# oresat-backplane.net
KiCad netlist of a schematic drawn in EAGLE
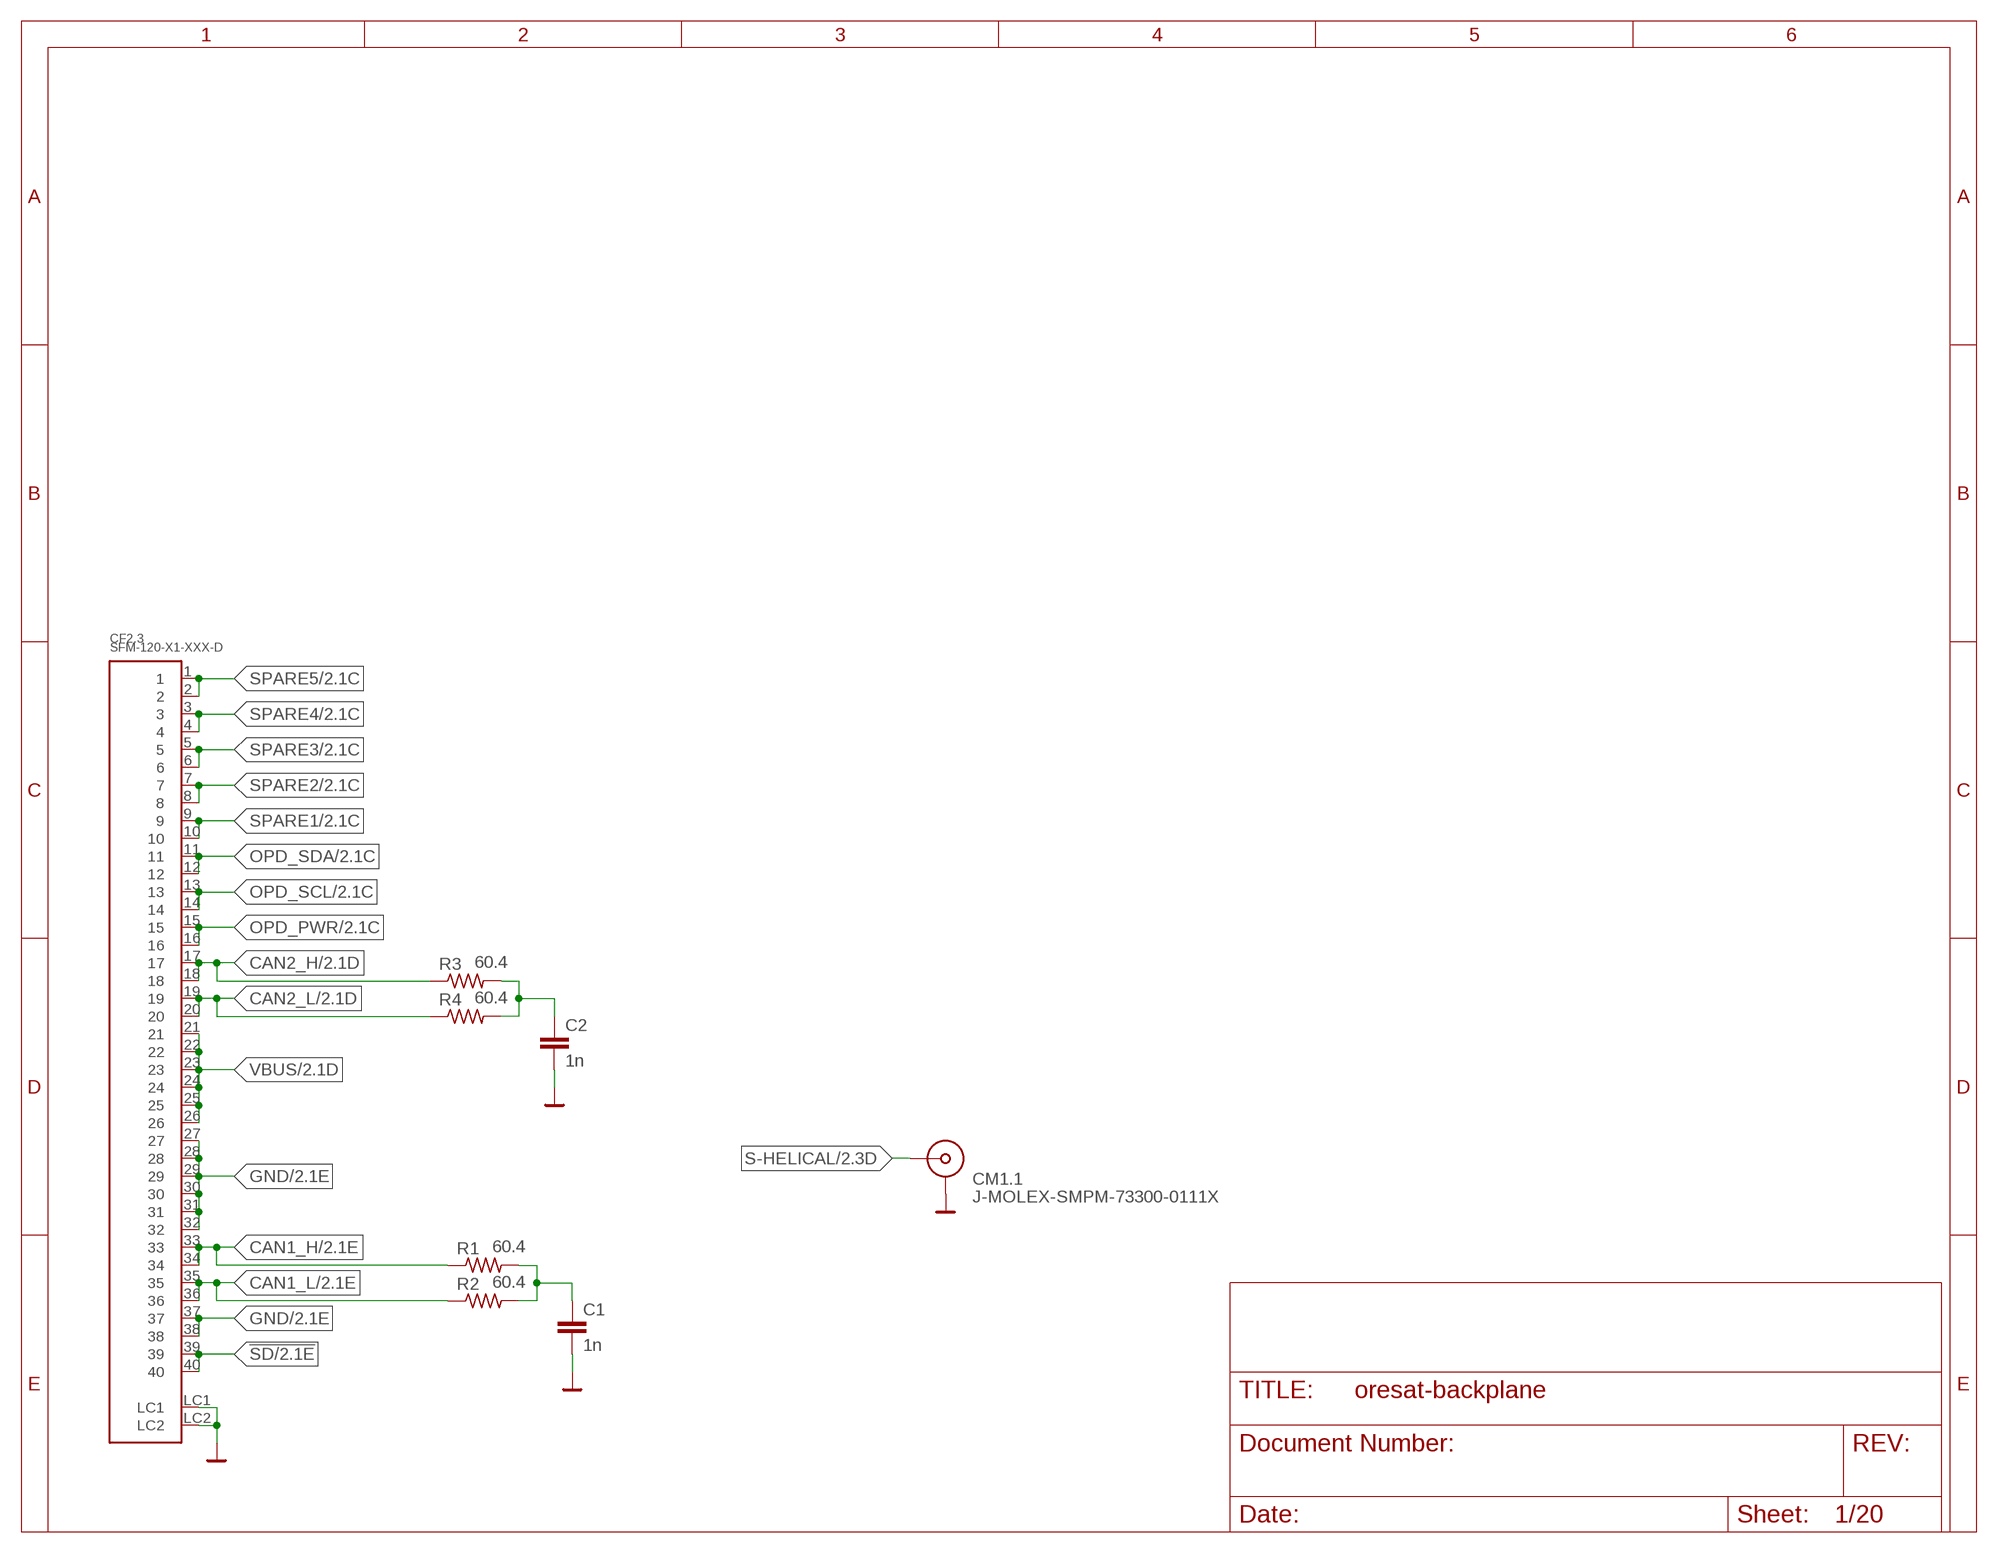
[diagram p0: schematic, sheet 1]
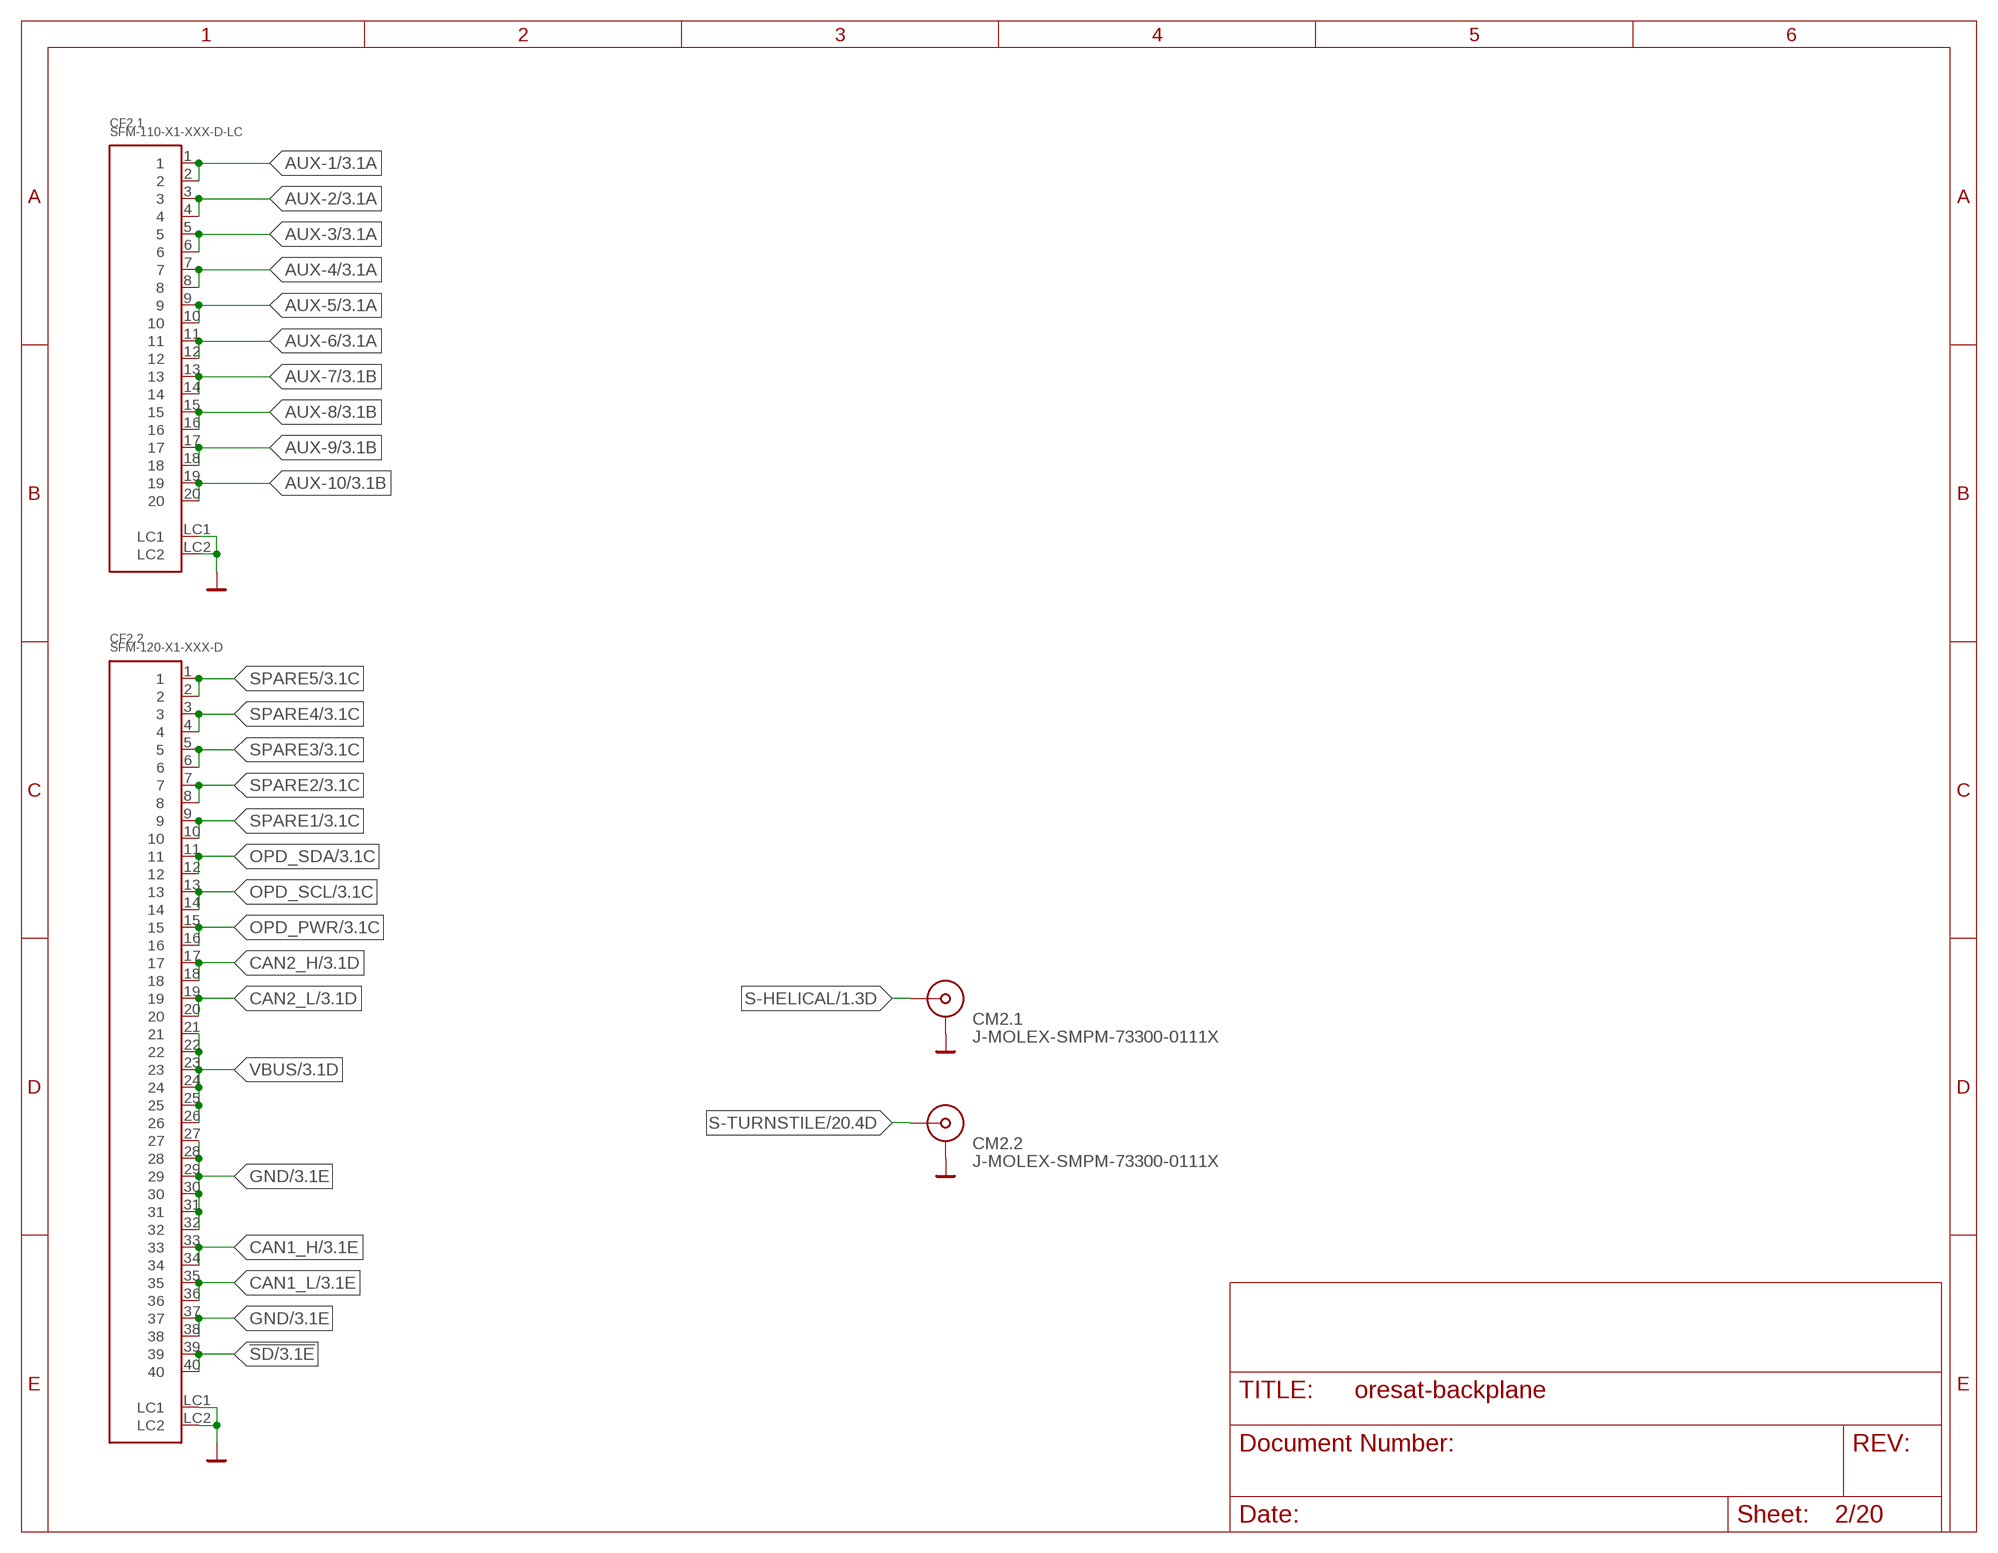
[diagram p1: schematic, sheet 2]
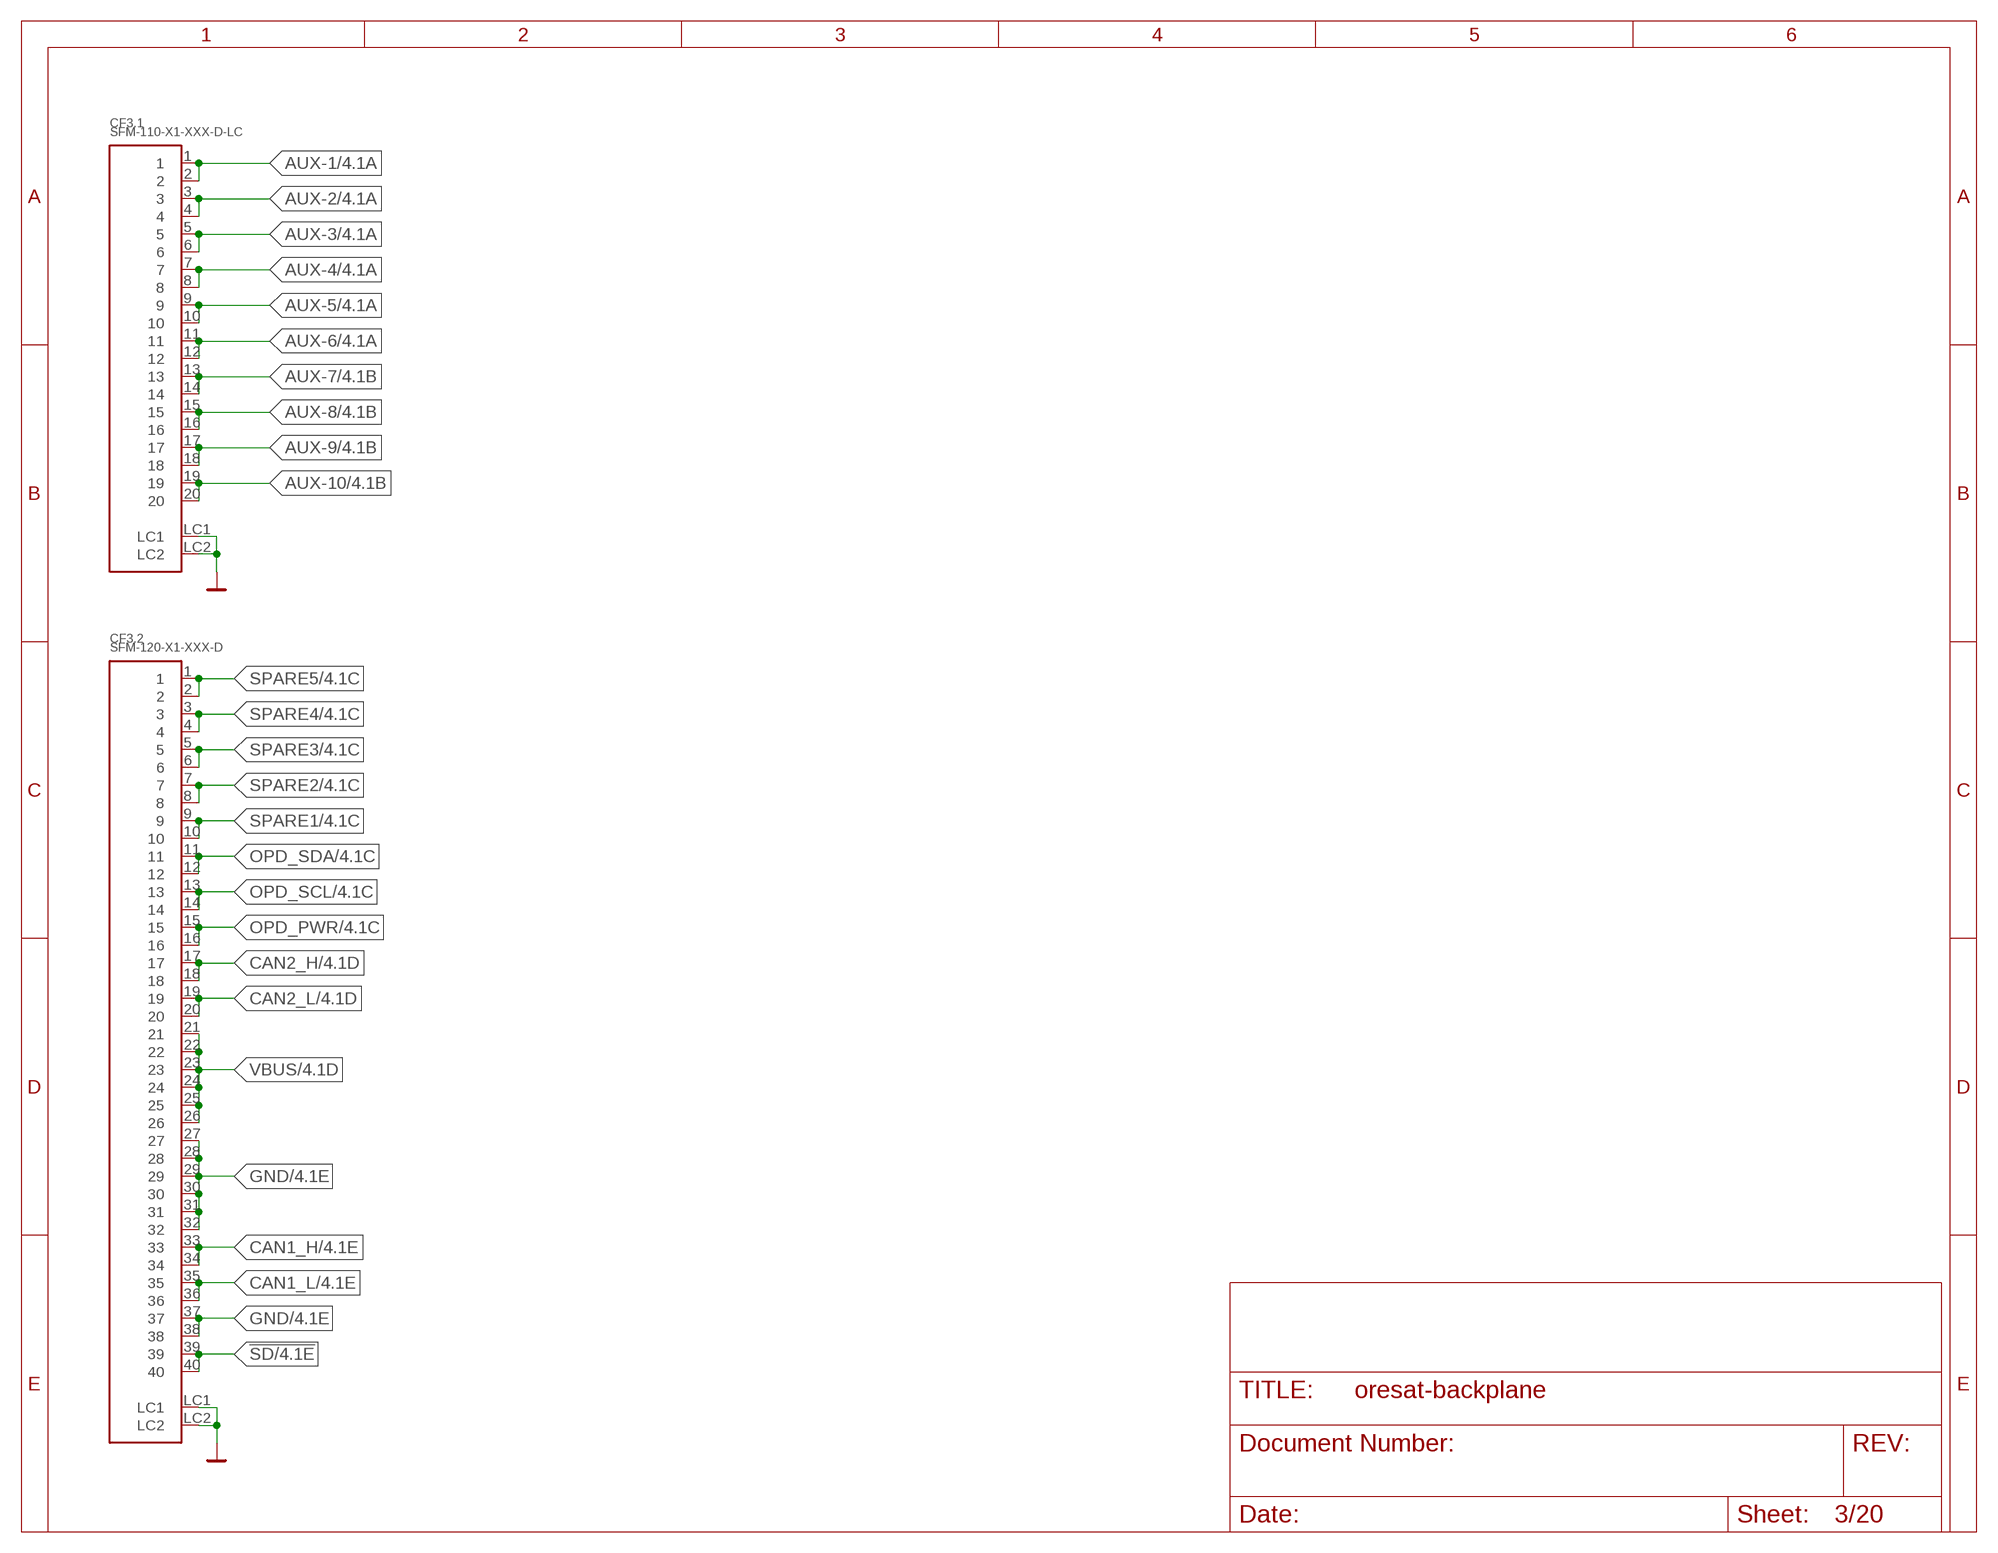
[diagram p2: schematic, sheet 3]
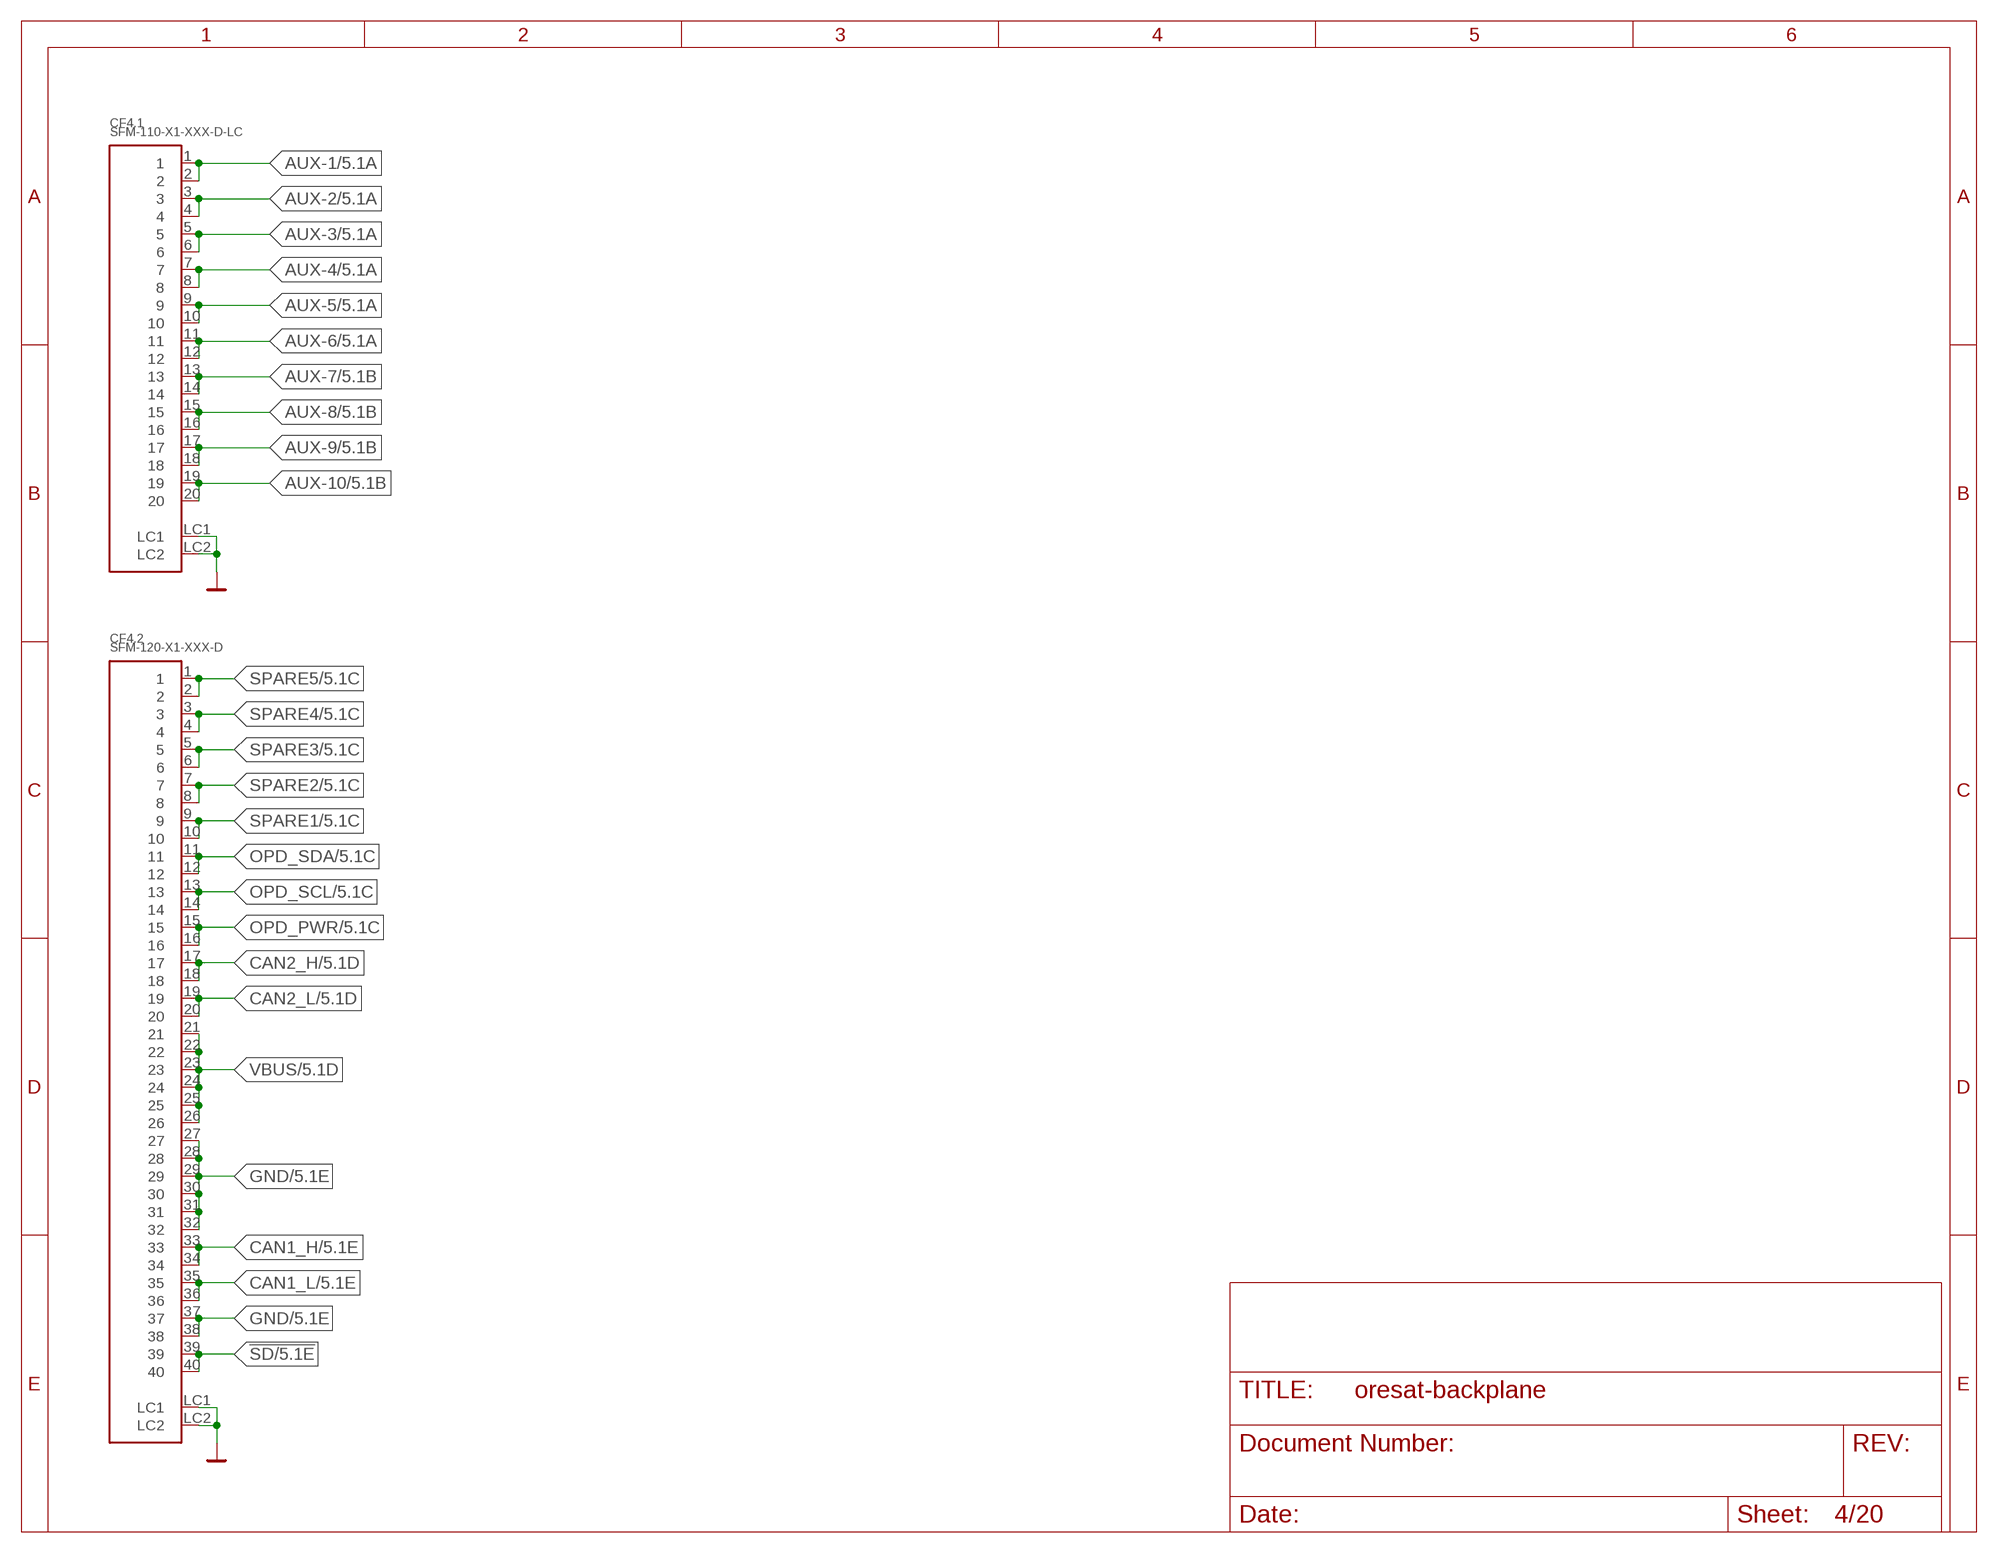
[diagram p3: schematic, sheet 4]
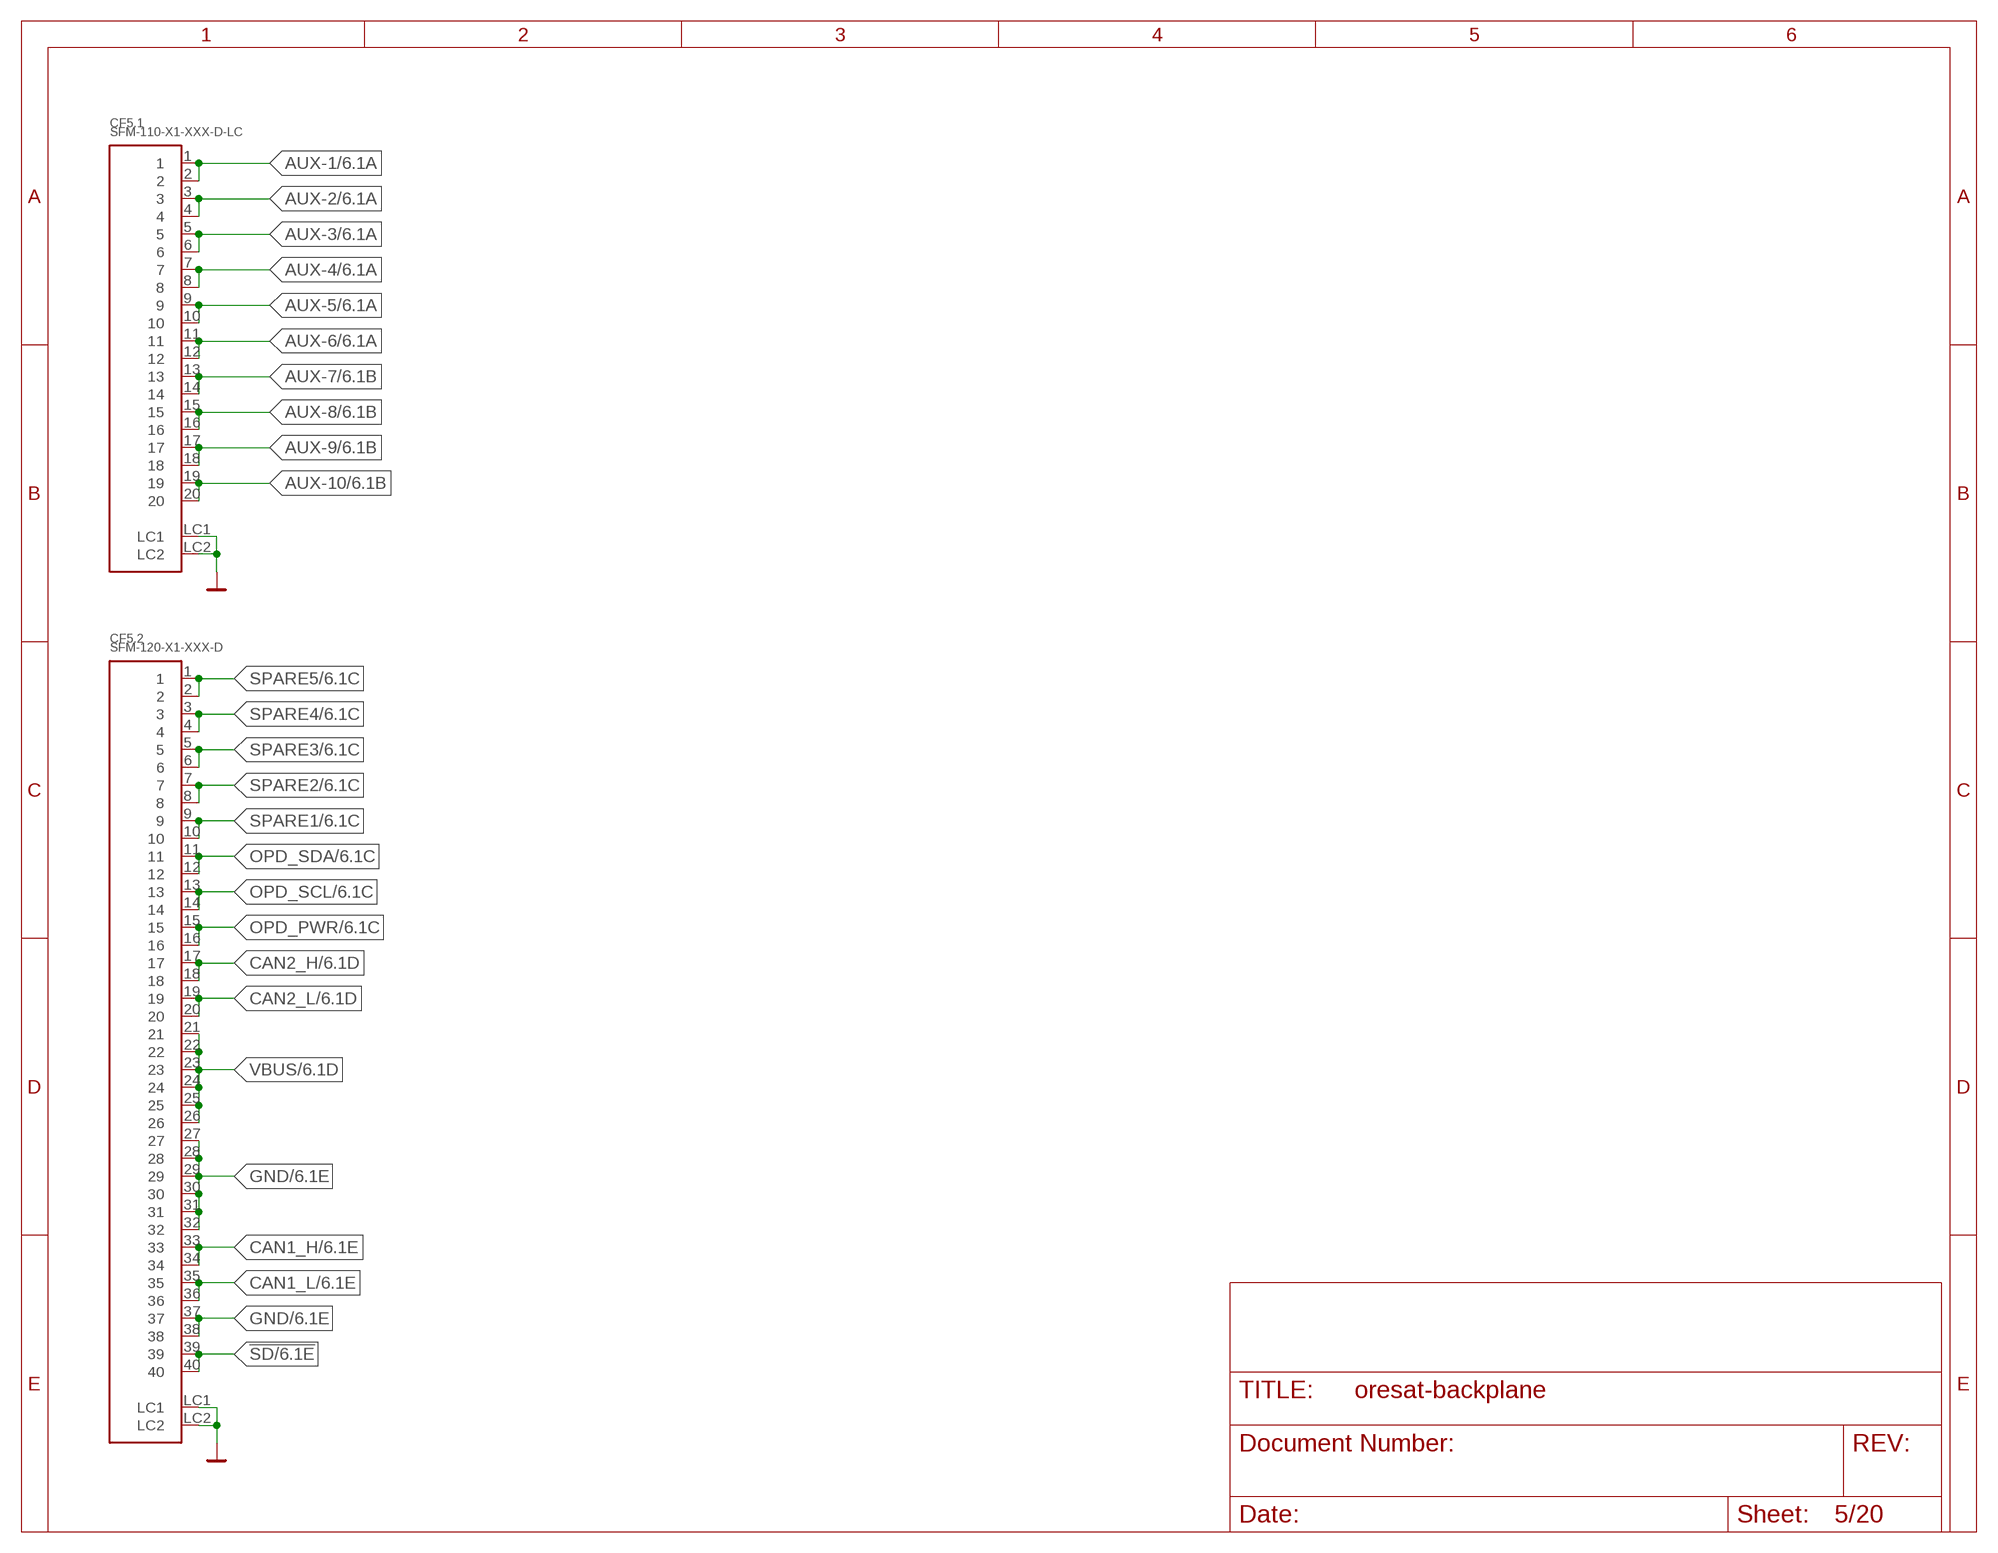
[diagram p4: schematic, sheet 5]
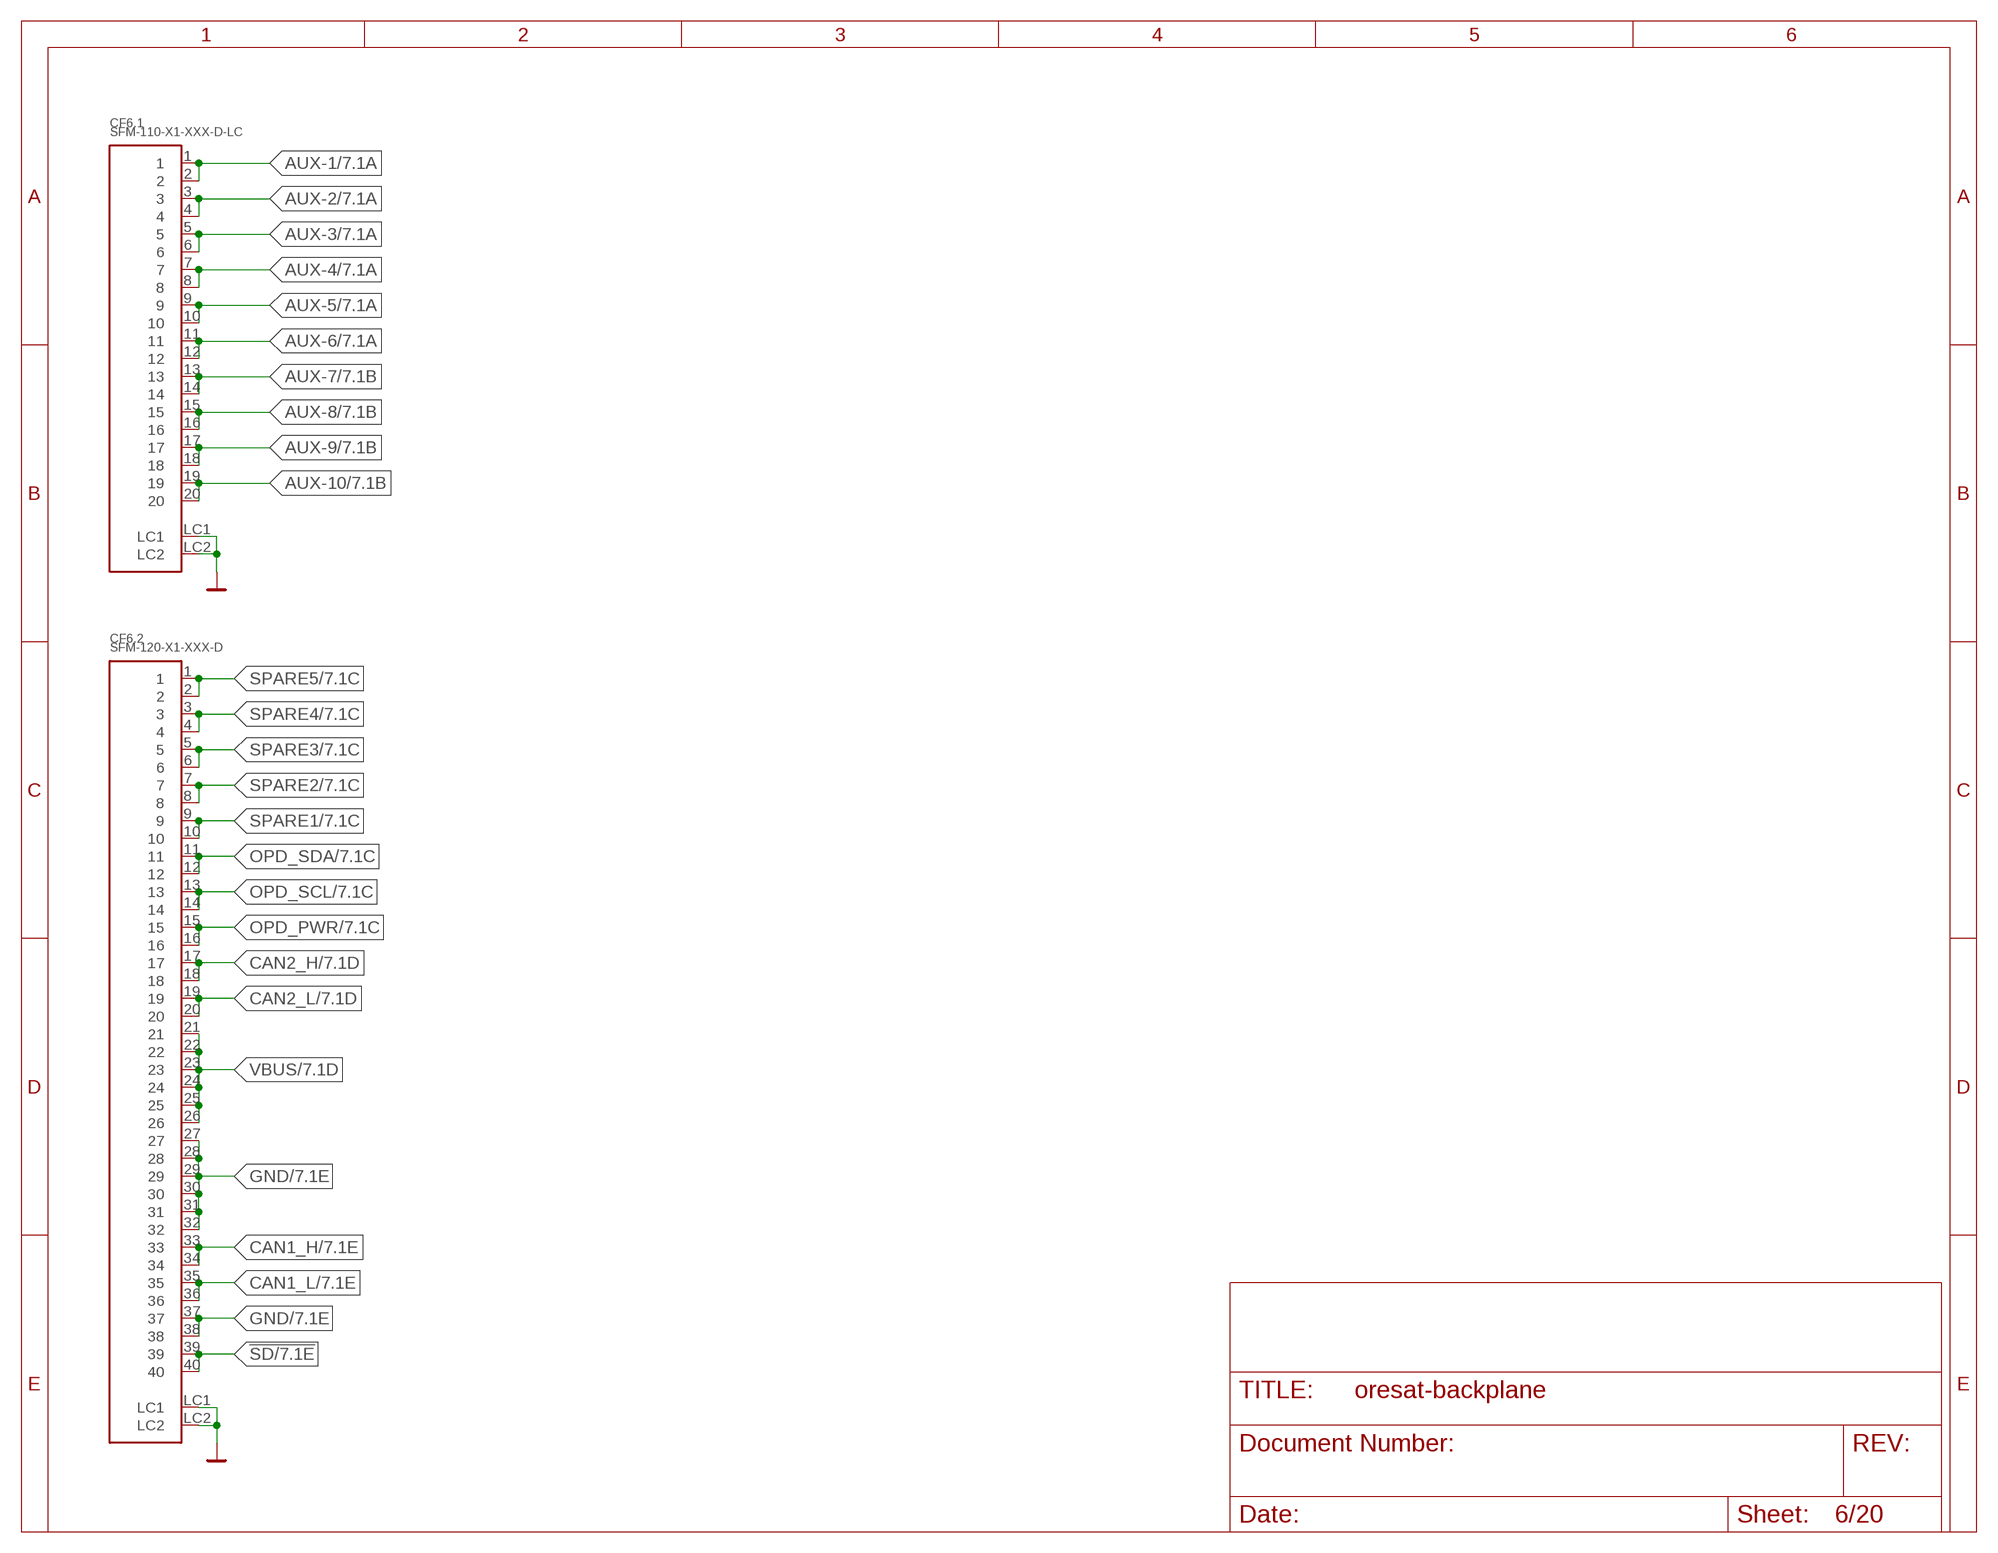
[diagram p5: schematic, sheet 6]
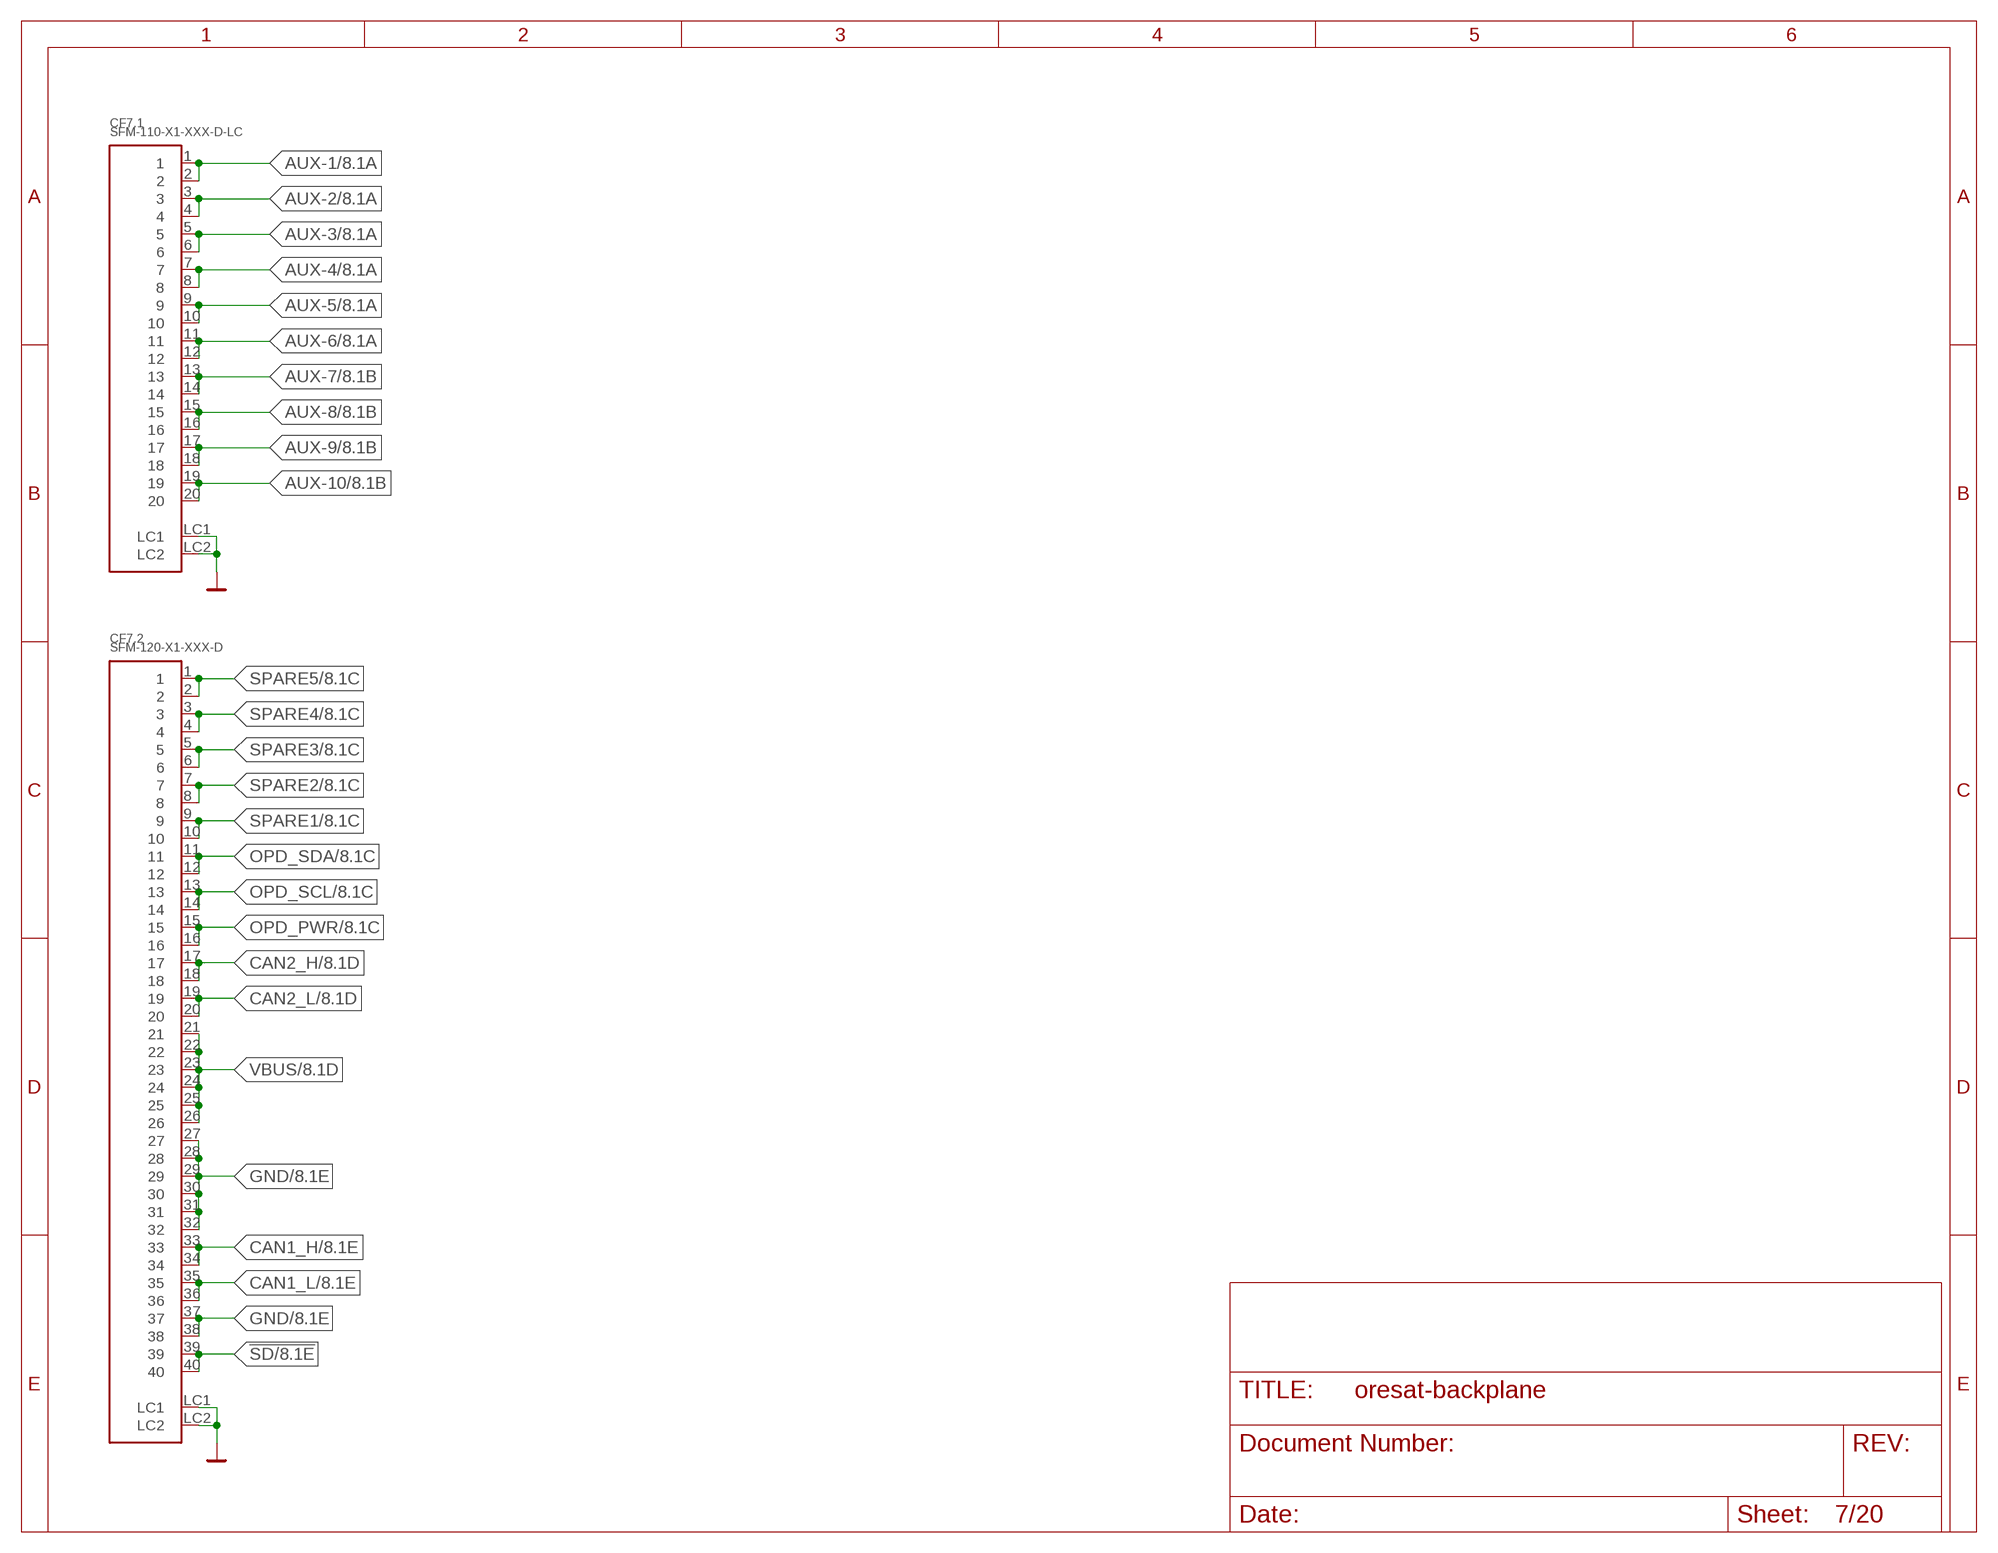
[diagram p6: schematic, sheet 7]
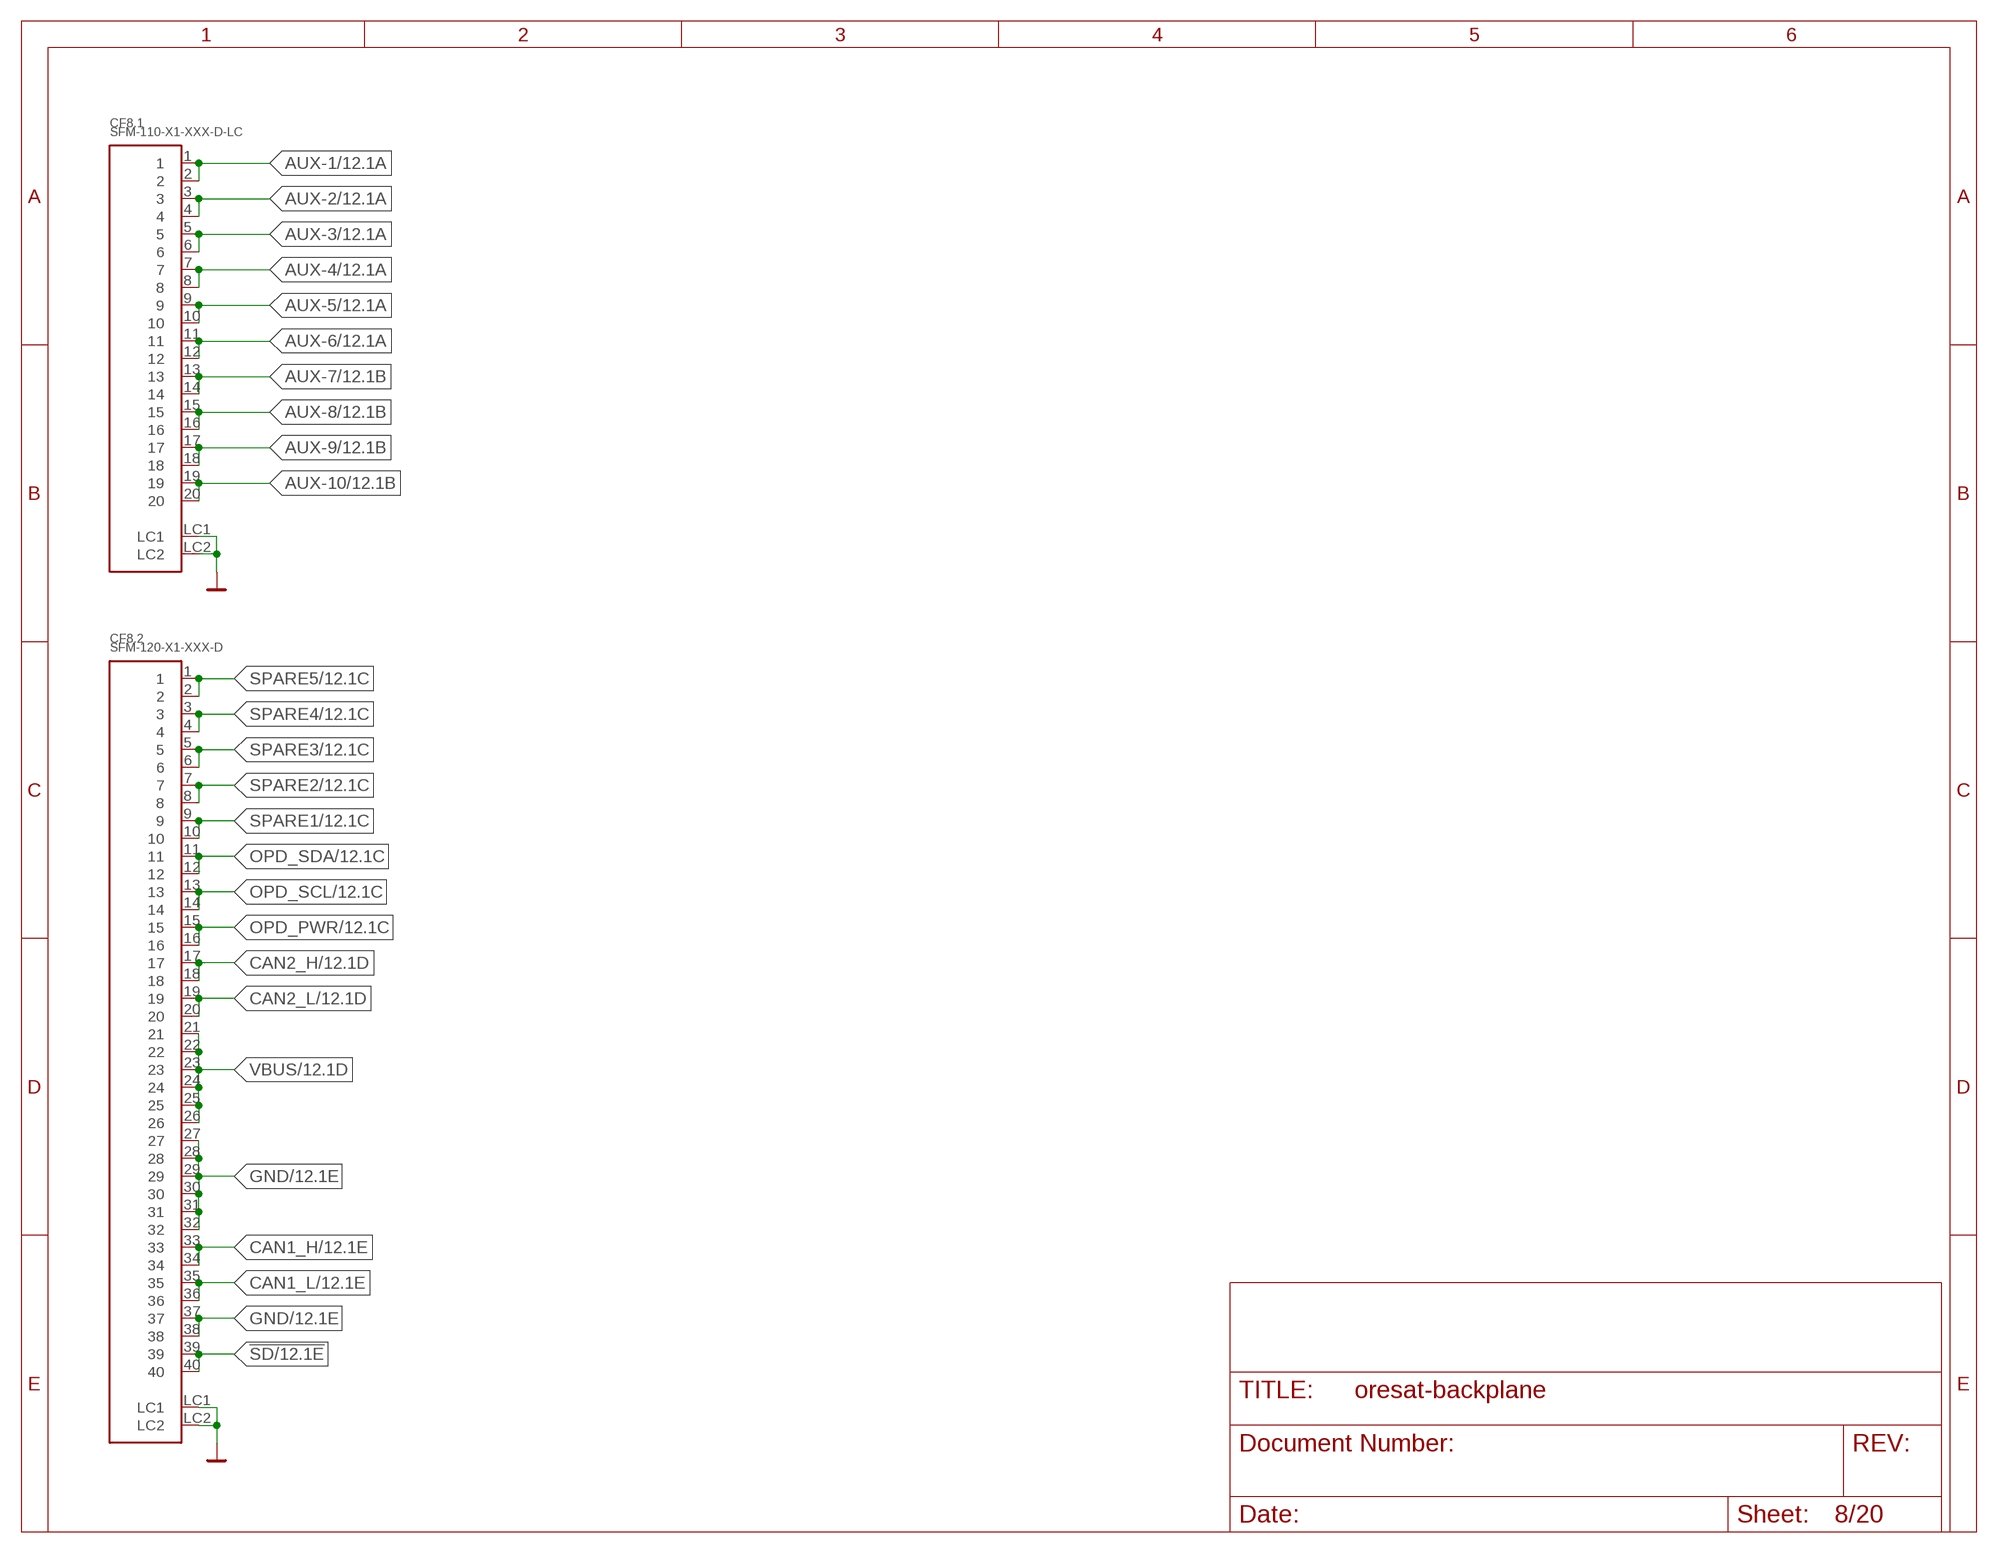
[diagram p7: schematic, sheet 8]
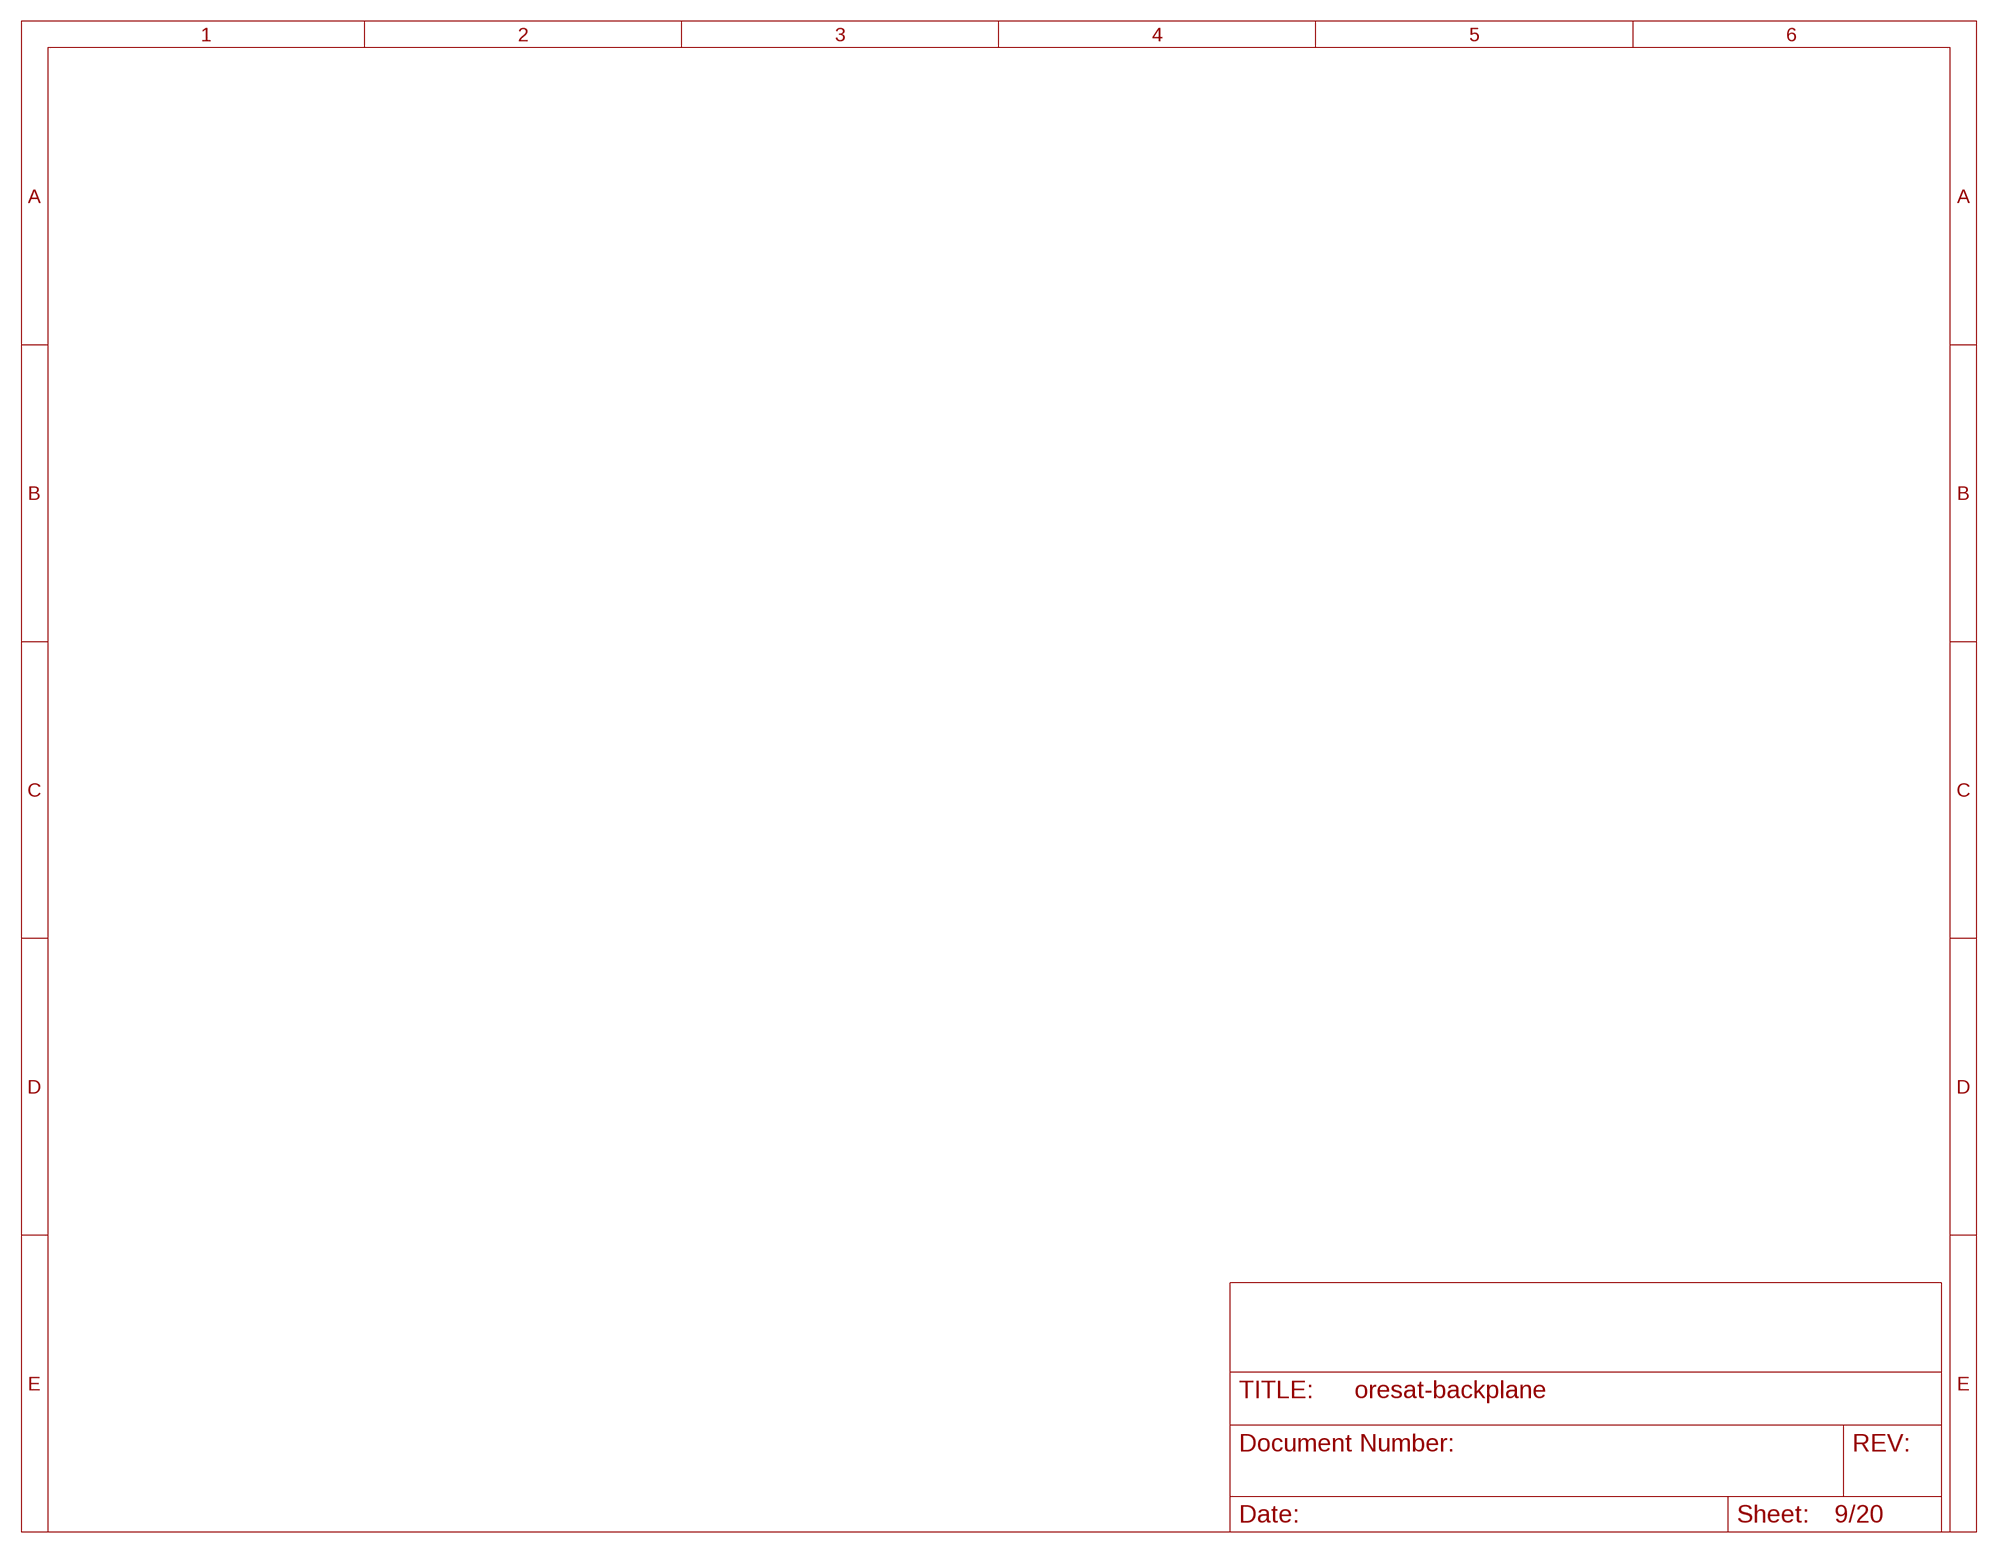
[diagram p8: schematic, sheet 9]
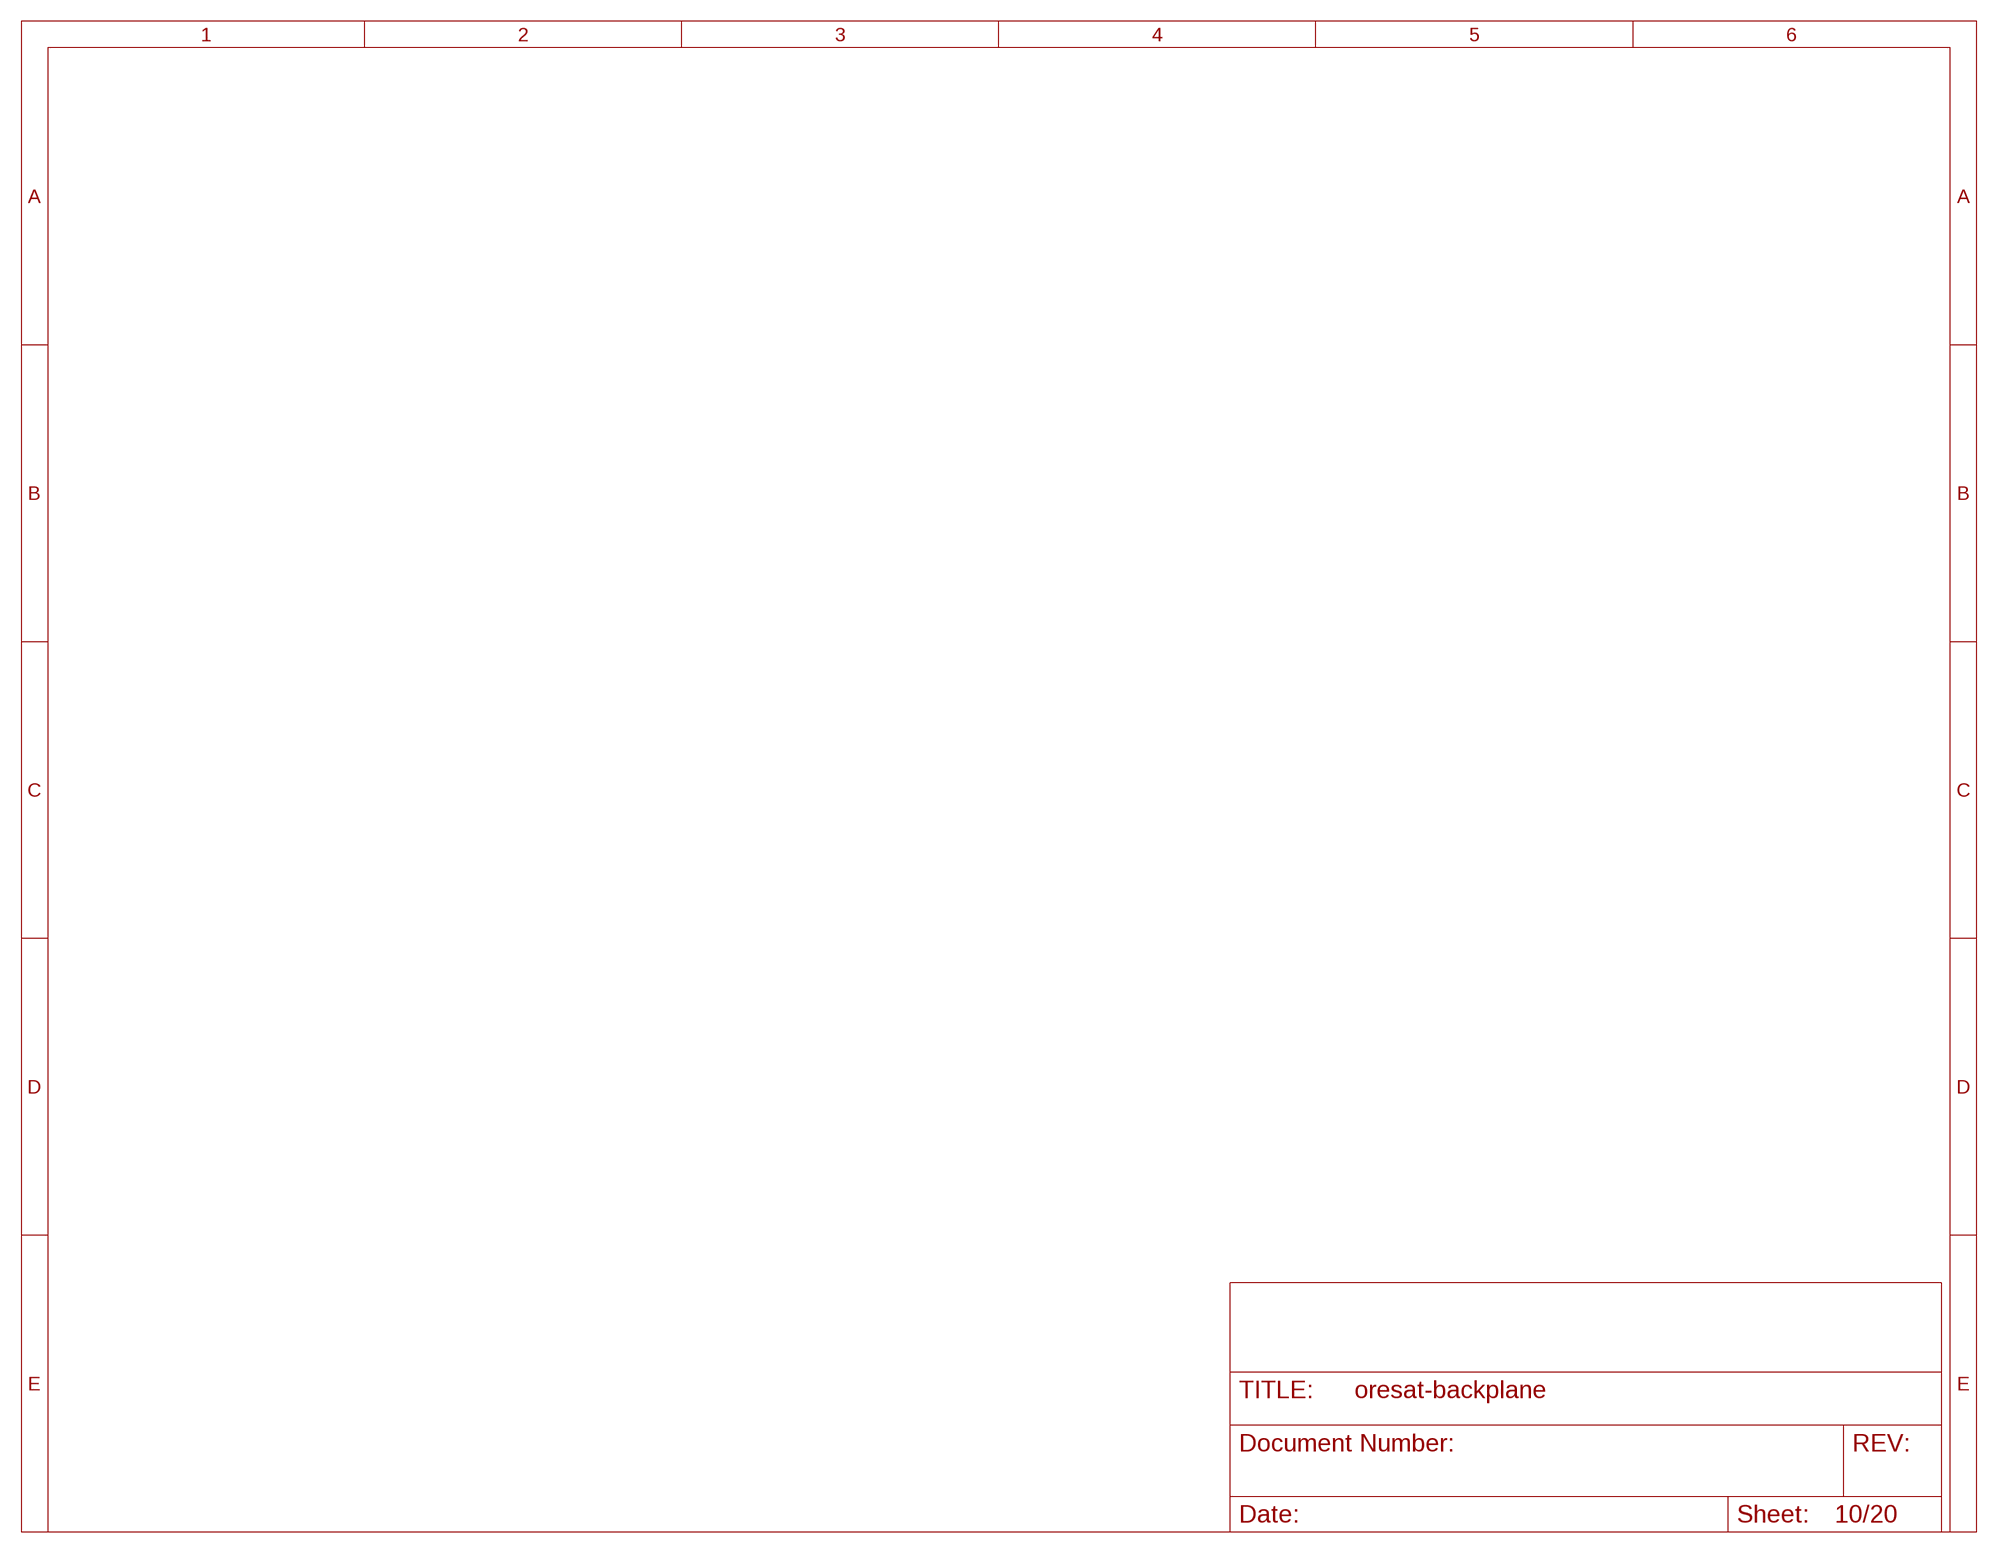
[diagram p9: schematic, sheet 10]
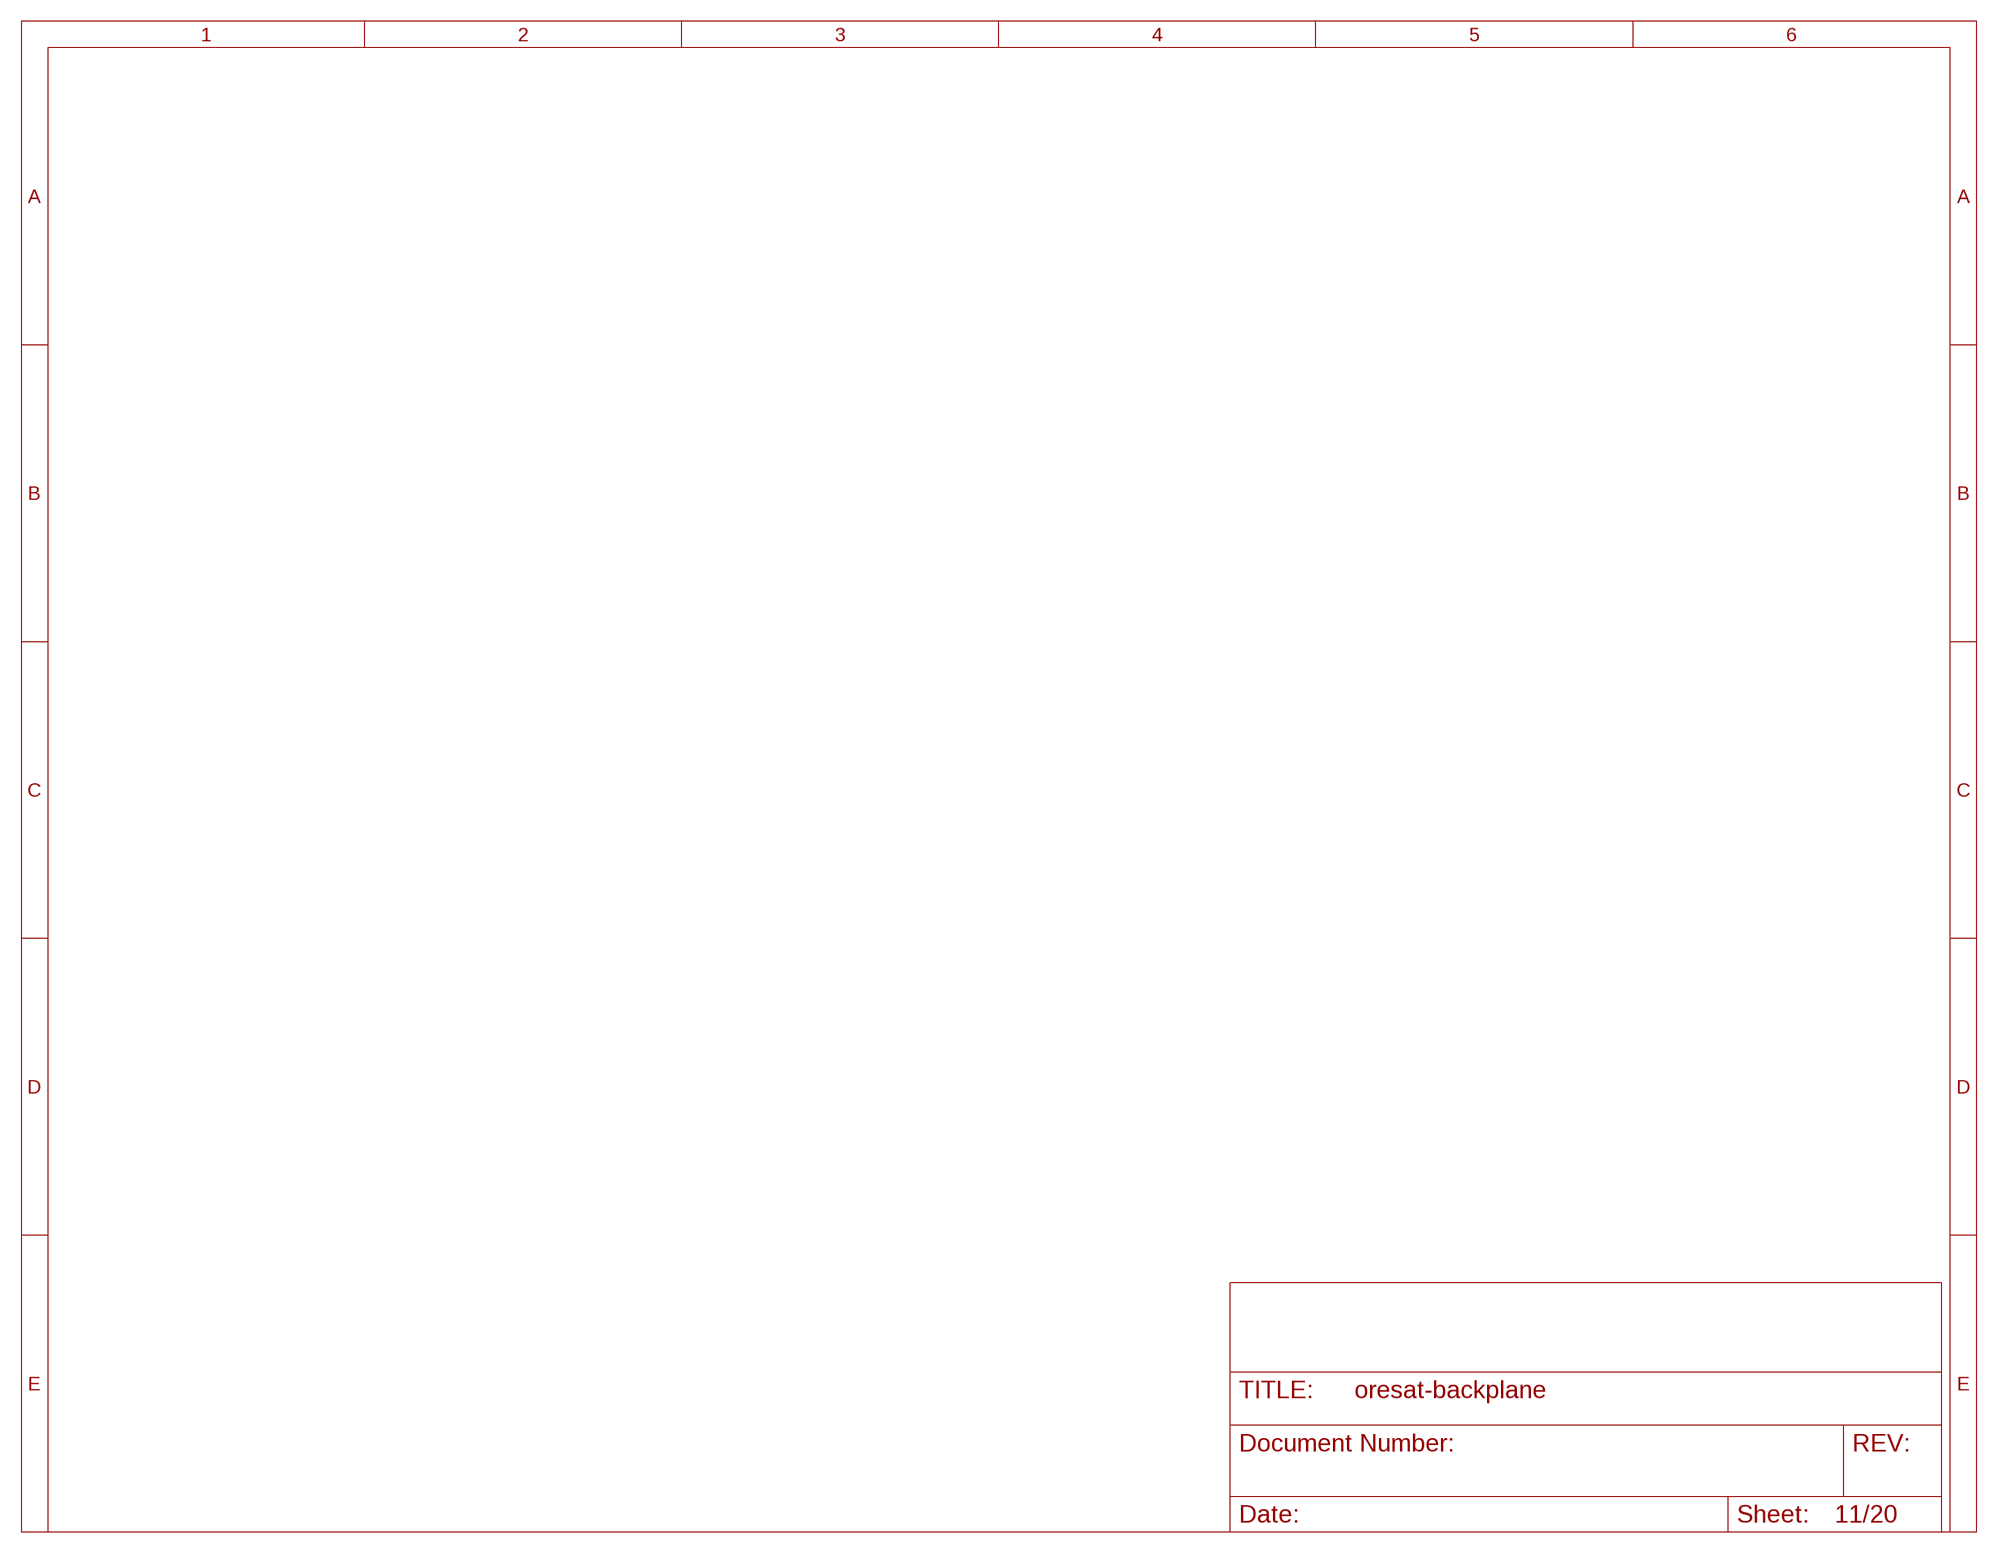
[diagram p10: schematic, sheet 11]
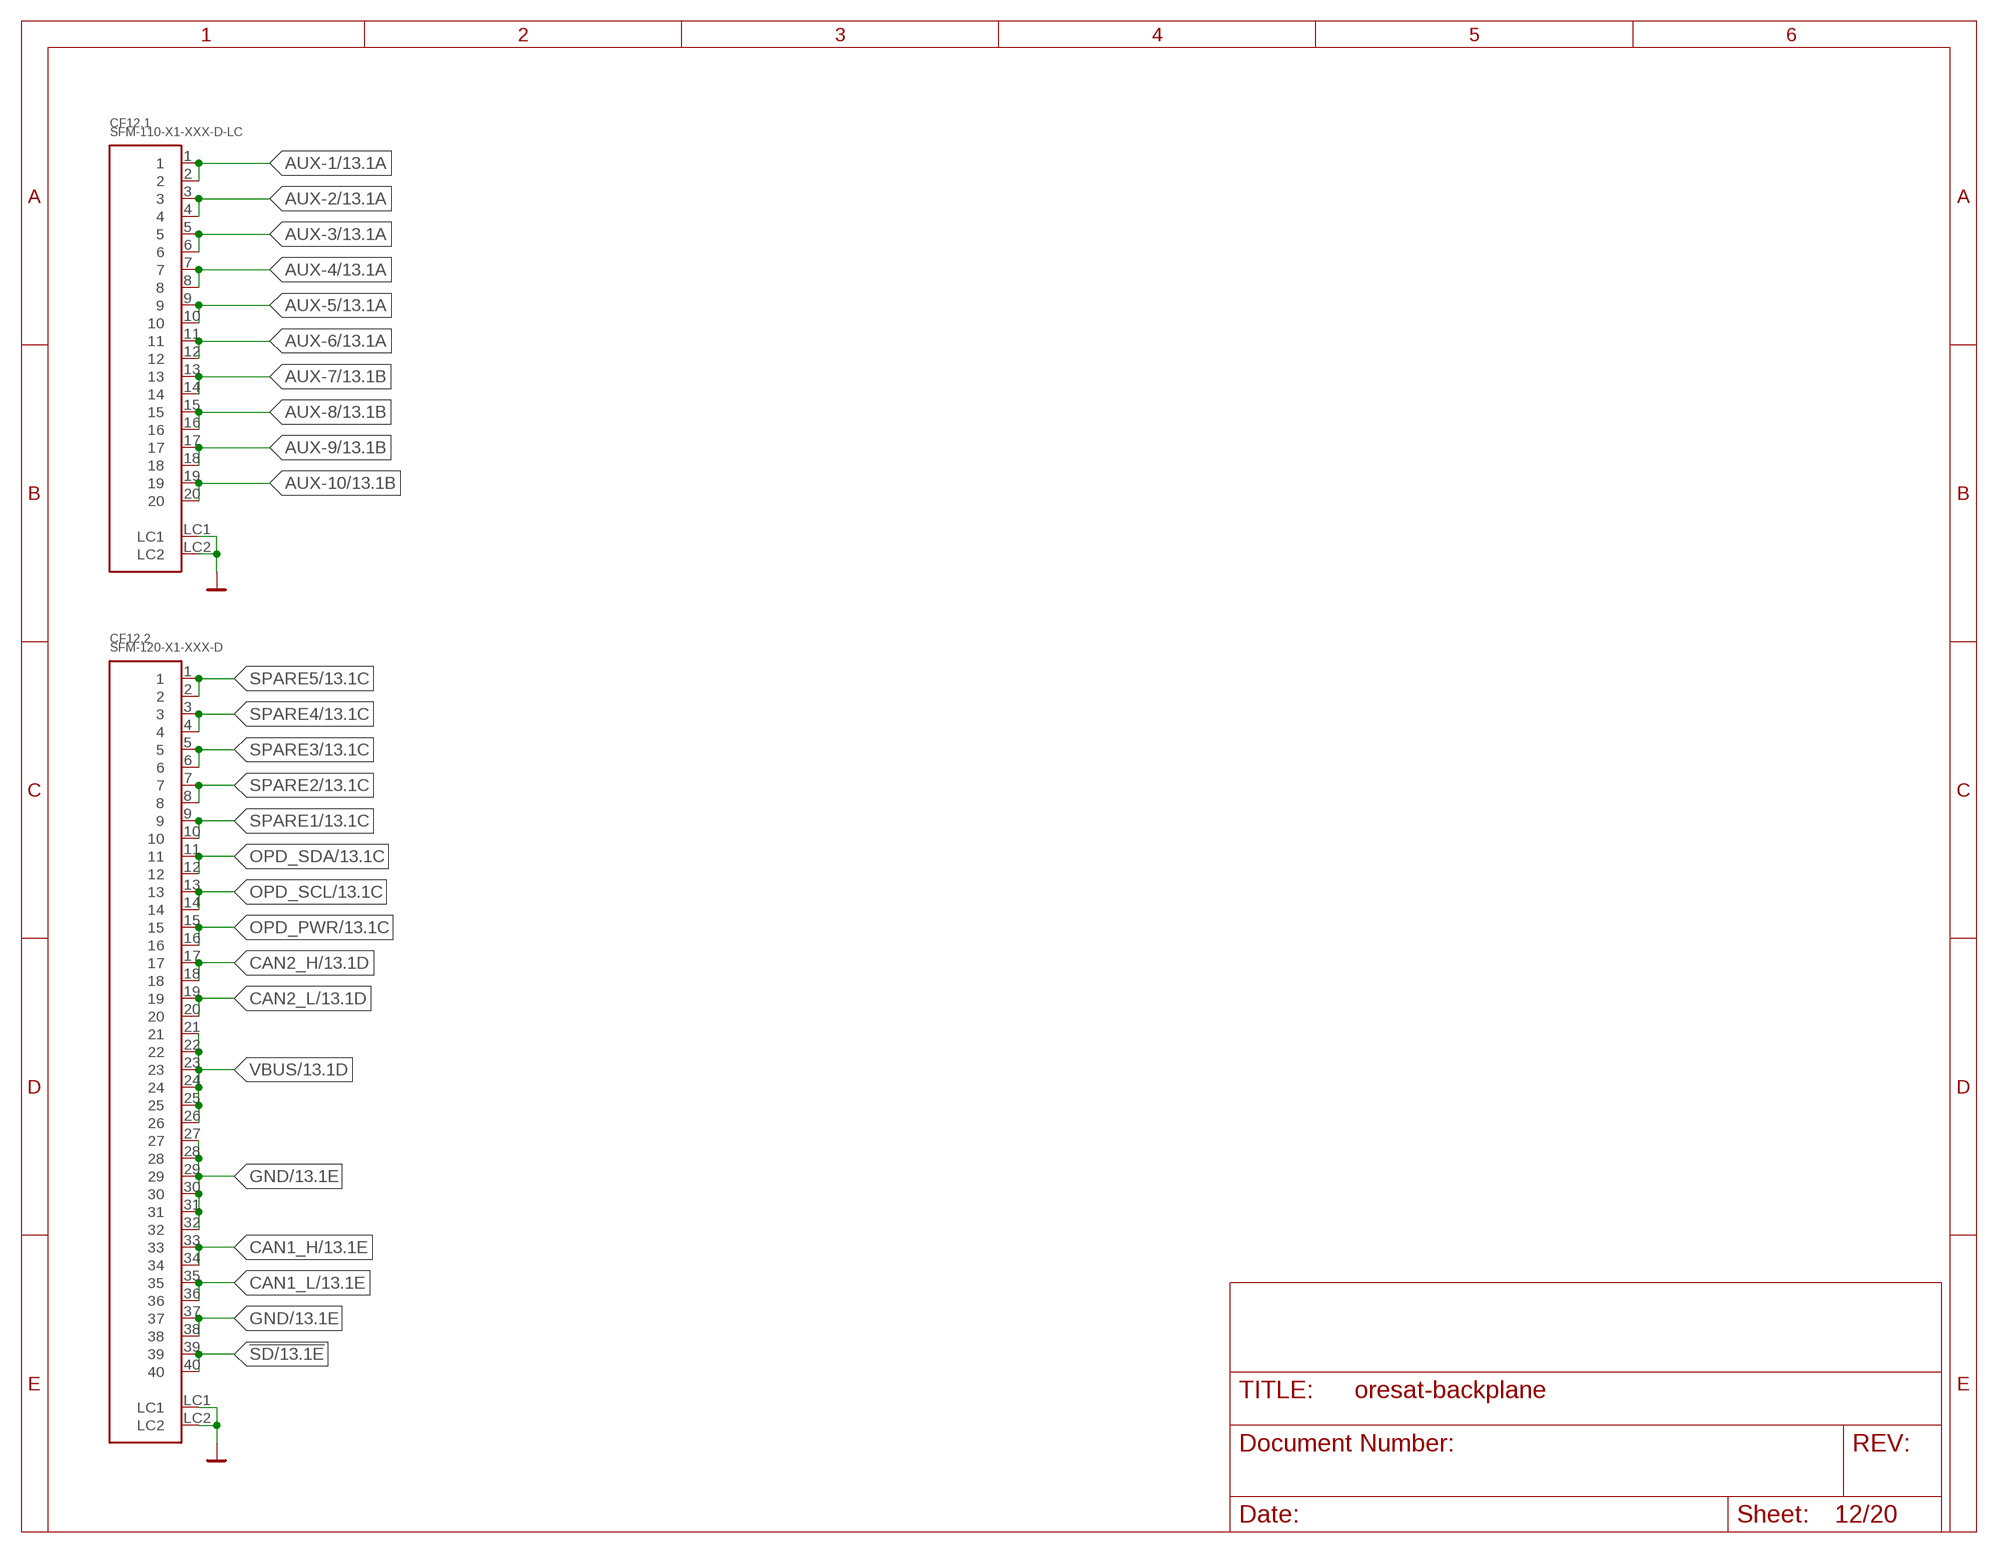
[diagram p11: schematic, sheet 12]
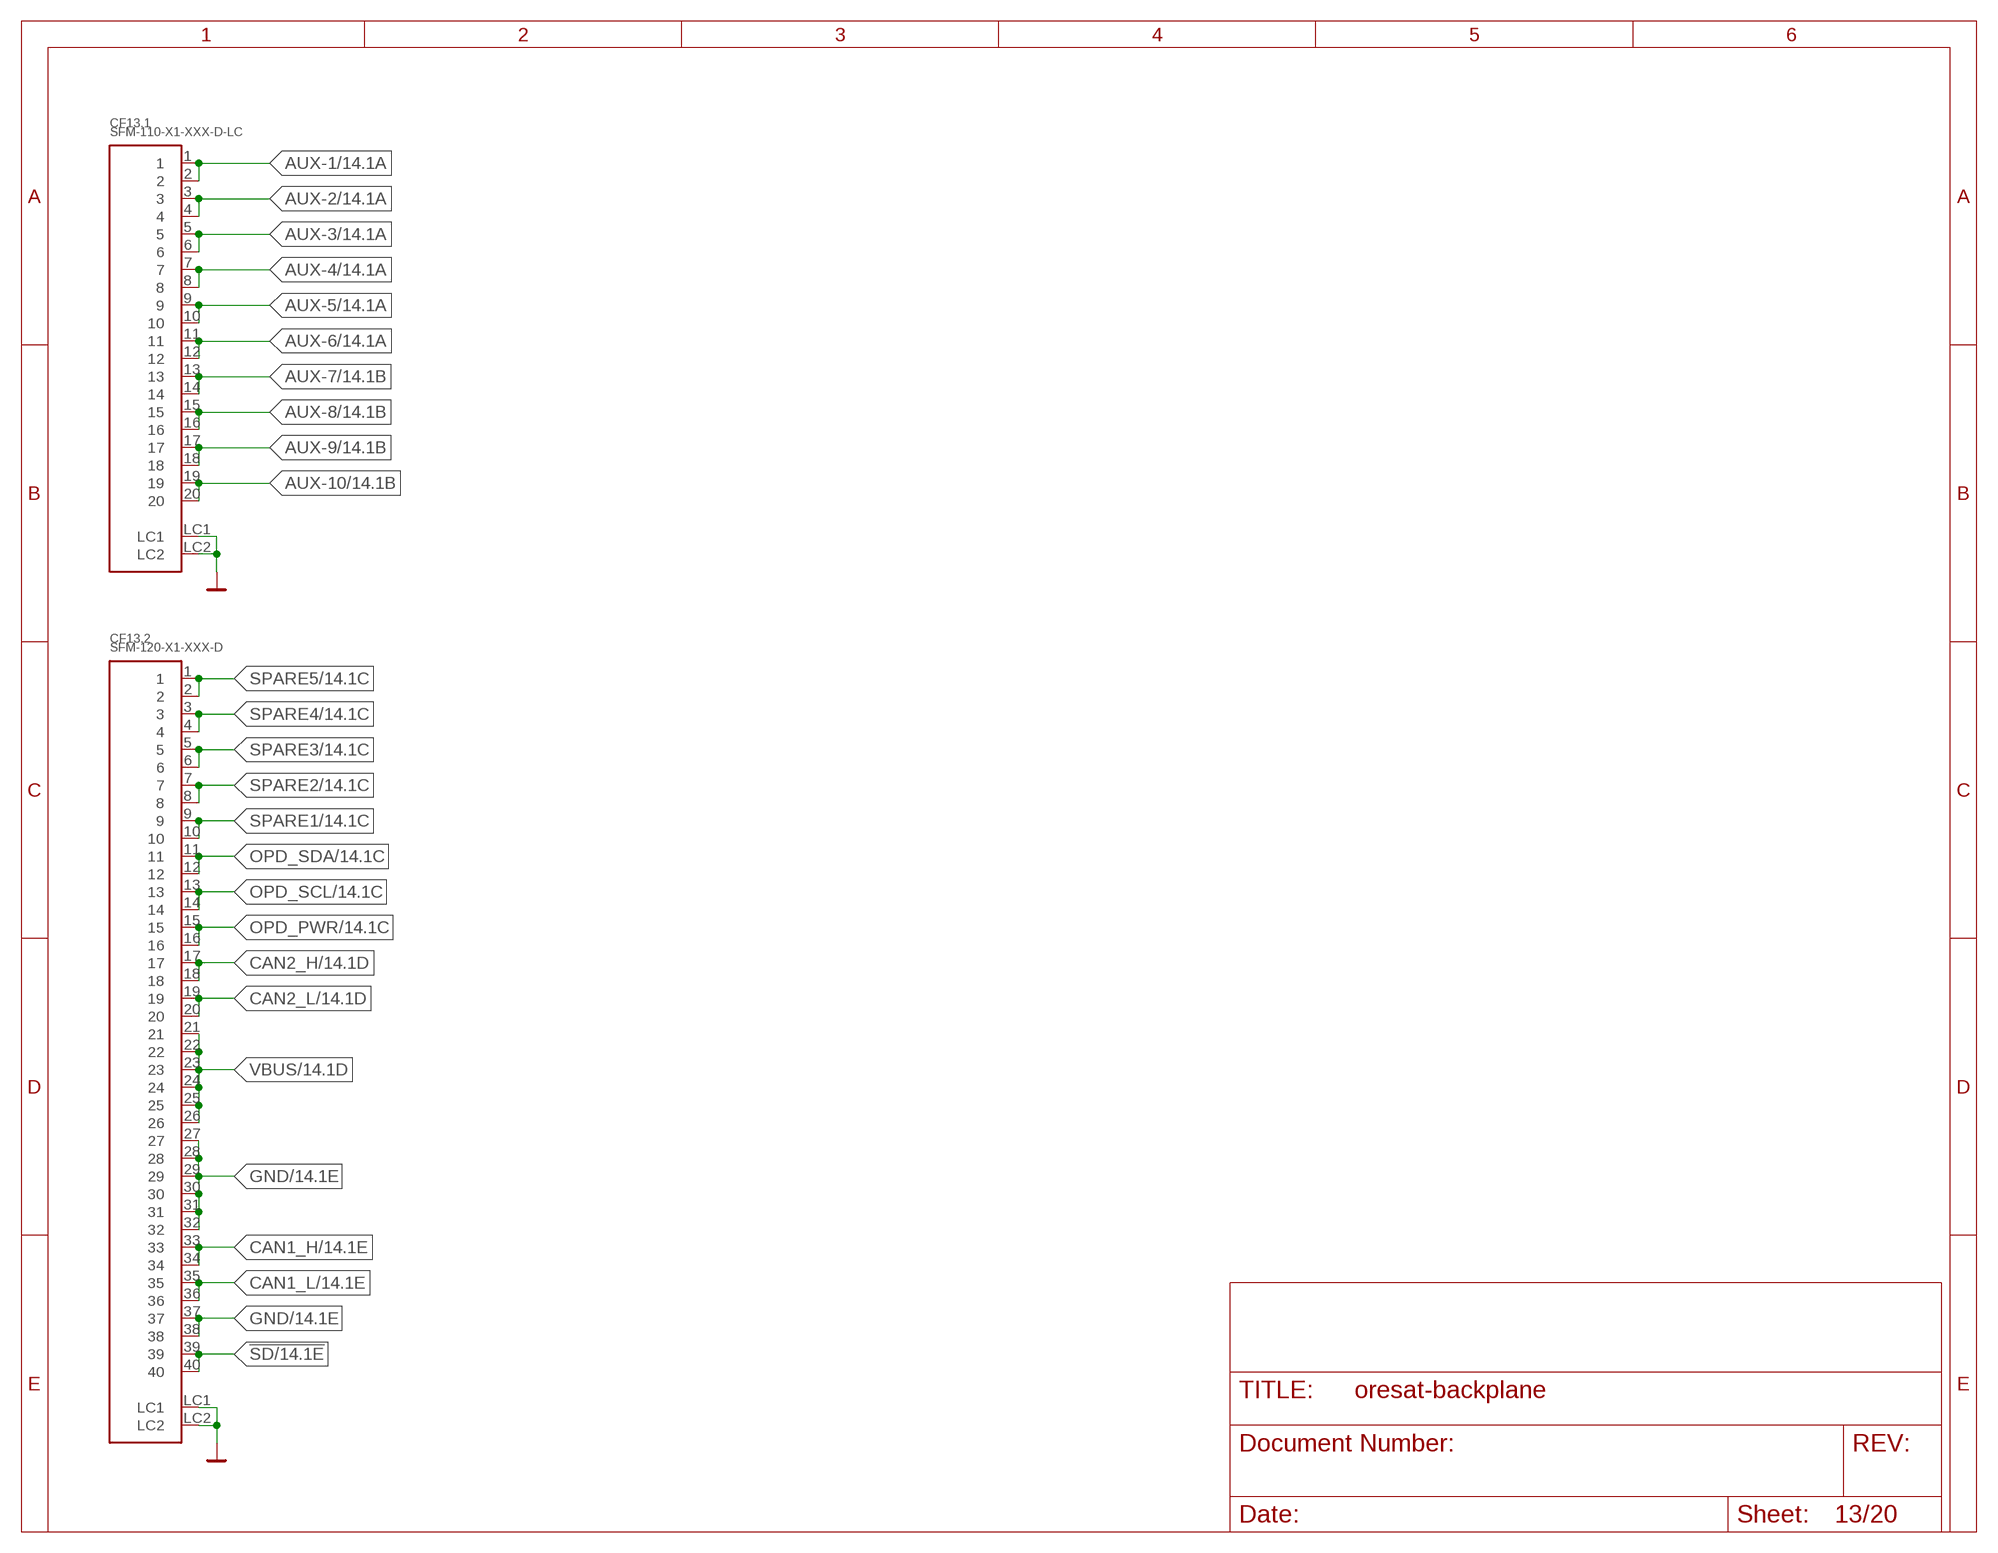
[diagram p12: schematic, sheet 13]
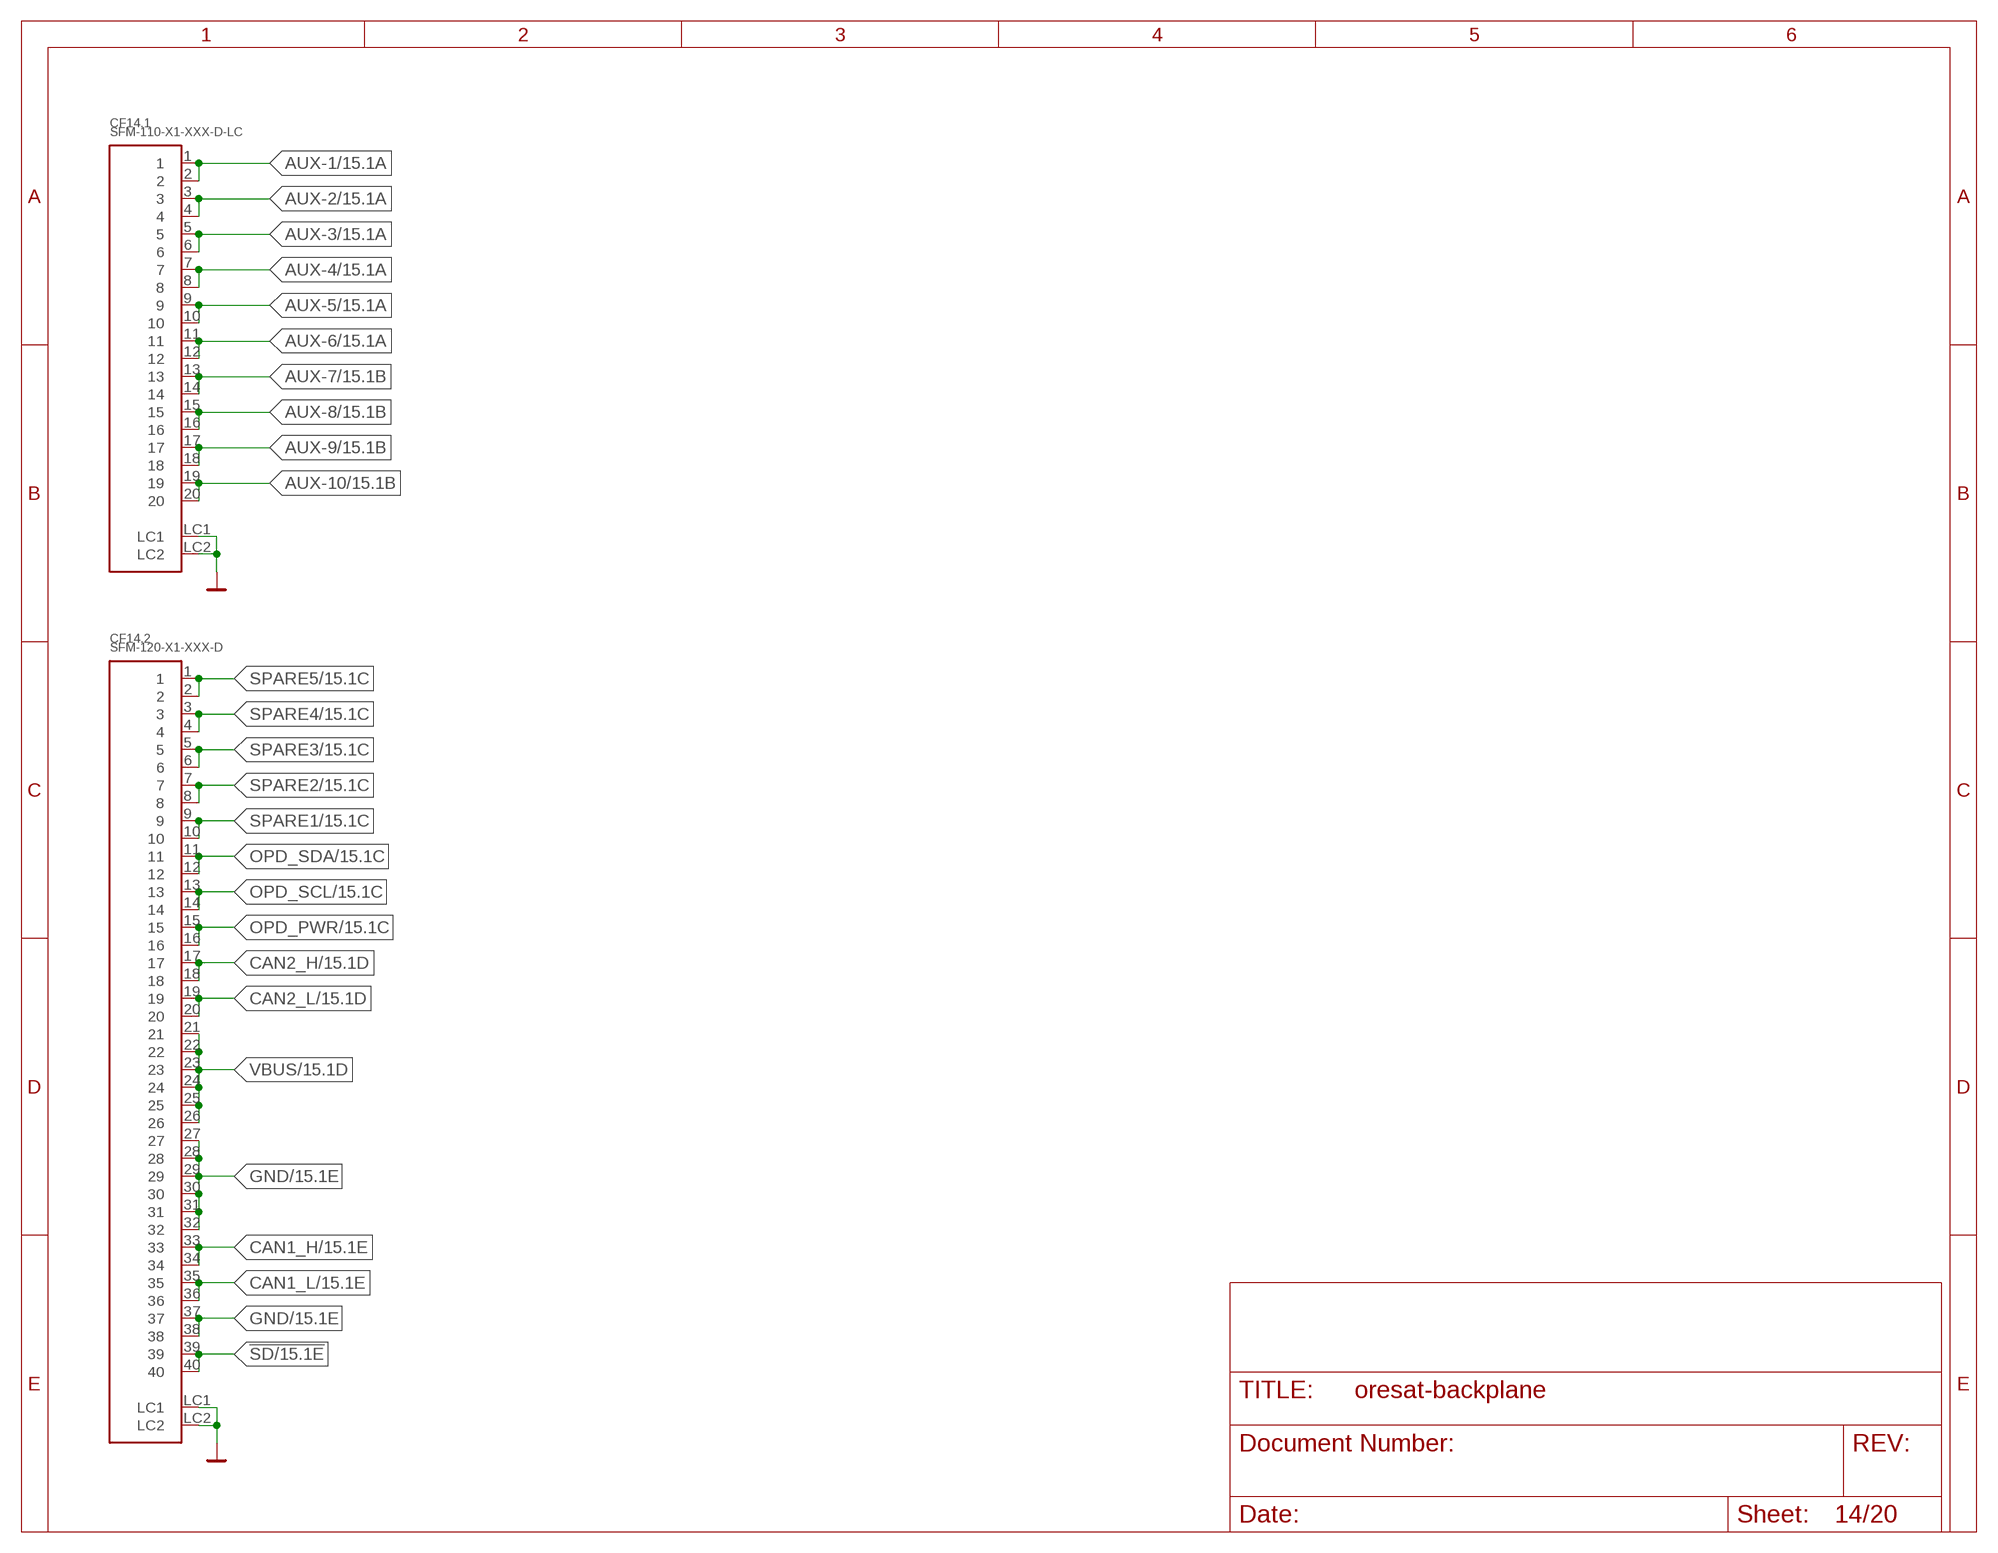
[diagram p13: schematic, sheet 14]
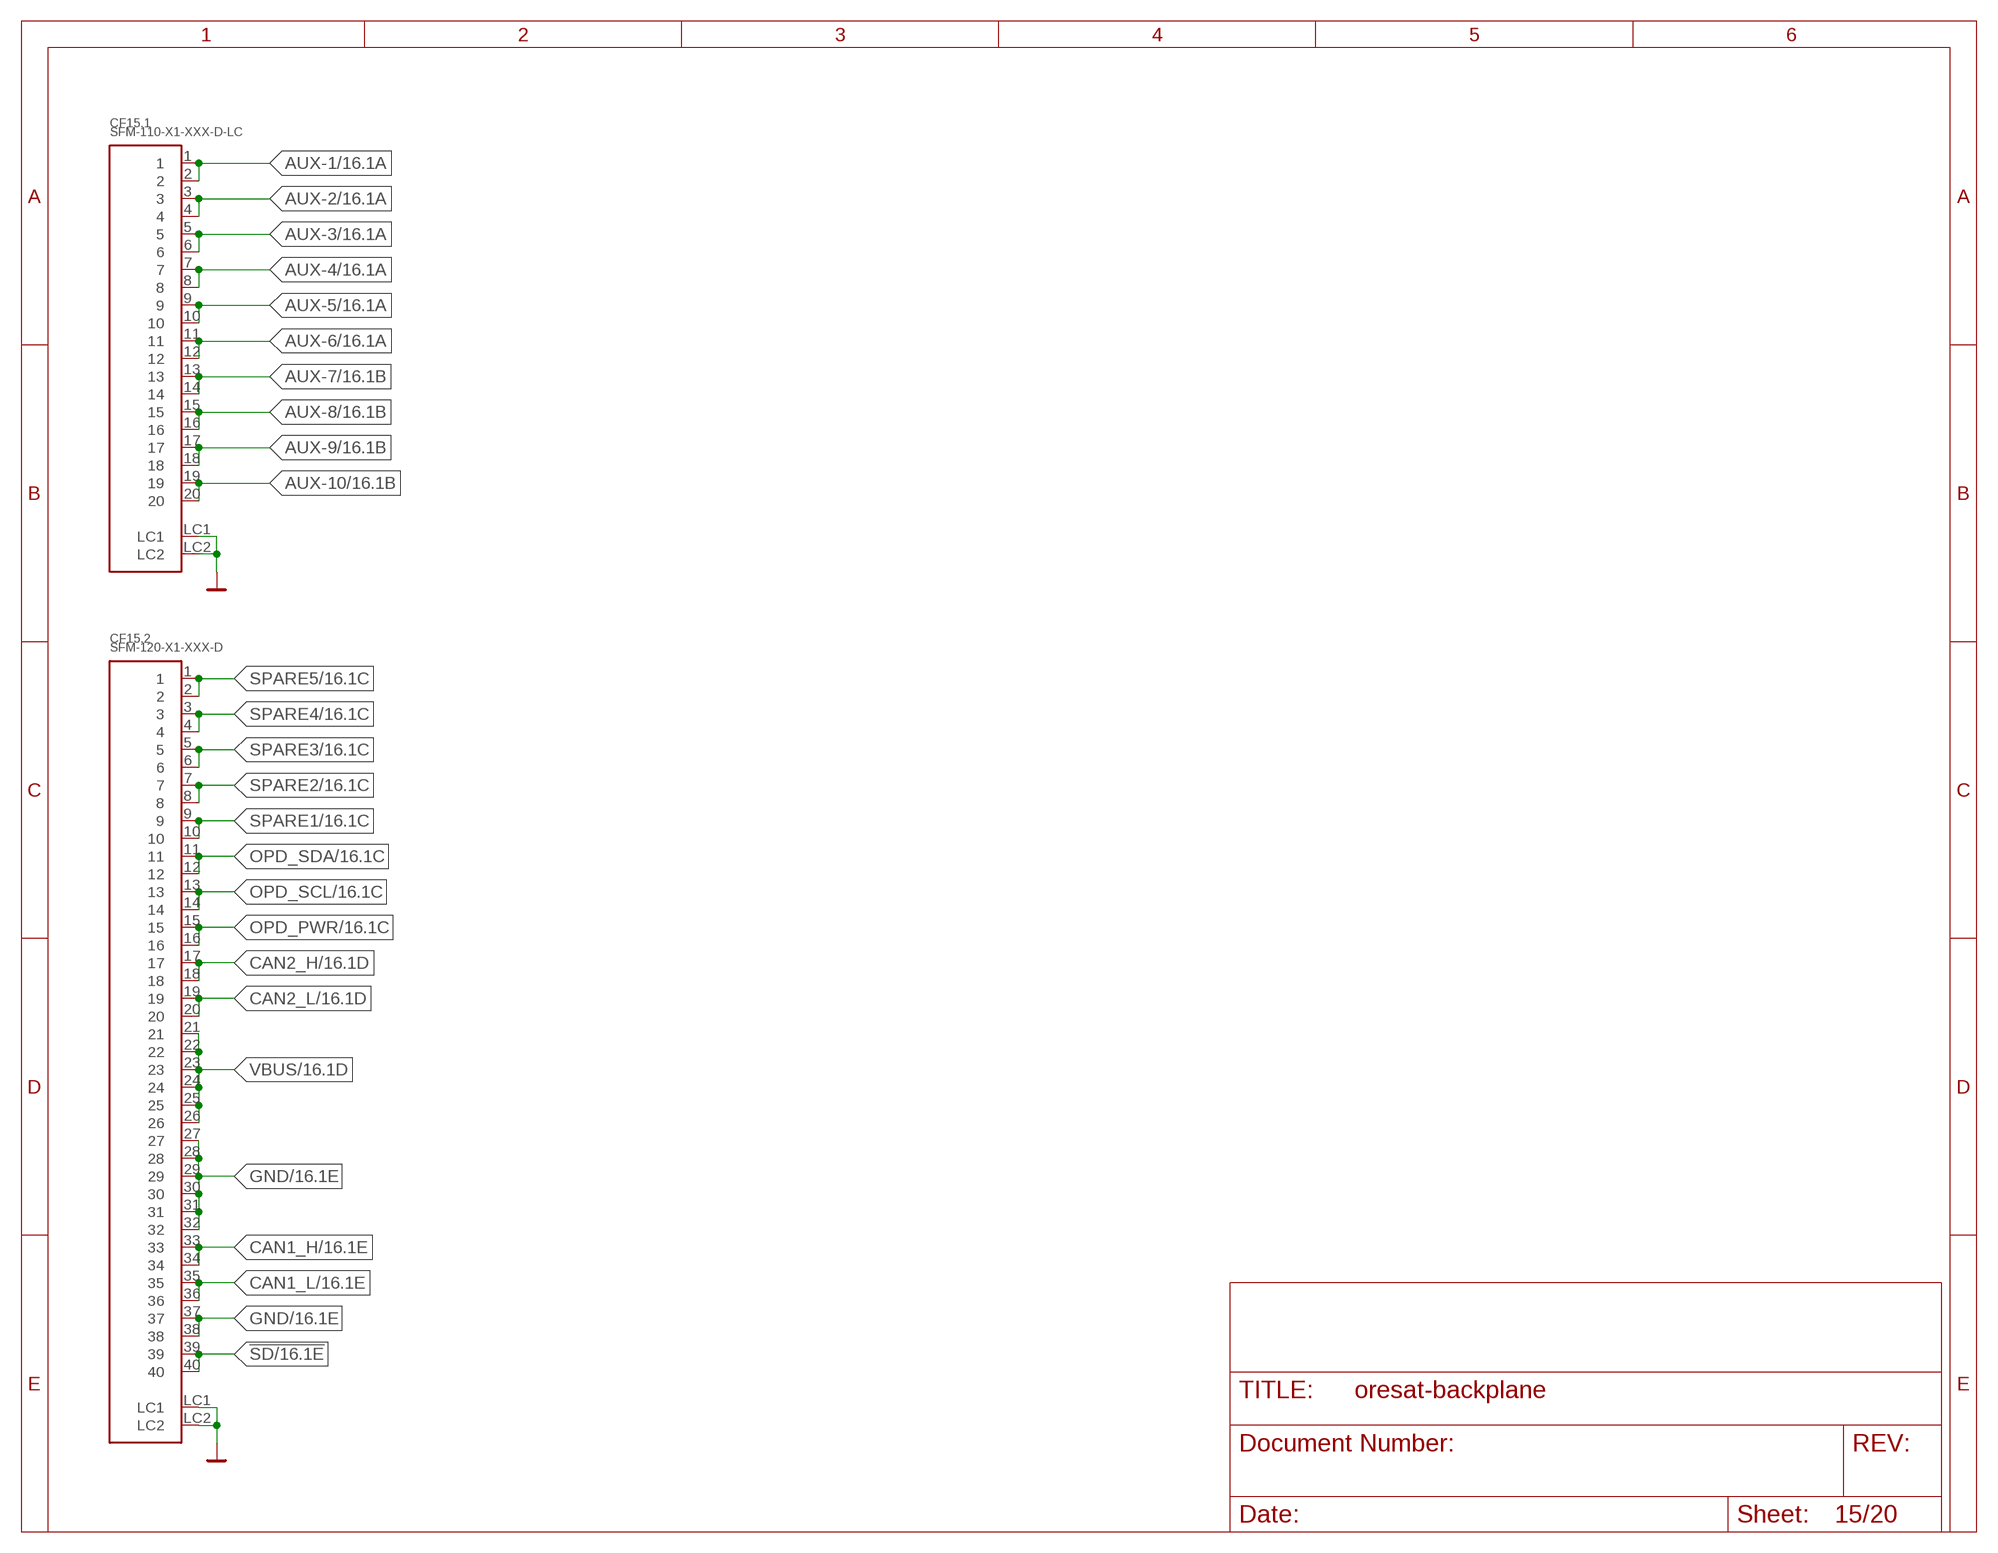
[diagram p14: schematic, sheet 15]
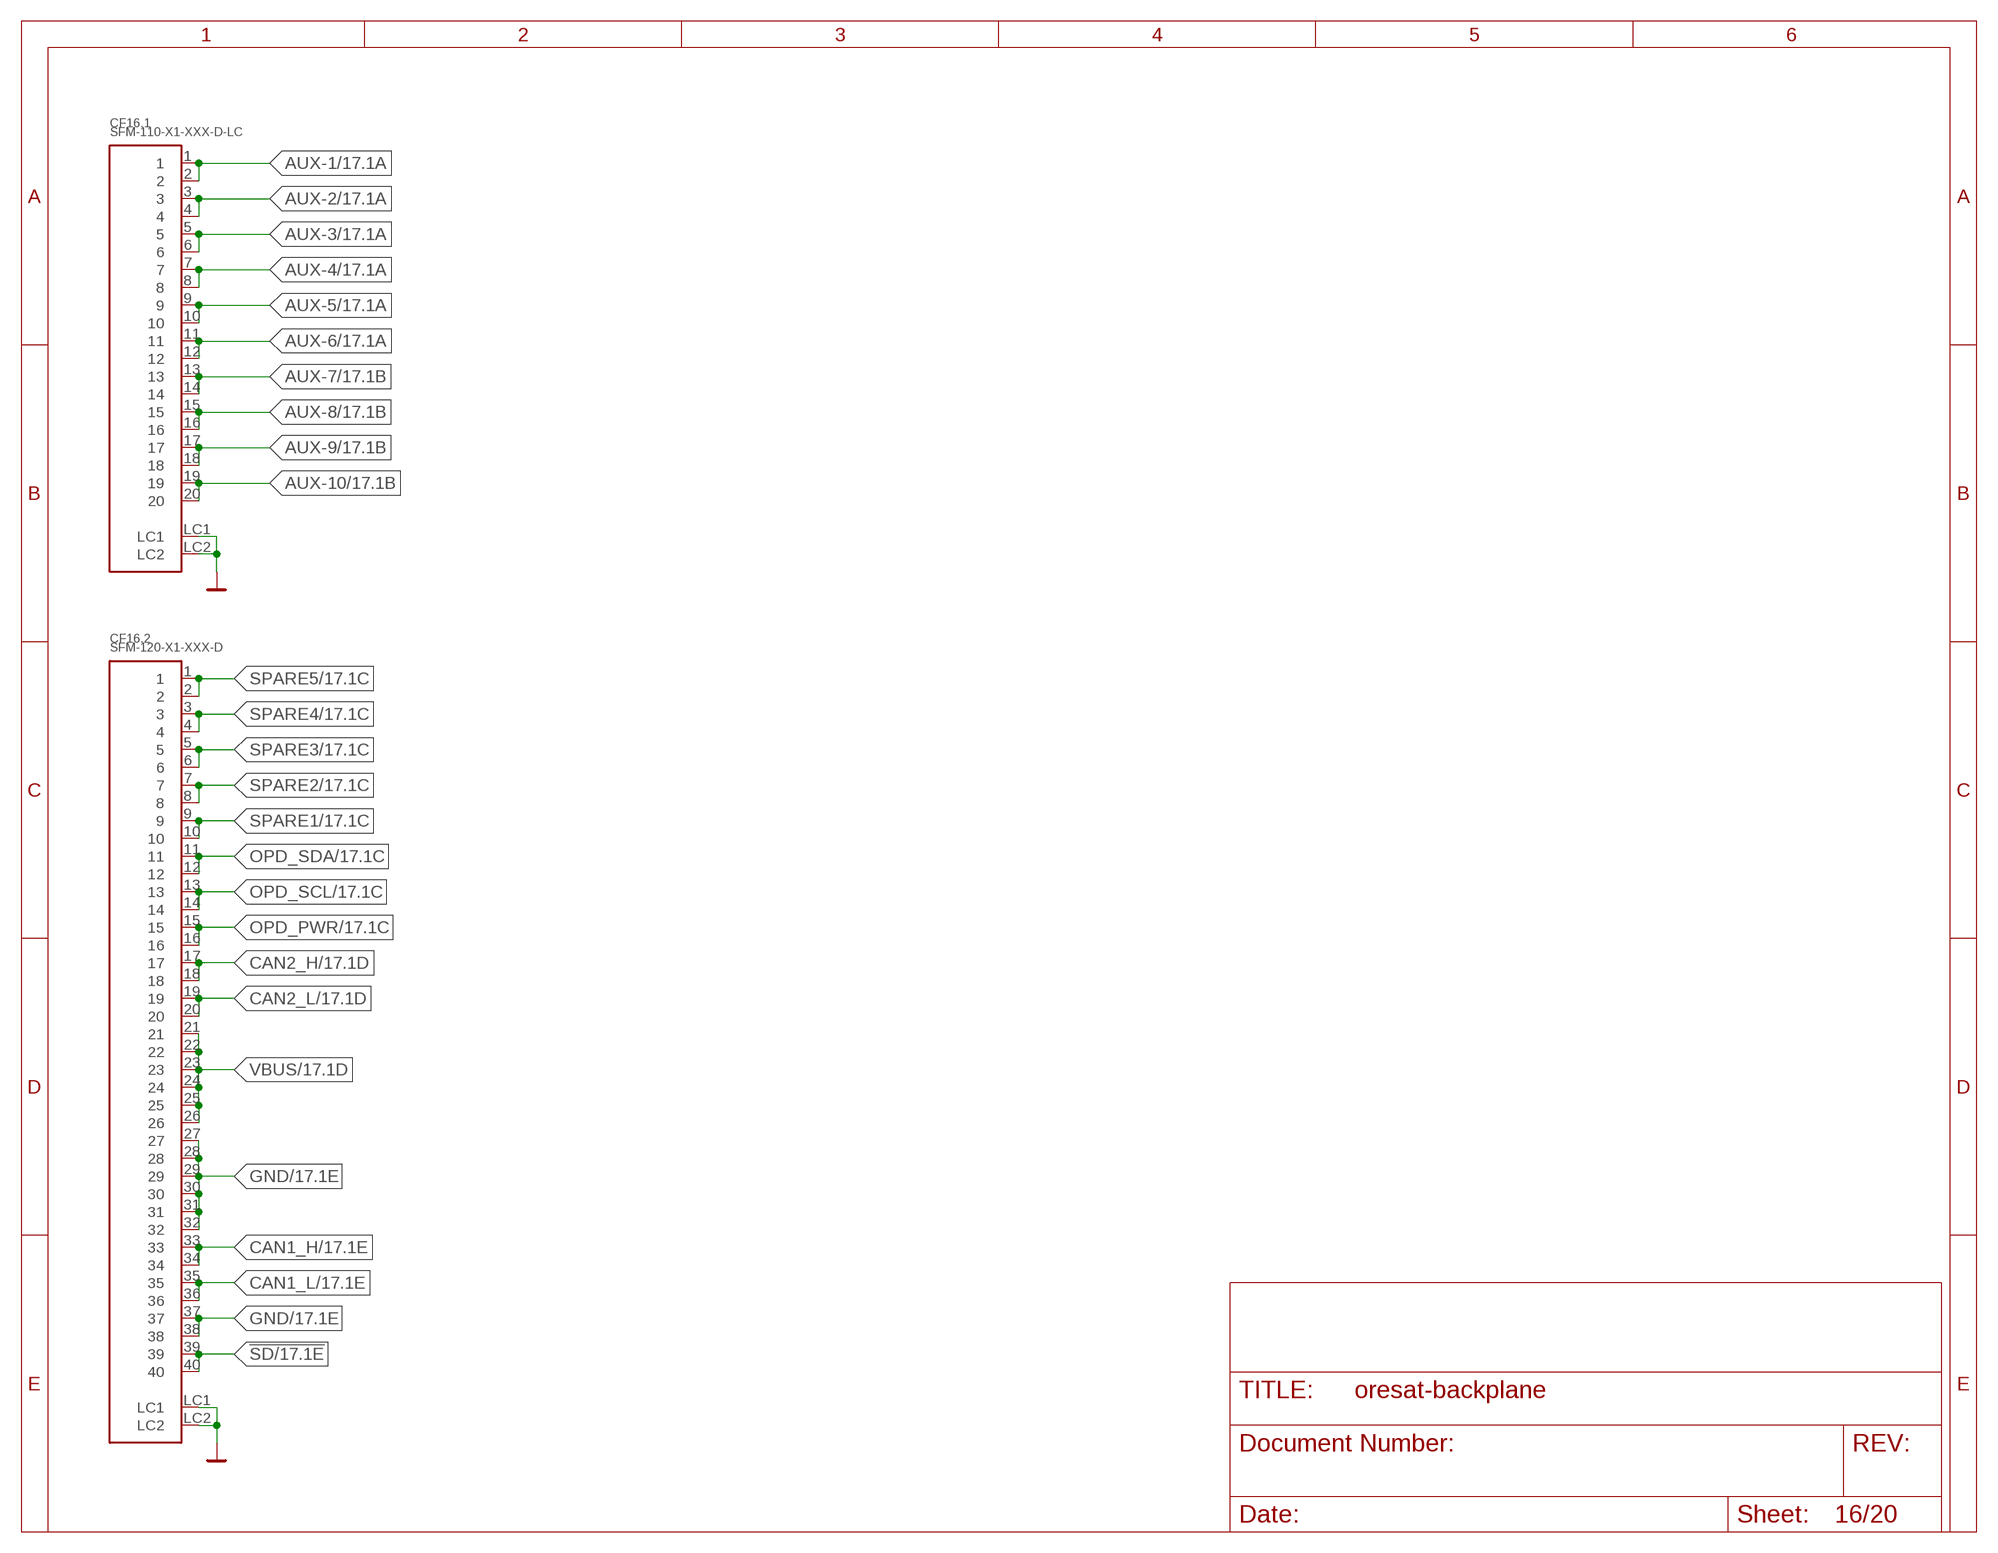
[diagram p15: schematic, sheet 16]
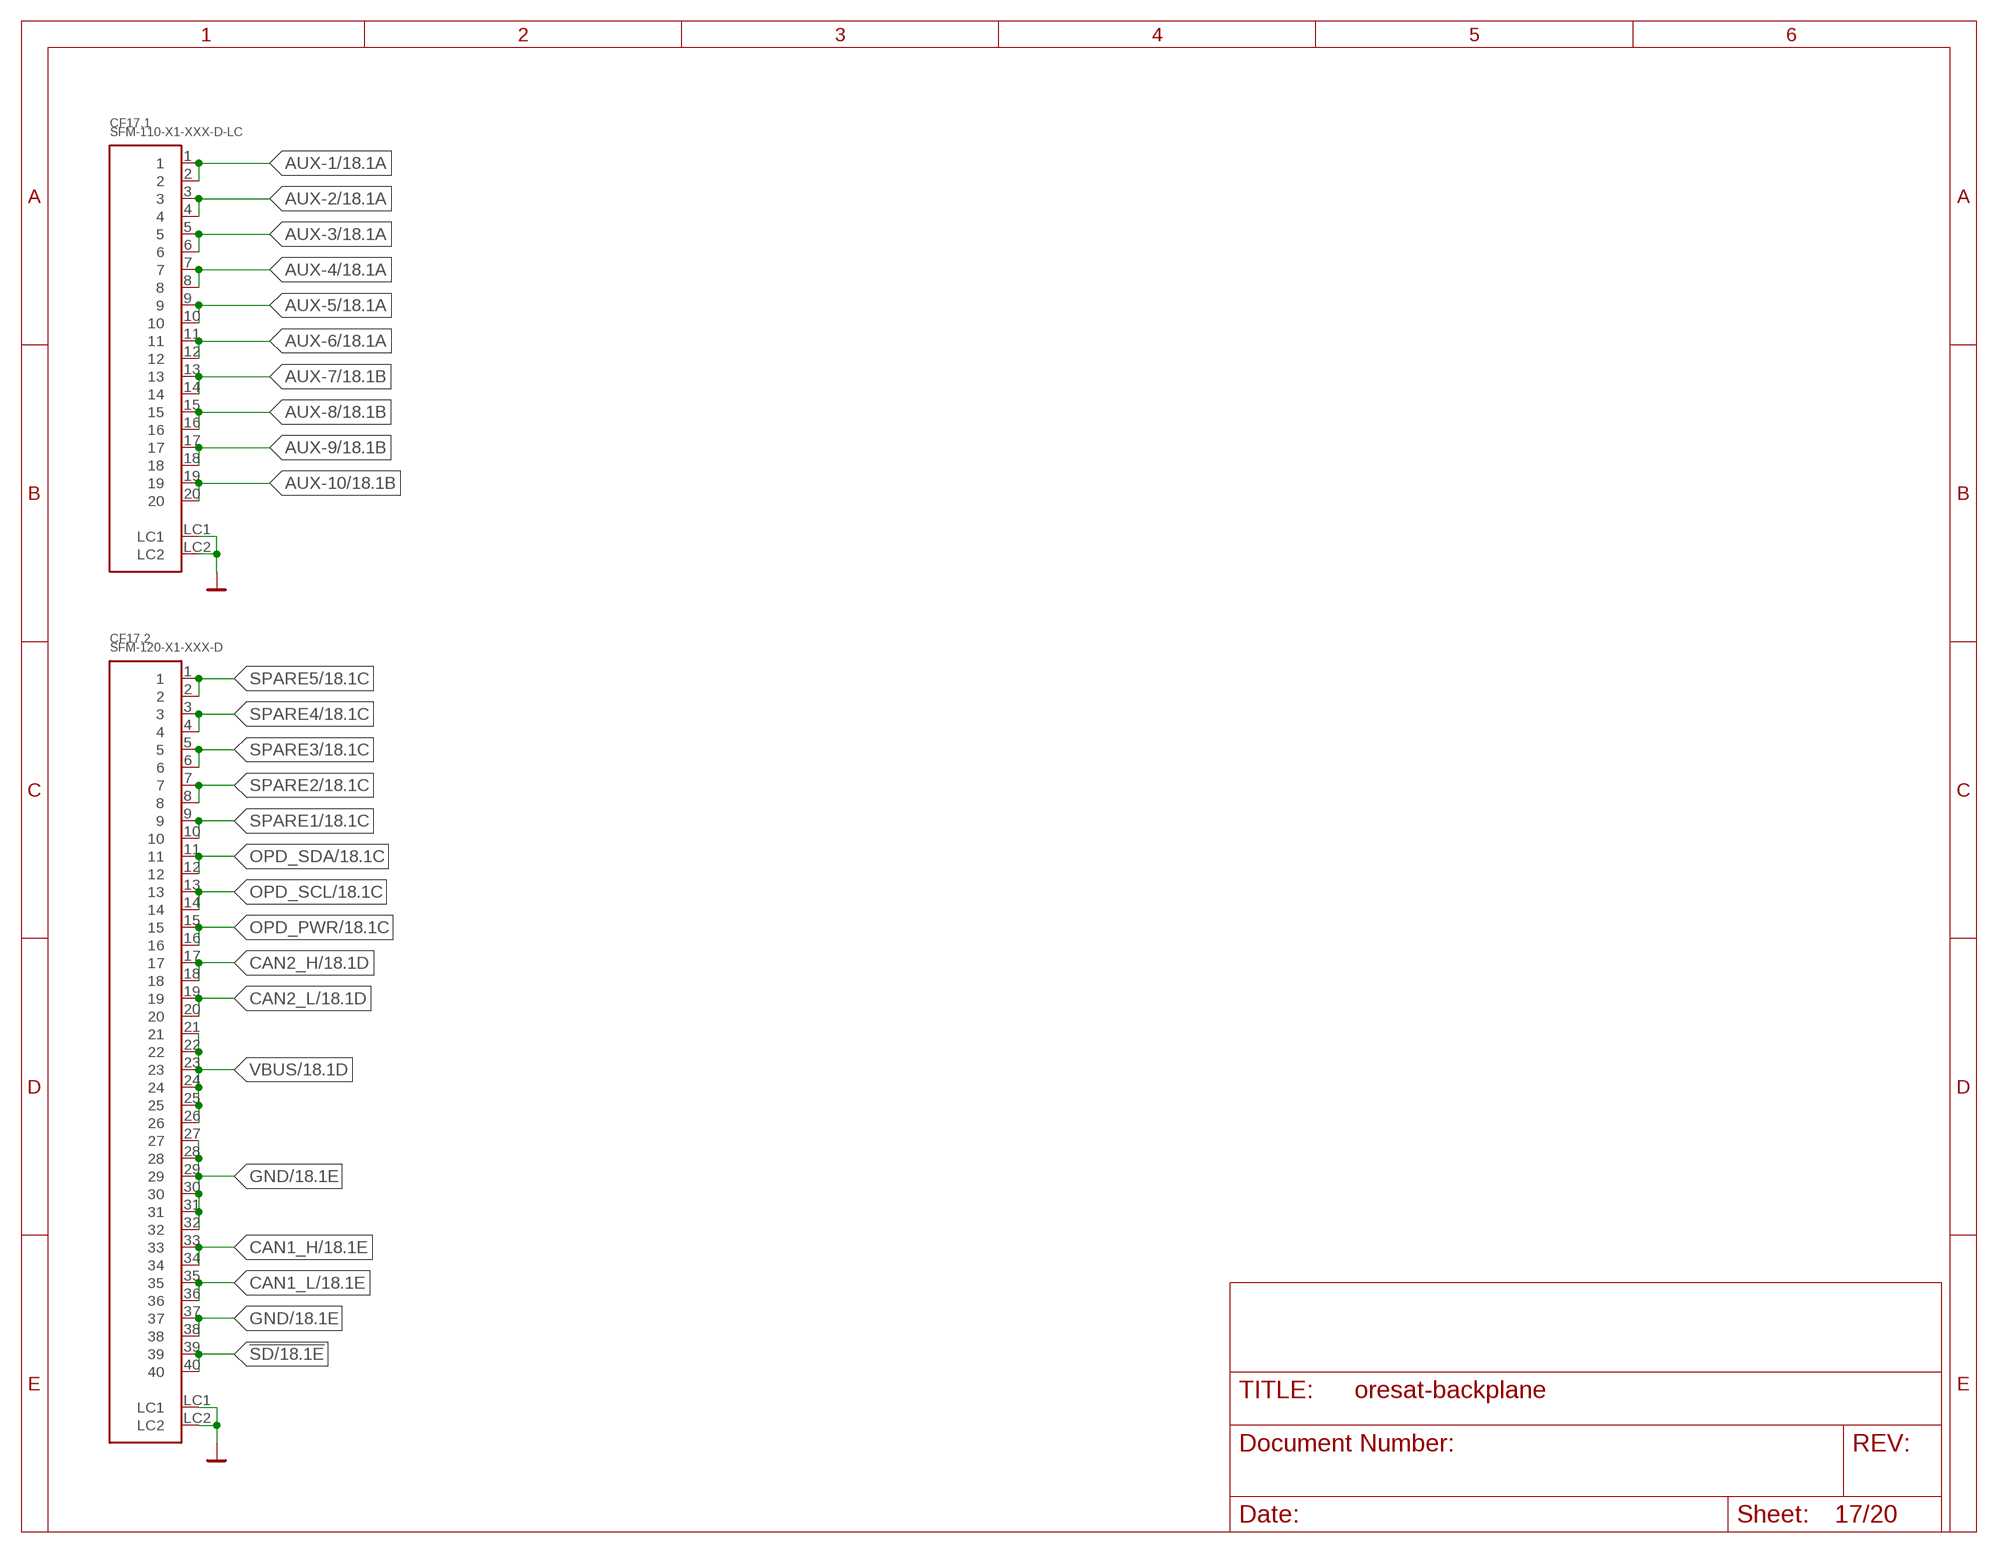
[diagram p16: schematic, sheet 17]
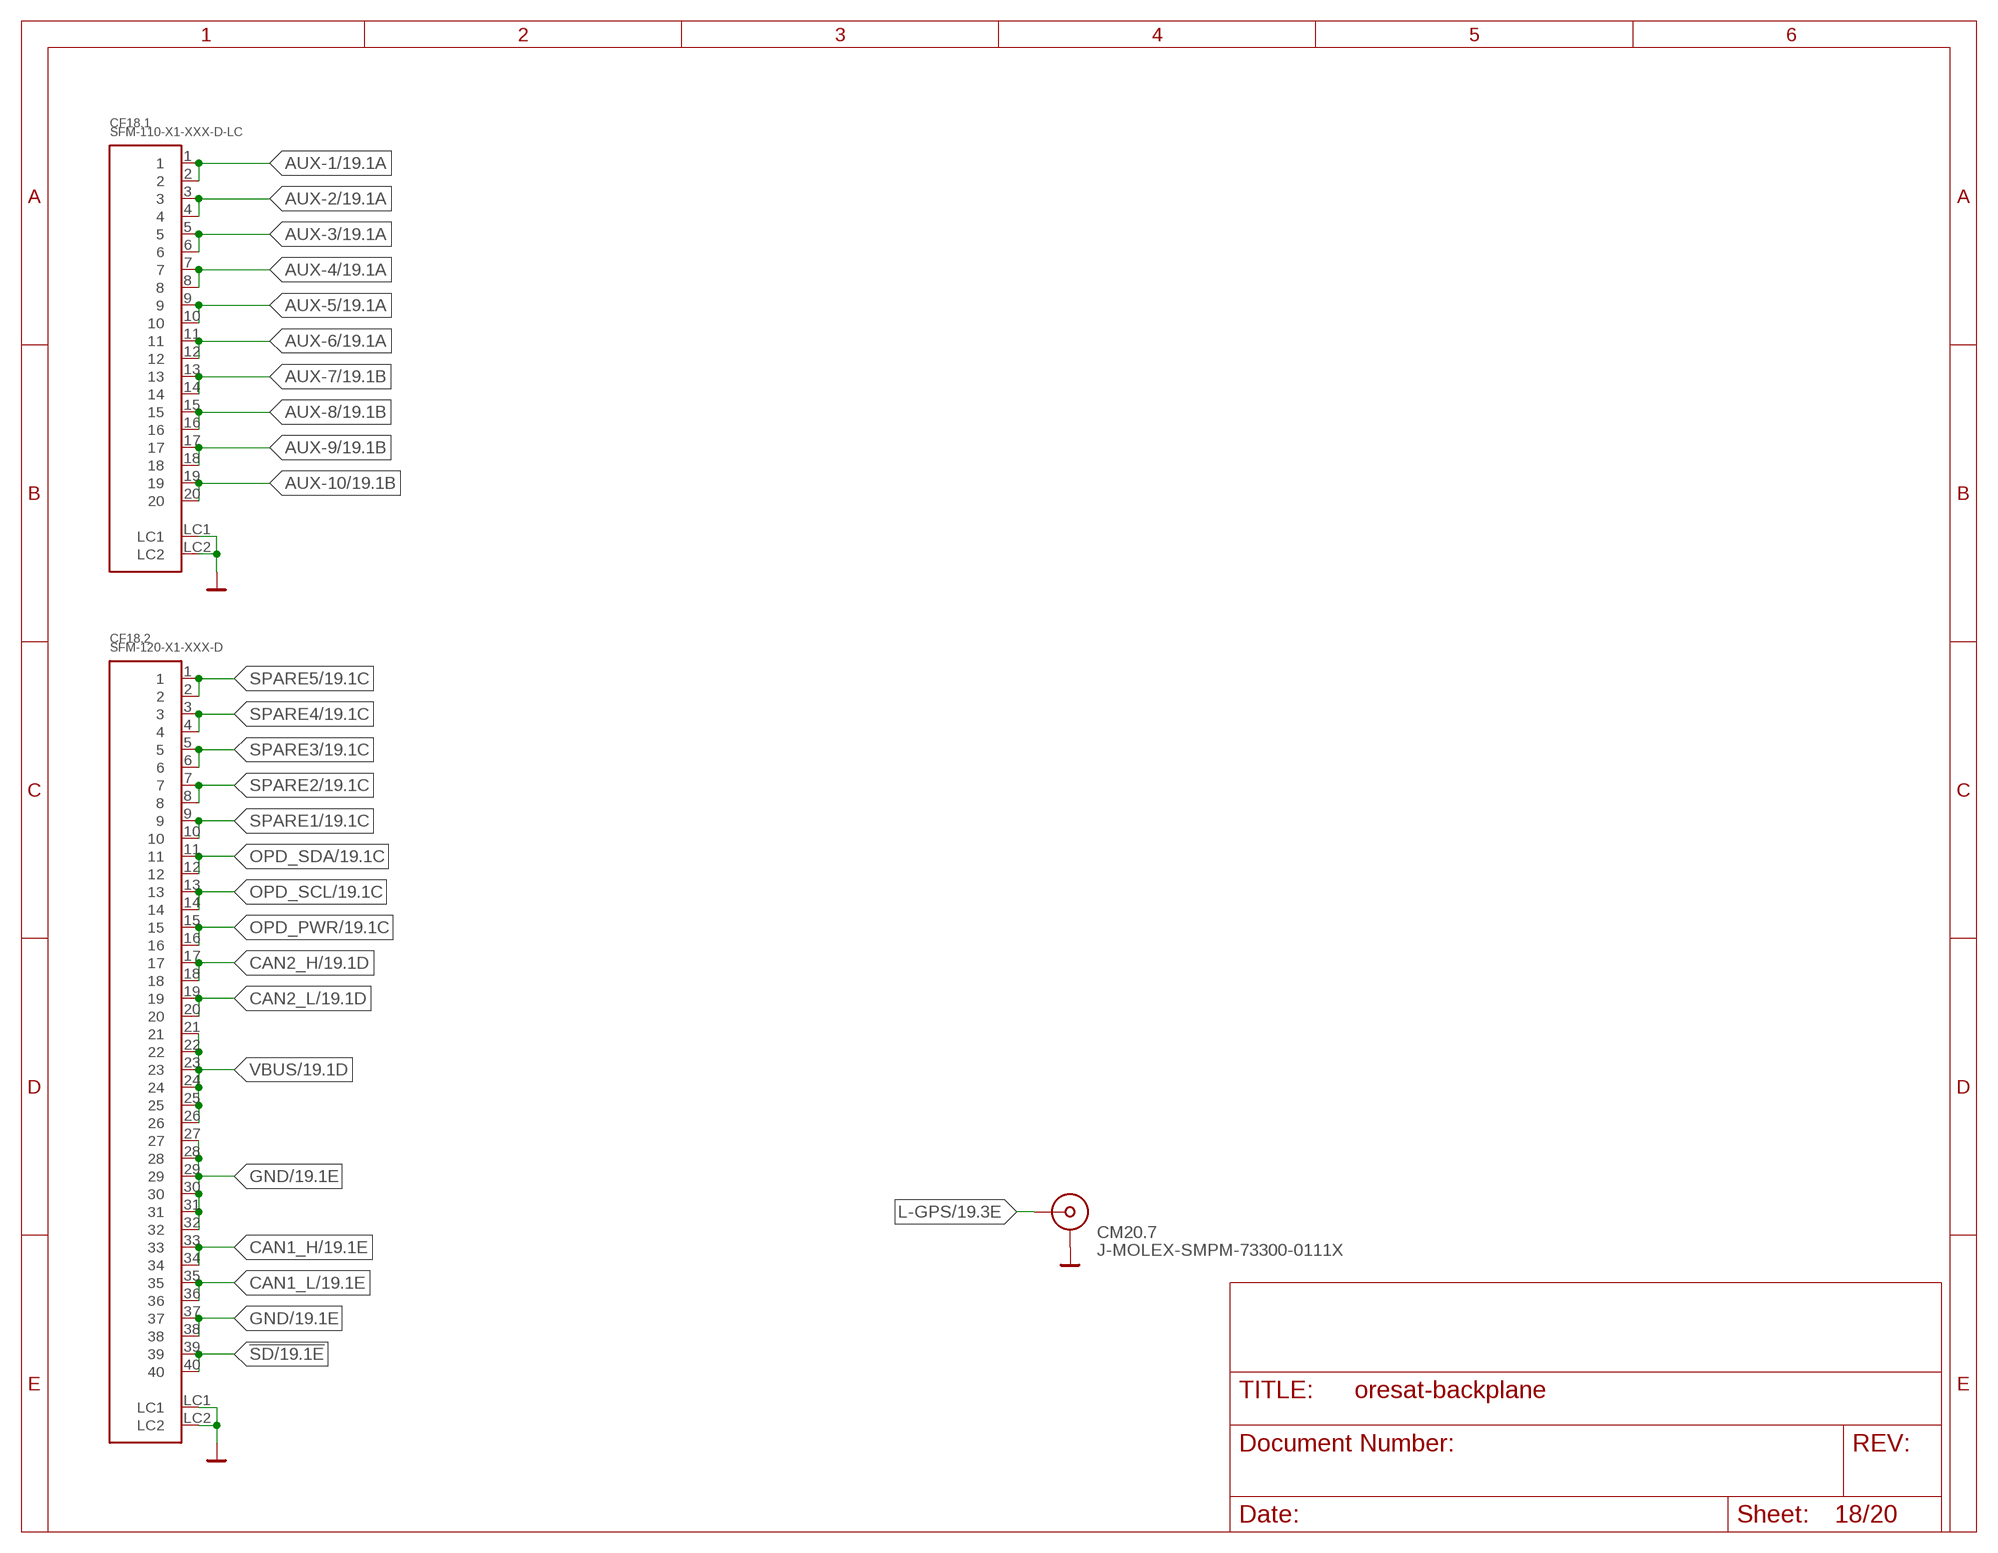
[diagram p17: schematic, sheet 18]
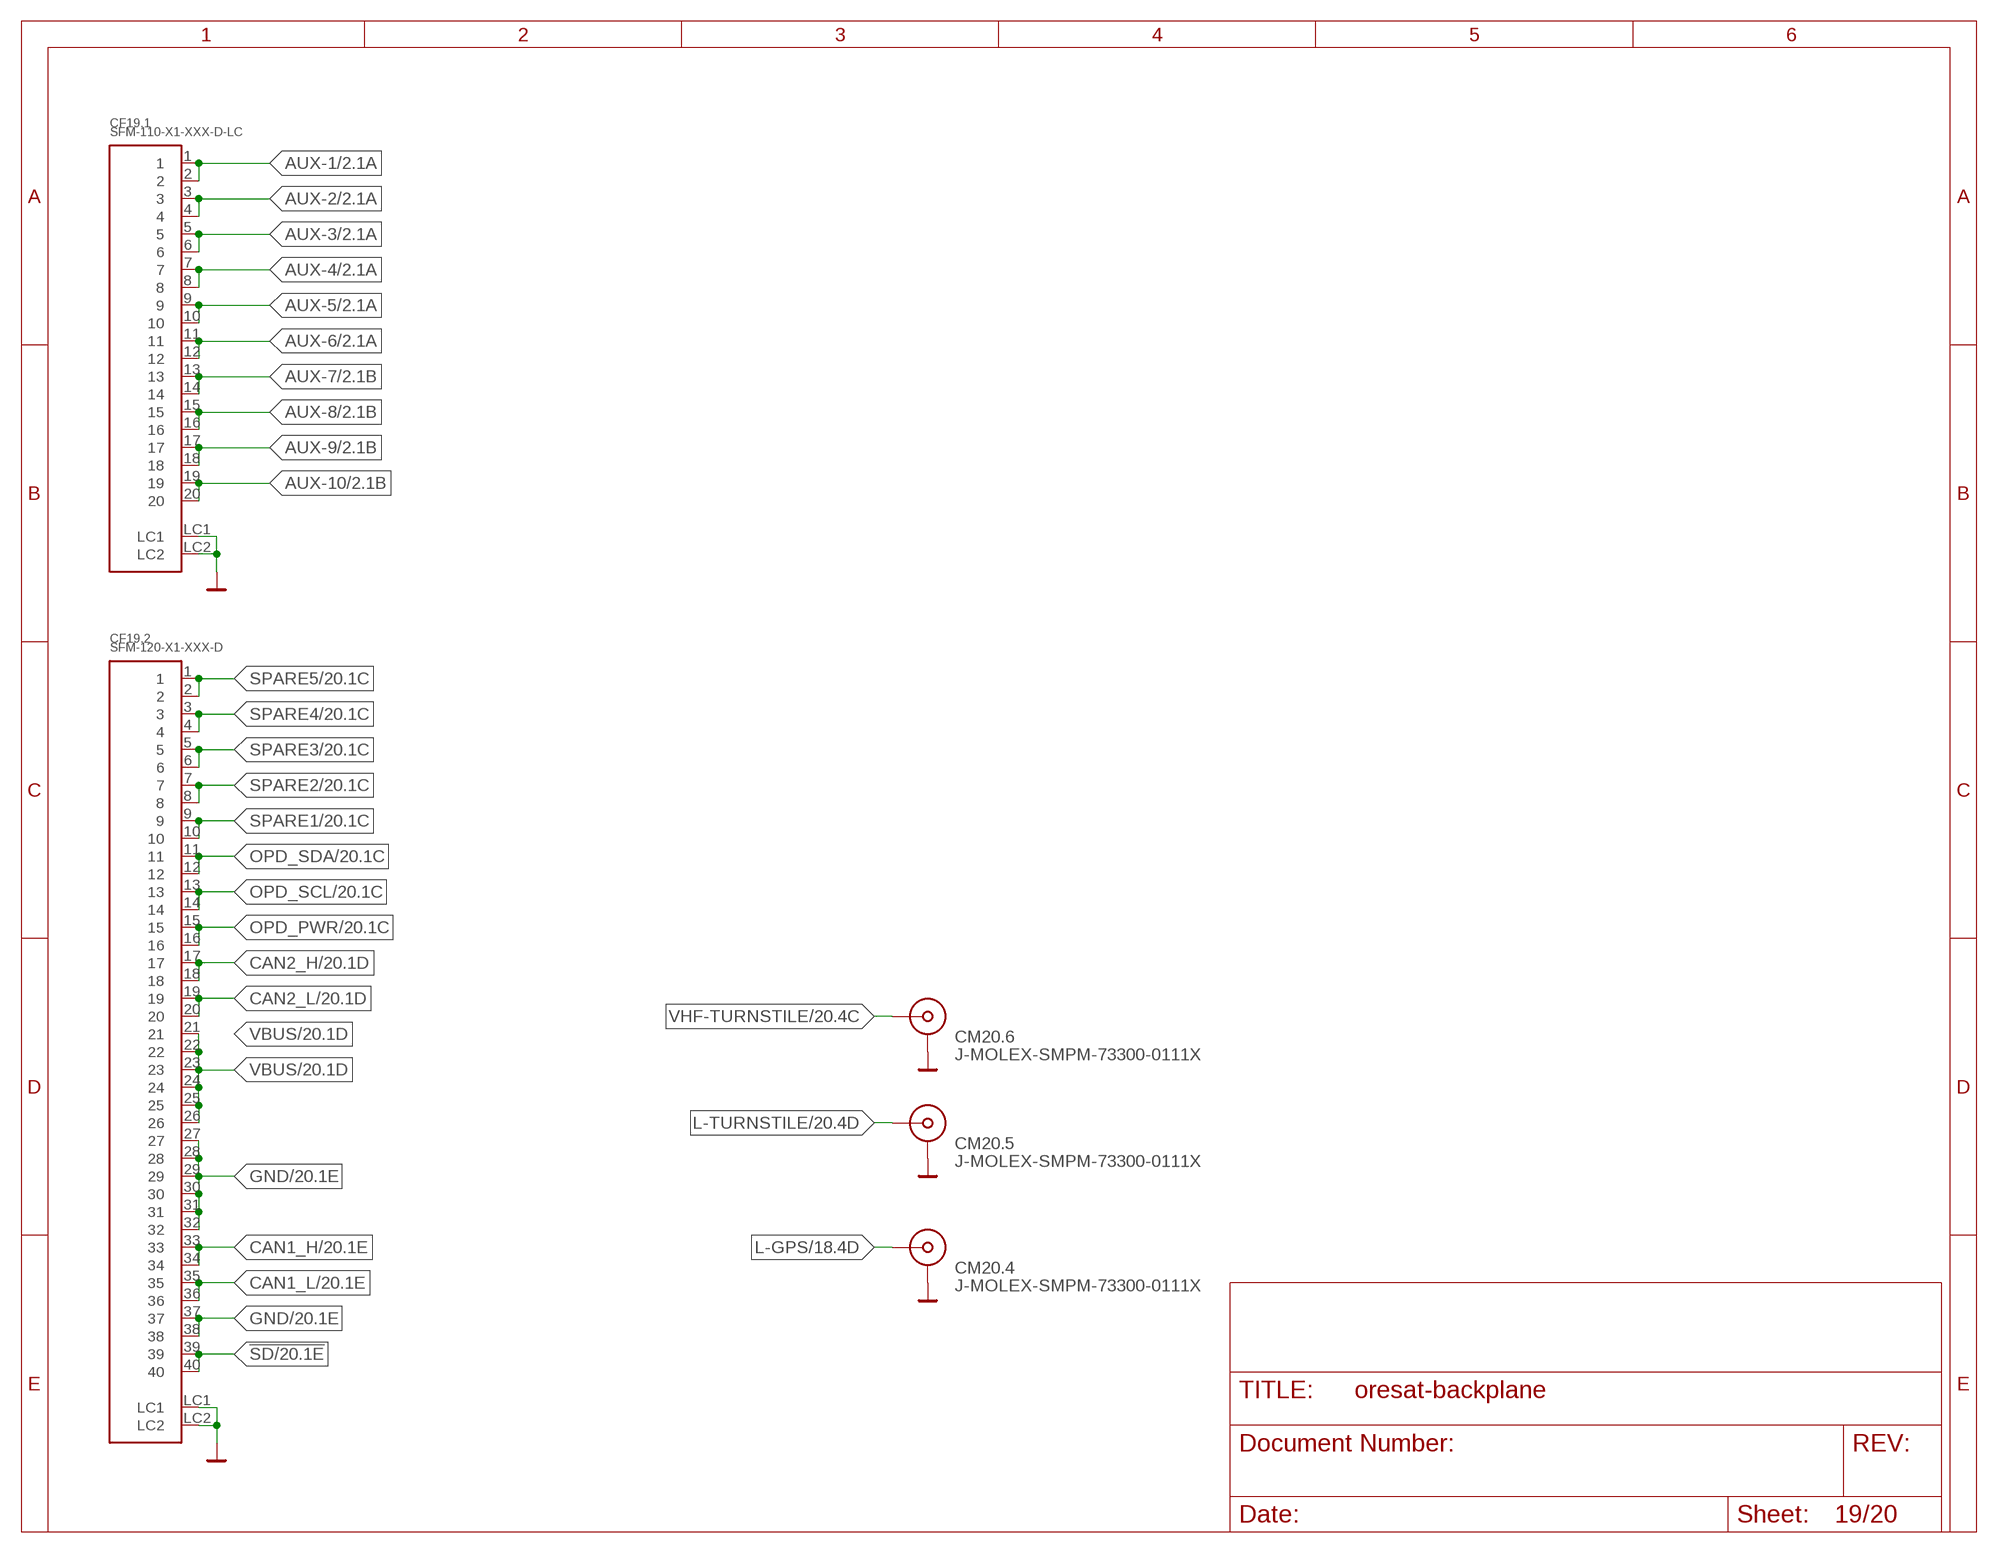
[diagram p18: schematic, sheet 19]
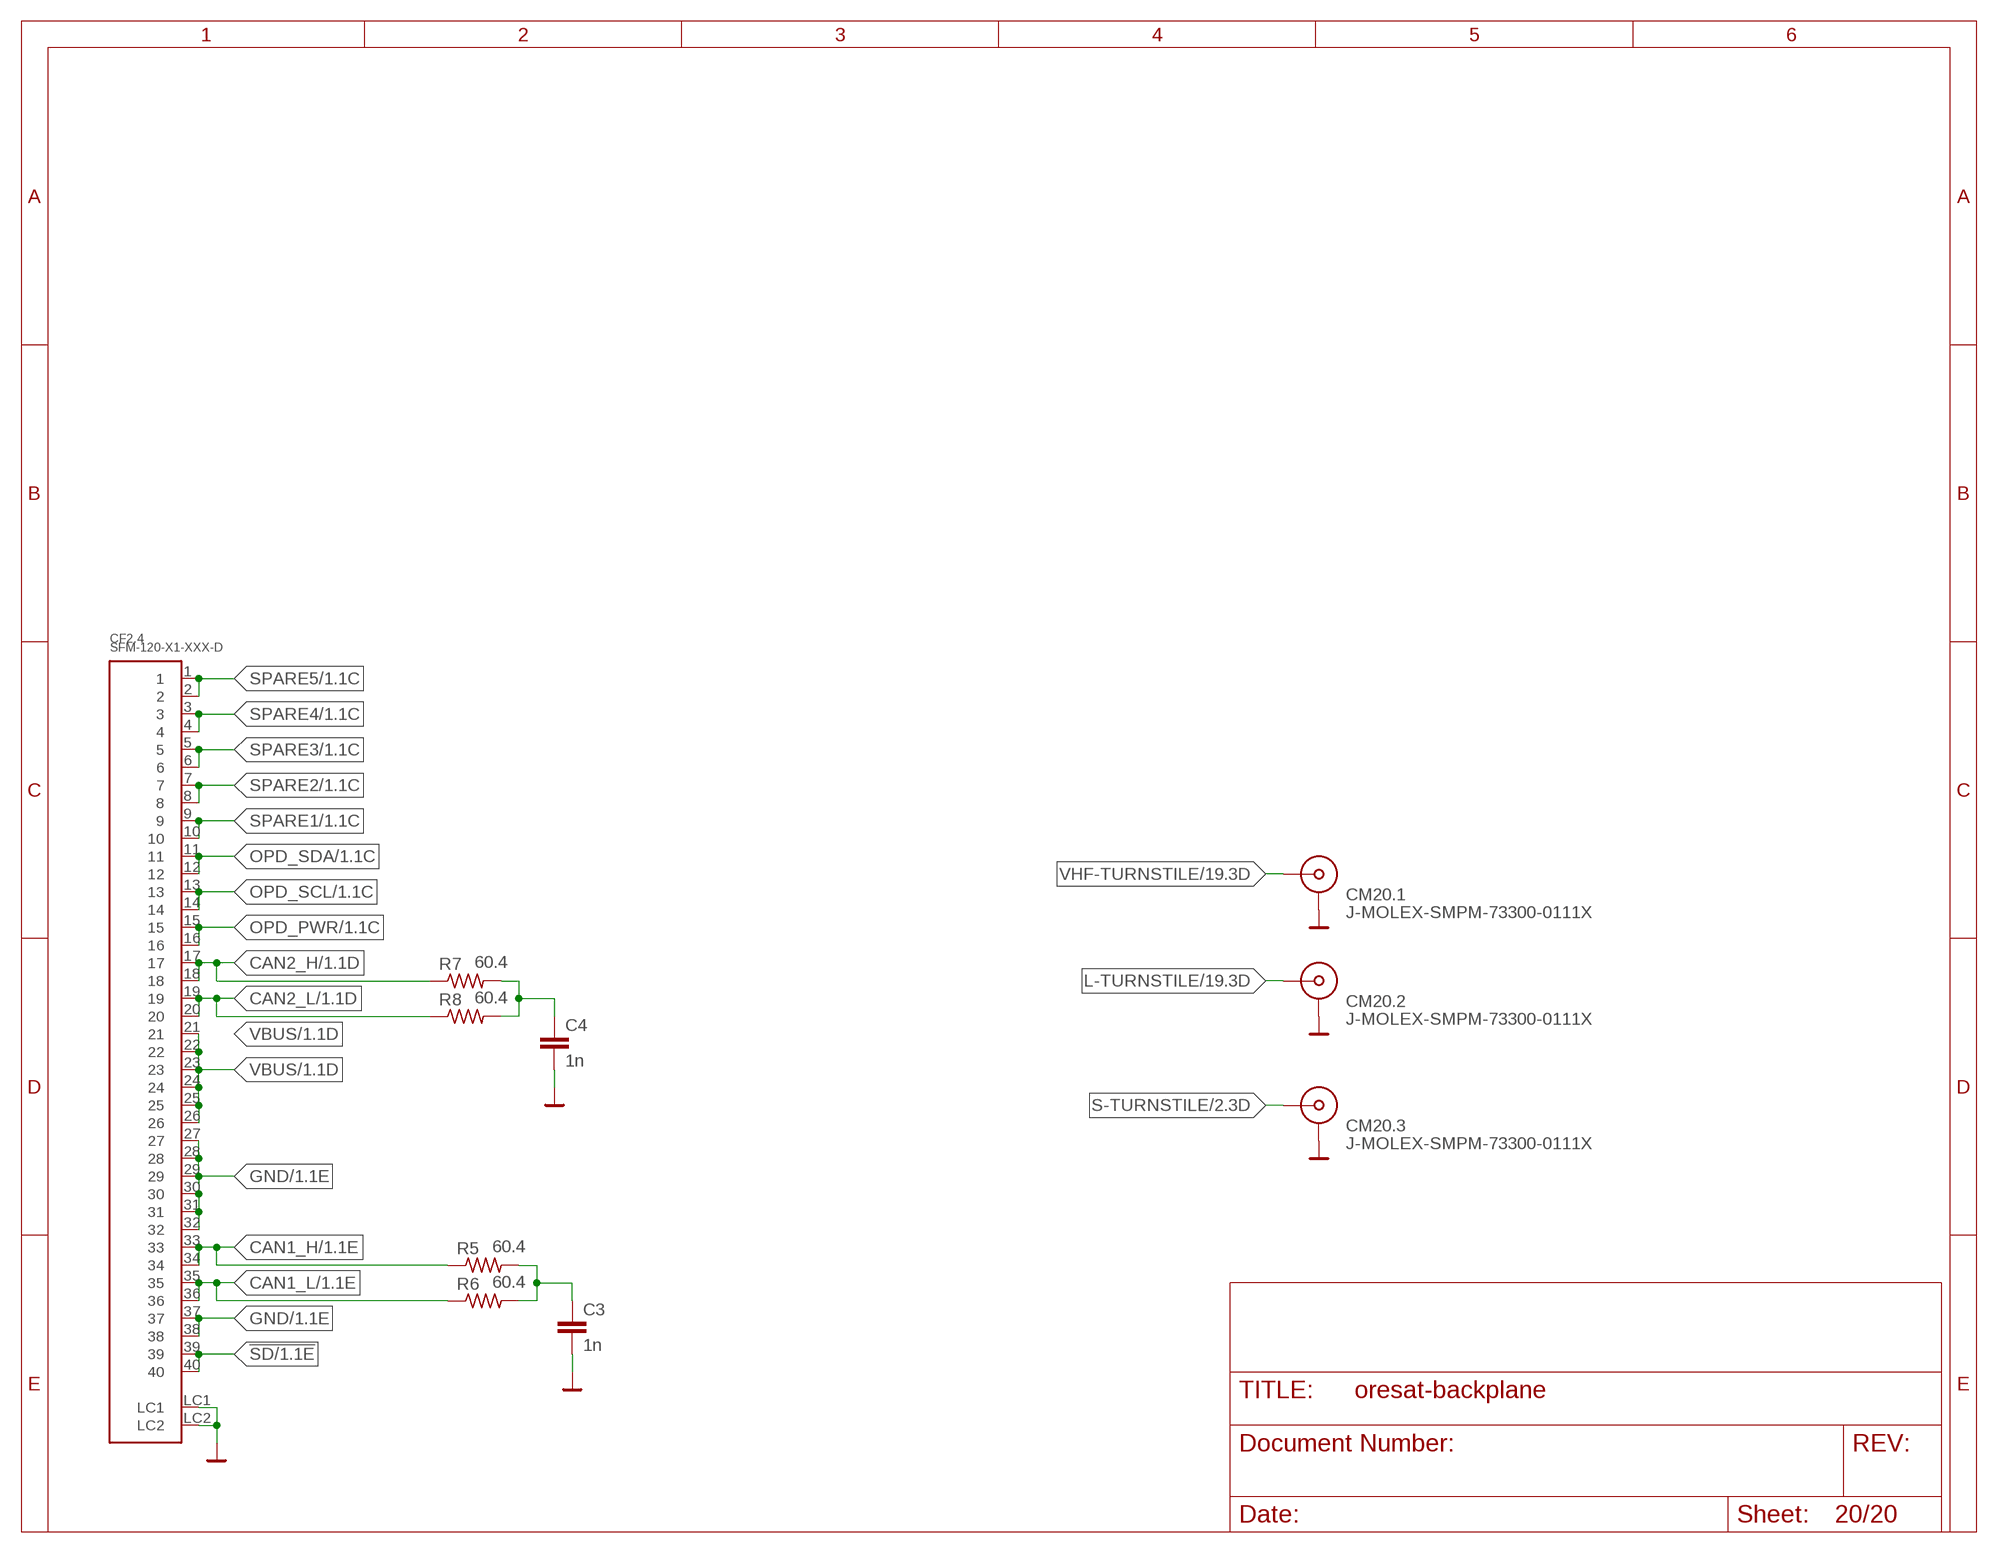
[diagram p19: schematic, sheet 20]

(export (version "E")
  (design (tool "Eeschema 10.0.6"))
  (components
    (comp (ref "CF15.1")
      (value "SFM-110-X1-XXX-D-LC")
      (footprint "eagle-import:SFM-110-X1-XXX-D-LC")
      (libsource (lib "eagle-import") (part "SFM-110-X1-XXX-D-LC"))
    )
    (comp (ref "CF15.2")
      (value "SFM-120-X1-XXX-D")
      (footprint "eagle-import:SFM-120-X1-XXX-D")
      (libsource (lib "eagle-import") (part "SFM-120-X1-XXX-D"))
    )
    (comp (ref "CF3.1")
      (value "SFM-110-X1-XXX-D-LC")
      (footprint "eagle-import:SFM-110-X1-XXX-D-LC")
      (libsource (lib "eagle-import") (part "SFM-110-X1-XXX-D-LC"))
    )
    (comp (ref "CF3.2")
      (value "SFM-120-X1-XXX-D")
      (footprint "eagle-import:SFM-120-X1-XXX-D")
      (libsource (lib "eagle-import") (part "SFM-120-X1-XXX-D"))
    )
    (comp (ref "CF18.1")
      (value "SFM-110-X1-XXX-D-LC")
      (footprint "eagle-import:SFM-110-X1-XXX-D-LC")
      (libsource (lib "eagle-import") (part "SFM-110-X1-XXX-D-LC"))
    )
    (comp (ref "CF18.2")
      (value "SFM-120-X1-XXX-D")
      (footprint "eagle-import:SFM-120-X1-XXX-D")
      (libsource (lib "eagle-import") (part "SFM-120-X1-XXX-D"))
    )
    (comp (ref "CM20.7")
      (value "J-MOLEX-SMPM-73300-0111X")
      (footprint "eagle-import:J-MOLEX-SMPM-73300-0111X")
      (libsource (lib "eagle-import") (part "J-MOLEX-SMPM-73300-0111X"))
    )
    (comp (ref "CF16.1")
      (value "SFM-110-X1-XXX-D-LC")
      (footprint "eagle-import:SFM-110-X1-XXX-D-LC")
      (libsource (lib "eagle-import") (part "SFM-110-X1-XXX-D-LC"))
    )
    (comp (ref "CF16.2")
      (value "SFM-120-X1-XXX-D")
      (footprint "eagle-import:SFM-120-X1-XXX-D")
      (libsource (lib "eagle-import") (part "SFM-120-X1-XXX-D"))
    )
    (comp (ref "CF14.1")
      (value "SFM-110-X1-XXX-D-LC")
      (footprint "eagle-import:SFM-110-X1-XXX-D-LC")
      (libsource (lib "eagle-import") (part "SFM-110-X1-XXX-D-LC"))
    )
    (comp (ref "CF14.2")
      (value "SFM-120-X1-XXX-D")
      (footprint "eagle-import:SFM-120-X1-XXX-D")
      (libsource (lib "eagle-import") (part "SFM-120-X1-XXX-D"))
    )
    (comp (ref "CF19.1")
      (value "SFM-110-X1-XXX-D-LC")
      (footprint "eagle-import:SFM-110-X1-XXX-D-LC")
      (libsource (lib "eagle-import") (part "SFM-110-X1-XXX-D-LC"))
    )
    (comp (ref "CF19.2")
      (value "SFM-120-X1-XXX-D")
      (footprint "eagle-import:SFM-120-X1-XXX-D")
      (libsource (lib "eagle-import") (part "SFM-120-X1-XXX-D"))
    )
    (comp (ref "CM20.4")
      (value "J-MOLEX-SMPM-73300-0111X")
      (footprint "eagle-import:J-MOLEX-SMPM-73300-0111X")
      (libsource (lib "eagle-import") (part "J-MOLEX-SMPM-73300-0111X"))
    )
    (comp (ref "CM20.5")
      (value "J-MOLEX-SMPM-73300-0111X")
      (footprint "eagle-import:J-MOLEX-SMPM-73300-0111X")
      (libsource (lib "eagle-import") (part "J-MOLEX-SMPM-73300-0111X"))
    )
    (comp (ref "CM20.6")
      (value "J-MOLEX-SMPM-73300-0111X")
      (footprint "eagle-import:J-MOLEX-SMPM-73300-0111X")
      (libsource (lib "eagle-import") (part "J-MOLEX-SMPM-73300-0111X"))
    )
    (comp (ref "CF6.1")
      (value "SFM-110-X1-XXX-D-LC")
      (footprint "eagle-import:SFM-110-X1-XXX-D-LC")
      (libsource (lib "eagle-import") (part "SFM-110-X1-XXX-D-LC"))
    )
    (comp (ref "CF6.2")
      (value "SFM-120-X1-XXX-D")
      (footprint "eagle-import:SFM-120-X1-XXX-D")
      (libsource (lib "eagle-import") (part "SFM-120-X1-XXX-D"))
    )
    (comp (ref "CF2.1")
      (value "SFM-110-X1-XXX-D-LC")
      (footprint "eagle-import:SFM-110-X1-XXX-D-LC")
      (libsource (lib "eagle-import") (part "SFM-110-X1-XXX-D-LC"))
    )
    (comp (ref "CF2.2")
      (value "SFM-120-X1-XXX-D")
      (footprint "eagle-import:SFM-120-X1-XXX-D")
      (libsource (lib "eagle-import") (part "SFM-120-X1-XXX-D"))
    )
    (comp (ref "CM2.1")
      (value "J-MOLEX-SMPM-73300-0111X")
      (footprint "eagle-import:J-MOLEX-SMPM-73300-0111X")
      (libsource (lib "eagle-import") (part "J-MOLEX-SMPM-73300-0111X"))
    )
    (comp (ref "CM2.2")
      (value "J-MOLEX-SMPM-73300-0111X")
      (footprint "eagle-import:J-MOLEX-SMPM-73300-0111X")
      (libsource (lib "eagle-import") (part "J-MOLEX-SMPM-73300-0111X"))
    )
    (comp (ref "CF5.1")
      (value "SFM-110-X1-XXX-D-LC")
      (footprint "eagle-import:SFM-110-X1-XXX-D-LC")
      (libsource (lib "eagle-import") (part "SFM-110-X1-XXX-D-LC"))
    )
    (comp (ref "CF5.2")
      (value "SFM-120-X1-XXX-D")
      (footprint "eagle-import:SFM-120-X1-XXX-D")
      (libsource (lib "eagle-import") (part "SFM-120-X1-XXX-D"))
    )
    (comp (ref "CF8.1")
      (value "SFM-110-X1-XXX-D-LC")
      (footprint "eagle-import:SFM-110-X1-XXX-D-LC")
      (libsource (lib "eagle-import") (part "SFM-110-X1-XXX-D-LC"))
    )
    (comp (ref "CF8.2")
      (value "SFM-120-X1-XXX-D")
      (footprint "eagle-import:SFM-120-X1-XXX-D")
      (libsource (lib "eagle-import") (part "SFM-120-X1-XXX-D"))
    )
    (comp (ref "CF12.1")
      (value "SFM-110-X1-XXX-D-LC")
      (footprint "eagle-import:SFM-110-X1-XXX-D-LC")
      (libsource (lib "eagle-import") (part "SFM-110-X1-XXX-D-LC"))
    )
    (comp (ref "CF12.2")
      (value "SFM-120-X1-XXX-D")
      (footprint "eagle-import:SFM-120-X1-XXX-D")
      (libsource (lib "eagle-import") (part "SFM-120-X1-XXX-D"))
    )
    (comp (ref "C3")
      (value "1n")
      (footprint "eagle-import:.0603-C-NOSILK")
      (libsource (lib "eagle-import") (part "C-EU0603-C-NOSILK"))
    )
    (comp (ref "C4")
      (value "1n")
      (footprint "eagle-import:.0603-C-NOSILK")
      (libsource (lib "eagle-import") (part "C-EU0603-C-NOSILK"))
    )
    (comp (ref "CF2.4")
      (value "SFM-120-X1-XXX-D")
      (footprint "eagle-import:SFM-120-X1-XXX-D")
      (libsource (lib "eagle-import") (part "SFM-120-X1-XXX-D"))
    )
    (comp (ref "CM20.1")
      (value "J-MOLEX-SMPM-73300-0111X")
      (footprint "eagle-import:J-MOLEX-SMPM-73300-0111X")
      (libsource (lib "eagle-import") (part "J-MOLEX-SMPM-73300-0111X"))
    )
    (comp (ref "CM20.2")
      (value "J-MOLEX-SMPM-73300-0111X")
      (footprint "eagle-import:J-MOLEX-SMPM-73300-0111X")
      (libsource (lib "eagle-import") (part "J-MOLEX-SMPM-73300-0111X"))
    )
    (comp (ref "CM20.3")
      (value "J-MOLEX-SMPM-73300-0111X")
      (footprint "eagle-import:J-MOLEX-SMPM-73300-0111X")
      (libsource (lib "eagle-import") (part "J-MOLEX-SMPM-73300-0111X"))
    )
    (comp (ref "R5")
      (value "60.4")
      (footprint "eagle-import:1206-C")
      (libsource (lib "eagle-import") (part "R-US_1206-C"))
    )
    (comp (ref "R6")
      (value "60.4")
      (footprint "eagle-import:1206-C")
      (libsource (lib "eagle-import") (part "R-US_1206-C"))
    )
    (comp (ref "R7")
      (value "60.4")
      (footprint "eagle-import:1206-C")
      (libsource (lib "eagle-import") (part "R-US_1206-C"))
    )
    (comp (ref "R8")
      (value "60.4")
      (footprint "eagle-import:1206-C")
      (libsource (lib "eagle-import") (part "R-US_1206-C"))
    )
    (comp (ref "CF17.1")
      (value "SFM-110-X1-XXX-D-LC")
      (footprint "eagle-import:SFM-110-X1-XXX-D-LC")
      (libsource (lib "eagle-import") (part "SFM-110-X1-XXX-D-LC"))
    )
    (comp (ref "CF17.2")
      (value "SFM-120-X1-XXX-D")
      (footprint "eagle-import:SFM-120-X1-XXX-D")
      (libsource (lib "eagle-import") (part "SFM-120-X1-XXX-D"))
    )
    (comp (ref "C1")
      (value "1n")
      (footprint "eagle-import:.0603-C-NOSILK")
      (libsource (lib "eagle-import") (part "C-EU0603-C-NOSILK"))
    )
    (comp (ref "C2")
      (value "1n")
      (footprint "eagle-import:.0603-C-NOSILK")
      (libsource (lib "eagle-import") (part "C-EU0603-C-NOSILK"))
    )
    (comp (ref "CF2.3")
      (value "SFM-120-X1-XXX-D")
      (footprint "eagle-import:SFM-120-X1-XXX-D")
      (libsource (lib "eagle-import") (part "SFM-120-X1-XXX-D"))
    )
    (comp (ref "CM1.1")
      (value "J-MOLEX-SMPM-73300-0111X")
      (footprint "eagle-import:J-MOLEX-SMPM-73300-0111X")
      (libsource (lib "eagle-import") (part "J-MOLEX-SMPM-73300-0111X"))
    )
    (comp (ref "R1")
      (value "60.4")
      (footprint "eagle-import:1206-C")
      (libsource (lib "eagle-import") (part "R-US_1206-C"))
    )
    (comp (ref "R2")
      (value "60.4")
      (footprint "eagle-import:1206-C")
      (libsource (lib "eagle-import") (part "R-US_1206-C"))
    )
    (comp (ref "R3")
      (value "60.4")
      (footprint "eagle-import:1206-C")
      (libsource (lib "eagle-import") (part "R-US_1206-C"))
    )
    (comp (ref "R4")
      (value "60.4")
      (footprint "eagle-import:1206-C")
      (libsource (lib "eagle-import") (part "R-US_1206-C"))
    )
    (comp (ref "CF13.1")
      (value "SFM-110-X1-XXX-D-LC")
      (footprint "eagle-import:SFM-110-X1-XXX-D-LC")
      (libsource (lib "eagle-import") (part "SFM-110-X1-XXX-D-LC"))
    )
    (comp (ref "CF13.2")
      (value "SFM-120-X1-XXX-D")
      (footprint "eagle-import:SFM-120-X1-XXX-D")
      (libsource (lib "eagle-import") (part "SFM-120-X1-XXX-D"))
    )
    (comp (ref "CF4.1")
      (value "SFM-110-X1-XXX-D-LC")
      (footprint "eagle-import:SFM-110-X1-XXX-D-LC")
      (libsource (lib "eagle-import") (part "SFM-110-X1-XXX-D-LC"))
    )
    (comp (ref "CF4.2")
      (value "SFM-120-X1-XXX-D")
      (footprint "eagle-import:SFM-120-X1-XXX-D")
      (libsource (lib "eagle-import") (part "SFM-120-X1-XXX-D"))
    )
    (comp (ref "CF7.1")
      (value "SFM-110-X1-XXX-D-LC")
      (footprint "eagle-import:SFM-110-X1-XXX-D-LC")
      (libsource (lib "eagle-import") (part "SFM-110-X1-XXX-D-LC"))
    )
    (comp (ref "CF7.2")
      (value "SFM-120-X1-XXX-D")
      (footprint "eagle-import:SFM-120-X1-XXX-D")
      (libsource (lib "eagle-import") (part "SFM-120-X1-XXX-D"))
    )
  )
  (nets
    (net (code "1") (name "AUX-1") (class "Default")
      (node (ref "CF12.1") (pin "1") (pinfunction "1_1") (pintype "passive"))
      (node (ref "CF12.1") (pin "2") (pinfunction "2_2") (pintype "passive"))
      (node (ref "CF13.1") (pin "1") (pinfunction "1_1") (pintype "passive"))
      (node (ref "CF13.1") (pin "2") (pinfunction "2_2") (pintype "passive"))
      (node (ref "CF14.1") (pin "1") (pinfunction "1_1") (pintype "passive"))
      (node (ref "CF14.1") (pin "2") (pinfunction "2_2") (pintype "passive"))
      (node (ref "CF15.1") (pin "1") (pinfunction "1_1") (pintype "passive"))
      (node (ref "CF15.1") (pin "2") (pinfunction "2_2") (pintype "passive"))
      (node (ref "CF16.1") (pin "1") (pinfunction "1_1") (pintype "passive"))
      (node (ref "CF16.1") (pin "2") (pinfunction "2_2") (pintype "passive"))
      (node (ref "CF17.1") (pin "1") (pinfunction "1_1") (pintype "passive"))
      (node (ref "CF17.1") (pin "2") (pinfunction "2_2") (pintype "passive"))
      (node (ref "CF18.1") (pin "1") (pinfunction "1_1") (pintype "passive"))
      (node (ref "CF18.1") (pin "2") (pinfunction "2_2") (pintype "passive"))
      (node (ref "CF19.1") (pin "1") (pinfunction "1_1") (pintype "passive"))
      (node (ref "CF19.1") (pin "2") (pinfunction "2_2") (pintype "passive"))
      (node (ref "CF2.1") (pin "1") (pinfunction "1_1") (pintype "passive"))
      (node (ref "CF2.1") (pin "2") (pinfunction "2_2") (pintype "passive"))
      (node (ref "CF3.1") (pin "1") (pinfunction "1_1") (pintype "passive"))
      (node (ref "CF3.1") (pin "2") (pinfunction "2_2") (pintype "passive"))
      (node (ref "CF4.1") (pin "1") (pinfunction "1_1") (pintype "passive"))
      (node (ref "CF4.1") (pin "2") (pinfunction "2_2") (pintype "passive"))
      (node (ref "CF5.1") (pin "1") (pinfunction "1_1") (pintype "passive"))
      (node (ref "CF5.1") (pin "2") (pinfunction "2_2") (pintype "passive"))
      (node (ref "CF6.1") (pin "1") (pinfunction "1_1") (pintype "passive"))
      (node (ref "CF6.1") (pin "2") (pinfunction "2_2") (pintype "passive"))
      (node (ref "CF7.1") (pin "1") (pinfunction "1_1") (pintype "passive"))
      (node (ref "CF7.1") (pin "2") (pinfunction "2_2") (pintype "passive"))
      (node (ref "CF8.1") (pin "1") (pinfunction "1_1") (pintype "passive"))
      (node (ref "CF8.1") (pin "2") (pinfunction "2_2") (pintype "passive"))
    )
    (net (code "2") (name "AUX-2") (class "Default")
      (node (ref "CF12.1") (pin "3") (pinfunction "3_3") (pintype "passive"))
      (node (ref "CF12.1") (pin "4") (pinfunction "4_4") (pintype "passive"))
      (node (ref "CF13.1") (pin "3") (pinfunction "3_3") (pintype "passive"))
      (node (ref "CF13.1") (pin "4") (pinfunction "4_4") (pintype "passive"))
      (node (ref "CF14.1") (pin "3") (pinfunction "3_3") (pintype "passive"))
      (node (ref "CF14.1") (pin "4") (pinfunction "4_4") (pintype "passive"))
      (node (ref "CF15.1") (pin "3") (pinfunction "3_3") (pintype "passive"))
      (node (ref "CF15.1") (pin "4") (pinfunction "4_4") (pintype "passive"))
      (node (ref "CF16.1") (pin "3") (pinfunction "3_3") (pintype "passive"))
      (node (ref "CF16.1") (pin "4") (pinfunction "4_4") (pintype "passive"))
      (node (ref "CF17.1") (pin "3") (pinfunction "3_3") (pintype "passive"))
      (node (ref "CF17.1") (pin "4") (pinfunction "4_4") (pintype "passive"))
      (node (ref "CF18.1") (pin "3") (pinfunction "3_3") (pintype "passive"))
      (node (ref "CF18.1") (pin "4") (pinfunction "4_4") (pintype "passive"))
      (node (ref "CF19.1") (pin "3") (pinfunction "3_3") (pintype "passive"))
      (node (ref "CF19.1") (pin "4") (pinfunction "4_4") (pintype "passive"))
      (node (ref "CF2.1") (pin "3") (pinfunction "3_3") (pintype "passive"))
      (node (ref "CF2.1") (pin "4") (pinfunction "4_4") (pintype "passive"))
      (node (ref "CF3.1") (pin "3") (pinfunction "3_3") (pintype "passive"))
      (node (ref "CF3.1") (pin "4") (pinfunction "4_4") (pintype "passive"))
      (node (ref "CF4.1") (pin "3") (pinfunction "3_3") (pintype "passive"))
      (node (ref "CF4.1") (pin "4") (pinfunction "4_4") (pintype "passive"))
      (node (ref "CF5.1") (pin "3") (pinfunction "3_3") (pintype "passive"))
      (node (ref "CF5.1") (pin "4") (pinfunction "4_4") (pintype "passive"))
      (node (ref "CF6.1") (pin "3") (pinfunction "3_3") (pintype "passive"))
      (node (ref "CF6.1") (pin "4") (pinfunction "4_4") (pintype "passive"))
      (node (ref "CF7.1") (pin "3") (pinfunction "3_3") (pintype "passive"))
      (node (ref "CF7.1") (pin "4") (pinfunction "4_4") (pintype "passive"))
      (node (ref "CF8.1") (pin "3") (pinfunction "3_3") (pintype "passive"))
      (node (ref "CF8.1") (pin "4") (pinfunction "4_4") (pintype "passive"))
    )
    (net (code "3") (name "AUX-3") (class "Default")
      (node (ref "CF12.1") (pin "5") (pinfunction "5_5") (pintype "passive"))
      (node (ref "CF12.1") (pin "6") (pinfunction "6_6") (pintype "passive"))
      (node (ref "CF13.1") (pin "5") (pinfunction "5_5") (pintype "passive"))
      (node (ref "CF13.1") (pin "6") (pinfunction "6_6") (pintype "passive"))
      (node (ref "CF14.1") (pin "5") (pinfunction "5_5") (pintype "passive"))
      (node (ref "CF14.1") (pin "6") (pinfunction "6_6") (pintype "passive"))
      (node (ref "CF15.1") (pin "5") (pinfunction "5_5") (pintype "passive"))
      (node (ref "CF15.1") (pin "6") (pinfunction "6_6") (pintype "passive"))
      (node (ref "CF16.1") (pin "5") (pinfunction "5_5") (pintype "passive"))
      (node (ref "CF16.1") (pin "6") (pinfunction "6_6") (pintype "passive"))
      (node (ref "CF17.1") (pin "5") (pinfunction "5_5") (pintype "passive"))
      (node (ref "CF17.1") (pin "6") (pinfunction "6_6") (pintype "passive"))
      (node (ref "CF18.1") (pin "5") (pinfunction "5_5") (pintype "passive"))
      (node (ref "CF18.1") (pin "6") (pinfunction "6_6") (pintype "passive"))
      (node (ref "CF19.1") (pin "5") (pinfunction "5_5") (pintype "passive"))
      (node (ref "CF19.1") (pin "6") (pinfunction "6_6") (pintype "passive"))
      (node (ref "CF2.1") (pin "5") (pinfunction "5_5") (pintype "passive"))
      (node (ref "CF2.1") (pin "6") (pinfunction "6_6") (pintype "passive"))
      (node (ref "CF3.1") (pin "5") (pinfunction "5_5") (pintype "passive"))
      (node (ref "CF3.1") (pin "6") (pinfunction "6_6") (pintype "passive"))
      (node (ref "CF4.1") (pin "5") (pinfunction "5_5") (pintype "passive"))
      (node (ref "CF4.1") (pin "6") (pinfunction "6_6") (pintype "passive"))
      (node (ref "CF5.1") (pin "5") (pinfunction "5_5") (pintype "passive"))
      (node (ref "CF5.1") (pin "6") (pinfunction "6_6") (pintype "passive"))
      (node (ref "CF6.1") (pin "5") (pinfunction "5_5") (pintype "passive"))
      (node (ref "CF6.1") (pin "6") (pinfunction "6_6") (pintype "passive"))
      (node (ref "CF7.1") (pin "5") (pinfunction "5_5") (pintype "passive"))
      (node (ref "CF7.1") (pin "6") (pinfunction "6_6") (pintype "passive"))
      (node (ref "CF8.1") (pin "5") (pinfunction "5_5") (pintype "passive"))
      (node (ref "CF8.1") (pin "6") (pinfunction "6_6") (pintype "passive"))
    )
    (net (code "4") (name "AUX-4") (class "Default")
      (node (ref "CF12.1") (pin "7") (pinfunction "7_7") (pintype "passive"))
      (node (ref "CF12.1") (pin "8") (pinfunction "8_8") (pintype "passive"))
      (node (ref "CF13.1") (pin "7") (pinfunction "7_7") (pintype "passive"))
      (node (ref "CF13.1") (pin "8") (pinfunction "8_8") (pintype "passive"))
      (node (ref "CF14.1") (pin "7") (pinfunction "7_7") (pintype "passive"))
      (node (ref "CF14.1") (pin "8") (pinfunction "8_8") (pintype "passive"))
      (node (ref "CF15.1") (pin "7") (pinfunction "7_7") (pintype "passive"))
      (node (ref "CF15.1") (pin "8") (pinfunction "8_8") (pintype "passive"))
      (node (ref "CF16.1") (pin "7") (pinfunction "7_7") (pintype "passive"))
      (node (ref "CF16.1") (pin "8") (pinfunction "8_8") (pintype "passive"))
      (node (ref "CF17.1") (pin "7") (pinfunction "7_7") (pintype "passive"))
      (node (ref "CF17.1") (pin "8") (pinfunction "8_8") (pintype "passive"))
      (node (ref "CF18.1") (pin "7") (pinfunction "7_7") (pintype "passive"))
      (node (ref "CF18.1") (pin "8") (pinfunction "8_8") (pintype "passive"))
      (node (ref "CF19.1") (pin "7") (pinfunction "7_7") (pintype "passive"))
      (node (ref "CF19.1") (pin "8") (pinfunction "8_8") (pintype "passive"))
      (node (ref "CF2.1") (pin "7") (pinfunction "7_7") (pintype "passive"))
      (node (ref "CF2.1") (pin "8") (pinfunction "8_8") (pintype "passive"))
      (node (ref "CF3.1") (pin "7") (pinfunction "7_7") (pintype "passive"))
      (node (ref "CF3.1") (pin "8") (pinfunction "8_8") (pintype "passive"))
      (node (ref "CF4.1") (pin "7") (pinfunction "7_7") (pintype "passive"))
      (node (ref "CF4.1") (pin "8") (pinfunction "8_8") (pintype "passive"))
      (node (ref "CF5.1") (pin "7") (pinfunction "7_7") (pintype "passive"))
      (node (ref "CF5.1") (pin "8") (pinfunction "8_8") (pintype "passive"))
      (node (ref "CF6.1") (pin "7") (pinfunction "7_7") (pintype "passive"))
      (node (ref "CF6.1") (pin "8") (pinfunction "8_8") (pintype "passive"))
      (node (ref "CF7.1") (pin "7") (pinfunction "7_7") (pintype "passive"))
      (node (ref "CF7.1") (pin "8") (pinfunction "8_8") (pintype "passive"))
      (node (ref "CF8.1") (pin "7") (pinfunction "7_7") (pintype "passive"))
      (node (ref "CF8.1") (pin "8") (pinfunction "8_8") (pintype "passive"))
    )
    (net (code "5") (name "AUX-5") (class "Default")
      (node (ref "CF12.1") (pin "10") (pinfunction "10_10") (pintype "passive"))
      (node (ref "CF12.1") (pin "9") (pinfunction "9_9") (pintype "passive"))
      (node (ref "CF13.1") (pin "10") (pinfunction "10_10") (pintype "passive"))
      (node (ref "CF13.1") (pin "9") (pinfunction "9_9") (pintype "passive"))
      (node (ref "CF14.1") (pin "10") (pinfunction "10_10") (pintype "passive"))
      (node (ref "CF14.1") (pin "9") (pinfunction "9_9") (pintype "passive"))
      (node (ref "CF15.1") (pin "10") (pinfunction "10_10") (pintype "passive"))
      (node (ref "CF15.1") (pin "9") (pinfunction "9_9") (pintype "passive"))
      (node (ref "CF16.1") (pin "10") (pinfunction "10_10") (pintype "passive"))
      (node (ref "CF16.1") (pin "9") (pinfunction "9_9") (pintype "passive"))
      (node (ref "CF17.1") (pin "10") (pinfunction "10_10") (pintype "passive"))
      (node (ref "CF17.1") (pin "9") (pinfunction "9_9") (pintype "passive"))
      (node (ref "CF18.1") (pin "10") (pinfunction "10_10") (pintype "passive"))
      (node (ref "CF18.1") (pin "9") (pinfunction "9_9") (pintype "passive"))
      (node (ref "CF19.1") (pin "10") (pinfunction "10_10") (pintype "passive"))
      (node (ref "CF19.1") (pin "9") (pinfunction "9_9") (pintype "passive"))
      (node (ref "CF2.1") (pin "10") (pinfunction "10_10") (pintype "passive"))
      (node (ref "CF2.1") (pin "9") (pinfunction "9_9") (pintype "passive"))
      (node (ref "CF3.1") (pin "10") (pinfunction "10_10") (pintype "passive"))
      (node (ref "CF3.1") (pin "9") (pinfunction "9_9") (pintype "passive"))
      (node (ref "CF4.1") (pin "10") (pinfunction "10_10") (pintype "passive"))
      (node (ref "CF4.1") (pin "9") (pinfunction "9_9") (pintype "passive"))
      (node (ref "CF5.1") (pin "10") (pinfunction "10_10") (pintype "passive"))
      (node (ref "CF5.1") (pin "9") (pinfunction "9_9") (pintype "passive"))
      (node (ref "CF6.1") (pin "10") (pinfunction "10_10") (pintype "passive"))
      (node (ref "CF6.1") (pin "9") (pinfunction "9_9") (pintype "passive"))
      (node (ref "CF7.1") (pin "10") (pinfunction "10_10") (pintype "passive"))
      (node (ref "CF7.1") (pin "9") (pinfunction "9_9") (pintype "passive"))
      (node (ref "CF8.1") (pin "10") (pinfunction "10_10") (pintype "passive"))
      (node (ref "CF8.1") (pin "9") (pinfunction "9_9") (pintype "passive"))
    )
    (net (code "6") (name "AUX-6") (class "Default")
      (node (ref "CF12.1") (pin "11") (pinfunction "11_11") (pintype "passive"))
      (node (ref "CF12.1") (pin "12") (pinfunction "12_12") (pintype "passive"))
      (node (ref "CF13.1") (pin "11") (pinfunction "11_11") (pintype "passive"))
      (node (ref "CF13.1") (pin "12") (pinfunction "12_12") (pintype "passive"))
      (node (ref "CF14.1") (pin "11") (pinfunction "11_11") (pintype "passive"))
      (node (ref "CF14.1") (pin "12") (pinfunction "12_12") (pintype "passive"))
      (node (ref "CF15.1") (pin "11") (pinfunction "11_11") (pintype "passive"))
      (node (ref "CF15.1") (pin "12") (pinfunction "12_12") (pintype "passive"))
      (node (ref "CF16.1") (pin "11") (pinfunction "11_11") (pintype "passive"))
      (node (ref "CF16.1") (pin "12") (pinfunction "12_12") (pintype "passive"))
      (node (ref "CF17.1") (pin "11") (pinfunction "11_11") (pintype "passive"))
      (node (ref "CF17.1") (pin "12") (pinfunction "12_12") (pintype "passive"))
      (node (ref "CF18.1") (pin "11") (pinfunction "11_11") (pintype "passive"))
      (node (ref "CF18.1") (pin "12") (pinfunction "12_12") (pintype "passive"))
      (node (ref "CF19.1") (pin "11") (pinfunction "11_11") (pintype "passive"))
      (node (ref "CF19.1") (pin "12") (pinfunction "12_12") (pintype "passive"))
      (node (ref "CF2.1") (pin "11") (pinfunction "11_11") (pintype "passive"))
      (node (ref "CF2.1") (pin "12") (pinfunction "12_12") (pintype "passive"))
      (node (ref "CF3.1") (pin "11") (pinfunction "11_11") (pintype "passive"))
      (node (ref "CF3.1") (pin "12") (pinfunction "12_12") (pintype "passive"))
      (node (ref "CF4.1") (pin "11") (pinfunction "11_11") (pintype "passive"))
      (node (ref "CF4.1") (pin "12") (pinfunction "12_12") (pintype "passive"))
      (node (ref "CF5.1") (pin "11") (pinfunction "11_11") (pintype "passive"))
      (node (ref "CF5.1") (pin "12") (pinfunction "12_12") (pintype "passive"))
      (node (ref "CF6.1") (pin "11") (pinfunction "11_11") (pintype "passive"))
      (node (ref "CF6.1") (pin "12") (pinfunction "12_12") (pintype "passive"))
      (node (ref "CF7.1") (pin "11") (pinfunction "11_11") (pintype "passive"))
      (node (ref "CF7.1") (pin "12") (pinfunction "12_12") (pintype "passive"))
      (node (ref "CF8.1") (pin "11") (pinfunction "11_11") (pintype "passive"))
      (node (ref "CF8.1") (pin "12") (pinfunction "12_12") (pintype "passive"))
    )
    (net (code "7") (name "AUX-7") (class "Default")
      (node (ref "CF12.1") (pin "13") (pinfunction "13_13") (pintype "passive"))
      (node (ref "CF12.1") (pin "14") (pinfunction "14_14") (pintype "passive"))
      (node (ref "CF13.1") (pin "13") (pinfunction "13_13") (pintype "passive"))
      (node (ref "CF13.1") (pin "14") (pinfunction "14_14") (pintype "passive"))
      (node (ref "CF14.1") (pin "13") (pinfunction "13_13") (pintype "passive"))
      (node (ref "CF14.1") (pin "14") (pinfunction "14_14") (pintype "passive"))
      (node (ref "CF15.1") (pin "13") (pinfunction "13_13") (pintype "passive"))
      (node (ref "CF15.1") (pin "14") (pinfunction "14_14") (pintype "passive"))
      (node (ref "CF16.1") (pin "13") (pinfunction "13_13") (pintype "passive"))
      (node (ref "CF16.1") (pin "14") (pinfunction "14_14") (pintype "passive"))
      (node (ref "CF17.1") (pin "13") (pinfunction "13_13") (pintype "passive"))
      (node (ref "CF17.1") (pin "14") (pinfunction "14_14") (pintype "passive"))
      (node (ref "CF18.1") (pin "13") (pinfunction "13_13") (pintype "passive"))
      (node (ref "CF18.1") (pin "14") (pinfunction "14_14") (pintype "passive"))
      (node (ref "CF19.1") (pin "13") (pinfunction "13_13") (pintype "passive"))
      (node (ref "CF19.1") (pin "14") (pinfunction "14_14") (pintype "passive"))
      (node (ref "CF2.1") (pin "13") (pinfunction "13_13") (pintype "passive"))
      (node (ref "CF2.1") (pin "14") (pinfunction "14_14") (pintype "passive"))
      (node (ref "CF3.1") (pin "13") (pinfunction "13_13") (pintype "passive"))
      (node (ref "CF3.1") (pin "14") (pinfunction "14_14") (pintype "passive"))
      (node (ref "CF4.1") (pin "13") (pinfunction "13_13") (pintype "passive"))
      (node (ref "CF4.1") (pin "14") (pinfunction "14_14") (pintype "passive"))
      (node (ref "CF5.1") (pin "13") (pinfunction "13_13") (pintype "passive"))
      (node (ref "CF5.1") (pin "14") (pinfunction "14_14") (pintype "passive"))
      (node (ref "CF6.1") (pin "13") (pinfunction "13_13") (pintype "passive"))
      (node (ref "CF6.1") (pin "14") (pinfunction "14_14") (pintype "passive"))
      (node (ref "CF7.1") (pin "13") (pinfunction "13_13") (pintype "passive"))
      (node (ref "CF7.1") (pin "14") (pinfunction "14_14") (pintype "passive"))
      (node (ref "CF8.1") (pin "13") (pinfunction "13_13") (pintype "passive"))
      (node (ref "CF8.1") (pin "14") (pinfunction "14_14") (pintype "passive"))
    )
    (net (code "8") (name "AUX-8") (class "Default")
      (node (ref "CF12.1") (pin "15") (pinfunction "15_15") (pintype "passive"))
      (node (ref "CF12.1") (pin "16") (pinfunction "16_16") (pintype "passive"))
      (node (ref "CF13.1") (pin "15") (pinfunction "15_15") (pintype "passive"))
      (node (ref "CF13.1") (pin "16") (pinfunction "16_16") (pintype "passive"))
      (node (ref "CF14.1") (pin "15") (pinfunction "15_15") (pintype "passive"))
      (node (ref "CF14.1") (pin "16") (pinfunction "16_16") (pintype "passive"))
      (node (ref "CF15.1") (pin "15") (pinfunction "15_15") (pintype "passive"))
      (node (ref "CF15.1") (pin "16") (pinfunction "16_16") (pintype "passive"))
      (node (ref "CF16.1") (pin "15") (pinfunction "15_15") (pintype "passive"))
      (node (ref "CF16.1") (pin "16") (pinfunction "16_16") (pintype "passive"))
      (node (ref "CF17.1") (pin "15") (pinfunction "15_15") (pintype "passive"))
      (node (ref "CF17.1") (pin "16") (pinfunction "16_16") (pintype "passive"))
      (node (ref "CF18.1") (pin "15") (pinfunction "15_15") (pintype "passive"))
      (node (ref "CF18.1") (pin "16") (pinfunction "16_16") (pintype "passive"))
      (node (ref "CF19.1") (pin "15") (pinfunction "15_15") (pintype "passive"))
      (node (ref "CF19.1") (pin "16") (pinfunction "16_16") (pintype "passive"))
      (node (ref "CF2.1") (pin "15") (pinfunction "15_15") (pintype "passive"))
      (node (ref "CF2.1") (pin "16") (pinfunction "16_16") (pintype "passive"))
      (node (ref "CF3.1") (pin "15") (pinfunction "15_15") (pintype "passive"))
      (node (ref "CF3.1") (pin "16") (pinfunction "16_16") (pintype "passive"))
      (node (ref "CF4.1") (pin "15") (pinfunction "15_15") (pintype "passive"))
      (node (ref "CF4.1") (pin "16") (pinfunction "16_16") (pintype "passive"))
      (node (ref "CF5.1") (pin "15") (pinfunction "15_15") (pintype "passive"))
      (node (ref "CF5.1") (pin "16") (pinfunction "16_16") (pintype "passive"))
      (node (ref "CF6.1") (pin "15") (pinfunction "15_15") (pintype "passive"))
      (node (ref "CF6.1") (pin "16") (pinfunction "16_16") (pintype "passive"))
      (node (ref "CF7.1") (pin "15") (pinfunction "15_15") (pintype "passive"))
      (node (ref "CF7.1") (pin "16") (pinfunction "16_16") (pintype "passive"))
      (node (ref "CF8.1") (pin "15") (pinfunction "15_15") (pintype "passive"))
      (node (ref "CF8.1") (pin "16") (pinfunction "16_16") (pintype "passive"))
    )
    (net (code "9") (name "AUX-9") (class "Default")
      (node (ref "CF12.1") (pin "17") (pinfunction "17_17") (pintype "passive"))
      (node (ref "CF12.1") (pin "18") (pinfunction "18_18") (pintype "passive"))
      (node (ref "CF13.1") (pin "17") (pinfunction "17_17") (pintype "passive"))
      (node (ref "CF13.1") (pin "18") (pinfunction "18_18") (pintype "passive"))
      (node (ref "CF14.1") (pin "17") (pinfunction "17_17") (pintype "passive"))
      (node (ref "CF14.1") (pin "18") (pinfunction "18_18") (pintype "passive"))
      (node (ref "CF15.1") (pin "17") (pinfunction "17_17") (pintype "passive"))
      (node (ref "CF15.1") (pin "18") (pinfunction "18_18") (pintype "passive"))
      (node (ref "CF16.1") (pin "17") (pinfunction "17_17") (pintype "passive"))
      (node (ref "CF16.1") (pin "18") (pinfunction "18_18") (pintype "passive"))
      (node (ref "CF17.1") (pin "17") (pinfunction "17_17") (pintype "passive"))
      (node (ref "CF17.1") (pin "18") (pinfunction "18_18") (pintype "passive"))
      (node (ref "CF18.1") (pin "17") (pinfunction "17_17") (pintype "passive"))
      (node (ref "CF18.1") (pin "18") (pinfunction "18_18") (pintype "passive"))
      (node (ref "CF19.1") (pin "17") (pinfunction "17_17") (pintype "passive"))
      (node (ref "CF19.1") (pin "18") (pinfunction "18_18") (pintype "passive"))
      (node (ref "CF2.1") (pin "17") (pinfunction "17_17") (pintype "passive"))
      (node (ref "CF2.1") (pin "18") (pinfunction "18_18") (pintype "passive"))
      (node (ref "CF3.1") (pin "17") (pinfunction "17_17") (pintype "passive"))
      (node (ref "CF3.1") (pin "18") (pinfunction "18_18") (pintype "passive"))
      (node (ref "CF4.1") (pin "17") (pinfunction "17_17") (pintype "passive"))
      (node (ref "CF4.1") (pin "18") (pinfunction "18_18") (pintype "passive"))
      (node (ref "CF5.1") (pin "17") (pinfunction "17_17") (pintype "passive"))
      (node (ref "CF5.1") (pin "18") (pinfunction "18_18") (pintype "passive"))
      (node (ref "CF6.1") (pin "17") (pinfunction "17_17") (pintype "passive"))
      (node (ref "CF6.1") (pin "18") (pinfunction "18_18") (pintype "passive"))
      (node (ref "CF7.1") (pin "17") (pinfunction "17_17") (pintype "passive"))
      (node (ref "CF7.1") (pin "18") (pinfunction "18_18") (pintype "passive"))
      (node (ref "CF8.1") (pin "17") (pinfunction "17_17") (pintype "passive"))
      (node (ref "CF8.1") (pin "18") (pinfunction "18_18") (pintype "passive"))
    )
    (net (code "10") (name "AUX-10") (class "Default")
      (node (ref "CF12.1") (pin "19") (pinfunction "19_19") (pintype "passive"))
      (node (ref "CF12.1") (pin "20") (pinfunction "20_20") (pintype "passive"))
      (node (ref "CF13.1") (pin "19") (pinfunction "19_19") (pintype "passive"))
      (node (ref "CF13.1") (pin "20") (pinfunction "20_20") (pintype "passive"))
      (node (ref "CF14.1") (pin "19") (pinfunction "19_19") (pintype "passive"))
      (node (ref "CF14.1") (pin "20") (pinfunction "20_20") (pintype "passive"))
      (node (ref "CF15.1") (pin "19") (pinfunction "19_19") (pintype "passive"))
      (node (ref "CF15.1") (pin "20") (pinfunction "20_20") (pintype "passive"))
      (node (ref "CF16.1") (pin "19") (pinfunction "19_19") (pintype "passive"))
      (node (ref "CF16.1") (pin "20") (pinfunction "20_20") (pintype "passive"))
      (node (ref "CF17.1") (pin "19") (pinfunction "19_19") (pintype "passive"))
      (node (ref "CF17.1") (pin "20") (pinfunction "20_20") (pintype "passive"))
      (node (ref "CF18.1") (pin "19") (pinfunction "19_19") (pintype "passive"))
      (node (ref "CF18.1") (pin "20") (pinfunction "20_20") (pintype "passive"))
      (node (ref "CF19.1") (pin "19") (pinfunction "19_19") (pintype "passive"))
      (node (ref "CF19.1") (pin "20") (pinfunction "20_20") (pintype "passive"))
      (node (ref "CF2.1") (pin "19") (pinfunction "19_19") (pintype "passive"))
      (node (ref "CF2.1") (pin "20") (pinfunction "20_20") (pintype "passive"))
      (node (ref "CF3.1") (pin "19") (pinfunction "19_19") (pintype "passive"))
      (node (ref "CF3.1") (pin "20") (pinfunction "20_20") (pintype "passive"))
      (node (ref "CF4.1") (pin "19") (pinfunction "19_19") (pintype "passive"))
      (node (ref "CF4.1") (pin "20") (pinfunction "20_20") (pintype "passive"))
      (node (ref "CF5.1") (pin "19") (pinfunction "19_19") (pintype "passive"))
      (node (ref "CF5.1") (pin "20") (pinfunction "20_20") (pintype "passive"))
      (node (ref "CF6.1") (pin "19") (pinfunction "19_19") (pintype "passive"))
      (node (ref "CF6.1") (pin "20") (pinfunction "20_20") (pintype "passive"))
      (node (ref "CF7.1") (pin "19") (pinfunction "19_19") (pintype "passive"))
      (node (ref "CF7.1") (pin "20") (pinfunction "20_20") (pintype "passive"))
      (node (ref "CF8.1") (pin "19") (pinfunction "19_19") (pintype "passive"))
      (node (ref "CF8.1") (pin "20") (pinfunction "20_20") (pintype "passive"))
    )
    (net (code "11") (name "CAN1_H") (class "Default")
      (node (ref "CF12.2") (pin "33") (pinfunction "33_33") (pintype "passive"))
      (node (ref "CF12.2") (pin "34") (pinfunction "34_34") (pintype "passive"))
      (node (ref "CF13.2") (pin "33") (pinfunction "33_33") (pintype "passive"))
      (node (ref "CF13.2") (pin "34") (pinfunction "34_34") (pintype "passive"))
      (node (ref "CF14.2") (pin "33") (pinfunction "33_33") (pintype "passive"))
      (node (ref "CF14.2") (pin "34") (pinfunction "34_34") (pintype "passive"))
      (node (ref "CF15.2") (pin "33") (pinfunction "33_33") (pintype "passive"))
      (node (ref "CF15.2") (pin "34") (pinfunction "34_34") (pintype "passive"))
      (node (ref "CF16.2") (pin "33") (pinfunction "33_33") (pintype "passive"))
      (node (ref "CF16.2") (pin "34") (pinfunction "34_34") (pintype "passive"))
      (node (ref "CF17.2") (pin "33") (pinfunction "33_33") (pintype "passive"))
      (node (ref "CF17.2") (pin "34") (pinfunction "34_34") (pintype "passive"))
      (node (ref "CF18.2") (pin "33") (pinfunction "33_33") (pintype "passive"))
      (node (ref "CF18.2") (pin "34") (pinfunction "34_34") (pintype "passive"))
      (node (ref "CF19.2") (pin "33") (pinfunction "33_33") (pintype "passive"))
      (node (ref "CF19.2") (pin "34") (pinfunction "34_34") (pintype "passive"))
      (node (ref "CF2.2") (pin "33") (pinfunction "33_33") (pintype "passive"))
      (node (ref "CF2.2") (pin "34") (pinfunction "34_34") (pintype "passive"))
      (node (ref "CF2.3") (pin "33") (pinfunction "33_33") (pintype "passive"))
      (node (ref "CF2.3") (pin "34") (pinfunction "34_34") (pintype "passive"))
      (node (ref "CF2.4") (pin "33") (pinfunction "33_33") (pintype "passive"))
      (node (ref "CF2.4") (pin "34") (pinfunction "34_34") (pintype "passive"))
      (node (ref "CF3.2") (pin "33") (pinfunction "33_33") (pintype "passive"))
      (node (ref "CF3.2") (pin "34") (pinfunction "34_34") (pintype "passive"))
      (node (ref "CF4.2") (pin "33") (pinfunction "33_33") (pintype "passive"))
      (node (ref "CF4.2") (pin "34") (pinfunction "34_34") (pintype "passive"))
      (node (ref "CF5.2") (pin "33") (pinfunction "33_33") (pintype "passive"))
      (node (ref "CF5.2") (pin "34") (pinfunction "34_34") (pintype "passive"))
      (node (ref "CF6.2") (pin "33") (pinfunction "33_33") (pintype "passive"))
      (node (ref "CF6.2") (pin "34") (pinfunction "34_34") (pintype "passive"))
      (node (ref "CF7.2") (pin "33") (pinfunction "33_33") (pintype "passive"))
      (node (ref "CF7.2") (pin "34") (pinfunction "34_34") (pintype "passive"))
      (node (ref "CF8.2") (pin "33") (pinfunction "33_33") (pintype "passive"))
      (node (ref "CF8.2") (pin "34") (pinfunction "34_34") (pintype "passive"))
      (node (ref "R1") (pin "1") (pinfunction "1_1") (pintype "passive"))
      (node (ref "R5") (pin "1") (pinfunction "1_1") (pintype "passive"))
    )
    (net (code "12") (name "CAN1_L") (class "Default")
      (node (ref "CF12.2") (pin "35") (pinfunction "35_35") (pintype "passive"))
      (node (ref "CF12.2") (pin "36") (pinfunction "36_36") (pintype "passive"))
      (node (ref "CF13.2") (pin "35") (pinfunction "35_35") (pintype "passive"))
      (node (ref "CF13.2") (pin "36") (pinfunction "36_36") (pintype "passive"))
      (node (ref "CF14.2") (pin "35") (pinfunction "35_35") (pintype "passive"))
      (node (ref "CF14.2") (pin "36") (pinfunction "36_36") (pintype "passive"))
      (node (ref "CF15.2") (pin "35") (pinfunction "35_35") (pintype "passive"))
      (node (ref "CF15.2") (pin "36") (pinfunction "36_36") (pintype "passive"))
      (node (ref "CF16.2") (pin "35") (pinfunction "35_35") (pintype "passive"))
      (node (ref "CF16.2") (pin "36") (pinfunction "36_36") (pintype "passive"))
      (node (ref "CF17.2") (pin "35") (pinfunction "35_35") (pintype "passive"))
      (node (ref "CF17.2") (pin "36") (pinfunction "36_36") (pintype "passive"))
      (node (ref "CF18.2") (pin "35") (pinfunction "35_35") (pintype "passive"))
      (node (ref "CF18.2") (pin "36") (pinfunction "36_36") (pintype "passive"))
      (node (ref "CF19.2") (pin "35") (pinfunction "35_35") (pintype "passive"))
      (node (ref "CF19.2") (pin "36") (pinfunction "36_36") (pintype "passive"))
      (node (ref "CF2.2") (pin "35") (pinfunction "35_35") (pintype "passive"))
      (node (ref "CF2.2") (pin "36") (pinfunction "36_36") (pintype "passive"))
      (node (ref "CF2.3") (pin "35") (pinfunction "35_35") (pintype "passive"))
      (node (ref "CF2.3") (pin "36") (pinfunction "36_36") (pintype "passive"))
      (node (ref "CF2.4") (pin "35") (pinfunction "35_35") (pintype "passive"))
      (node (ref "CF2.4") (pin "36") (pinfunction "36_36") (pintype "passive"))
      (node (ref "CF3.2") (pin "35") (pinfunction "35_35") (pintype "passive"))
      (node (ref "CF3.2") (pin "36") (pinfunction "36_36") (pintype "passive"))
      (node (ref "CF4.2") (pin "35") (pinfunction "35_35") (pintype "passive"))
      (node (ref "CF4.2") (pin "36") (pinfunction "36_36") (pintype "passive"))
      (node (ref "CF5.2") (pin "35") (pinfunction "35_35") (pintype "passive"))
      (node (ref "CF5.2") (pin "36") (pinfunction "36_36") (pintype "passive"))
      (node (ref "CF6.2") (pin "35") (pinfunction "35_35") (pintype "passive"))
      (node (ref "CF6.2") (pin "36") (pinfunction "36_36") (pintype "passive"))
      (node (ref "CF7.2") (pin "35") (pinfunction "35_35") (pintype "passive"))
      (node (ref "CF7.2") (pin "36") (pinfunction "36_36") (pintype "passive"))
      (node (ref "CF8.2") (pin "35") (pinfunction "35_35") (pintype "passive"))
      (node (ref "CF8.2") (pin "36") (pinfunction "36_36") (pintype "passive"))
      (node (ref "R2") (pin "1") (pinfunction "1_1") (pintype "passive"))
      (node (ref "R6") (pin "1") (pinfunction "1_1") (pintype "passive"))
    )
    (net (code "13") (name "CAN2_H") (class "Default")
      (node (ref "CF12.2") (pin "17") (pinfunction "17_17") (pintype "passive"))
      (node (ref "CF12.2") (pin "18") (pinfunction "18_18") (pintype "passive"))
      (node (ref "CF13.2") (pin "17") (pinfunction "17_17") (pintype "passive"))
      (node (ref "CF13.2") (pin "18") (pinfunction "18_18") (pintype "passive"))
      (node (ref "CF14.2") (pin "17") (pinfunction "17_17") (pintype "passive"))
      (node (ref "CF14.2") (pin "18") (pinfunction "18_18") (pintype "passive"))
      (node (ref "CF15.2") (pin "17") (pinfunction "17_17") (pintype "passive"))
      (node (ref "CF15.2") (pin "18") (pinfunction "18_18") (pintype "passive"))
      (node (ref "CF16.2") (pin "17") (pinfunction "17_17") (pintype "passive"))
      (node (ref "CF16.2") (pin "18") (pinfunction "18_18") (pintype "passive"))
      (node (ref "CF17.2") (pin "17") (pinfunction "17_17") (pintype "passive"))
      (node (ref "CF17.2") (pin "18") (pinfunction "18_18") (pintype "passive"))
      (node (ref "CF18.2") (pin "17") (pinfunction "17_17") (pintype "passive"))
      (node (ref "CF18.2") (pin "18") (pinfunction "18_18") (pintype "passive"))
      (node (ref "CF19.2") (pin "17") (pinfunction "17_17") (pintype "passive"))
      (node (ref "CF19.2") (pin "18") (pinfunction "18_18") (pintype "passive"))
      (node (ref "CF2.2") (pin "17") (pinfunction "17_17") (pintype "passive"))
      (node (ref "CF2.2") (pin "18") (pinfunction "18_18") (pintype "passive"))
      (node (ref "CF2.3") (pin "17") (pinfunction "17_17") (pintype "passive"))
      (node (ref "CF2.3") (pin "18") (pinfunction "18_18") (pintype "passive"))
      (node (ref "CF2.4") (pin "17") (pinfunction "17_17") (pintype "passive"))
      (node (ref "CF2.4") (pin "18") (pinfunction "18_18") (pintype "passive"))
      (node (ref "CF3.2") (pin "17") (pinfunction "17_17") (pintype "passive"))
      (node (ref "CF3.2") (pin "18") (pinfunction "18_18") (pintype "passive"))
      (node (ref "CF4.2") (pin "17") (pinfunction "17_17") (pintype "passive"))
      (node (ref "CF4.2") (pin "18") (pinfunction "18_18") (pintype "passive"))
      (node (ref "CF5.2") (pin "17") (pinfunction "17_17") (pintype "passive"))
      (node (ref "CF5.2") (pin "18") (pinfunction "18_18") (pintype "passive"))
      (node (ref "CF6.2") (pin "17") (pinfunction "17_17") (pintype "passive"))
      (node (ref "CF6.2") (pin "18") (pinfunction "18_18") (pintype "passive"))
      (node (ref "CF7.2") (pin "17") (pinfunction "17_17") (pintype "passive"))
      (node (ref "CF7.2") (pin "18") (pinfunction "18_18") (pintype "passive"))
      (node (ref "CF8.2") (pin "17") (pinfunction "17_17") (pintype "passive"))
      (node (ref "CF8.2") (pin "18") (pinfunction "18_18") (pintype "passive"))
      (node (ref "R3") (pin "1") (pinfunction "1_1") (pintype "passive"))
      (node (ref "R7") (pin "1") (pinfunction "1_1") (pintype "passive"))
    )
    (net (code "14") (name "CAN2_L") (class "Default")
      (node (ref "CF12.2") (pin "19") (pinfunction "19_19") (pintype "passive"))
      (node (ref "CF12.2") (pin "20") (pinfunction "20_20") (pintype "passive"))
      (node (ref "CF13.2") (pin "19") (pinfunction "19_19") (pintype "passive"))
      (node (ref "CF13.2") (pin "20") (pinfunction "20_20") (pintype "passive"))
      (node (ref "CF14.2") (pin "19") (pinfunction "19_19") (pintype "passive"))
      (node (ref "CF14.2") (pin "20") (pinfunction "20_20") (pintype "passive"))
      (node (ref "CF15.2") (pin "19") (pinfunction "19_19") (pintype "passive"))
      (node (ref "CF15.2") (pin "20") (pinfunction "20_20") (pintype "passive"))
      (node (ref "CF16.2") (pin "19") (pinfunction "19_19") (pintype "passive"))
      (node (ref "CF16.2") (pin "20") (pinfunction "20_20") (pintype "passive"))
      (node (ref "CF17.2") (pin "19") (pinfunction "19_19") (pintype "passive"))
      (node (ref "CF17.2") (pin "20") (pinfunction "20_20") (pintype "passive"))
      (node (ref "CF18.2") (pin "19") (pinfunction "19_19") (pintype "passive"))
      (node (ref "CF18.2") (pin "20") (pinfunction "20_20") (pintype "passive"))
      (node (ref "CF19.2") (pin "19") (pinfunction "19_19") (pintype "passive"))
      (node (ref "CF19.2") (pin "20") (pinfunction "20_20") (pintype "passive"))
      (node (ref "CF2.2") (pin "19") (pinfunction "19_19") (pintype "passive"))
      (node (ref "CF2.2") (pin "20") (pinfunction "20_20") (pintype "passive"))
      (node (ref "CF2.3") (pin "19") (pinfunction "19_19") (pintype "passive"))
      (node (ref "CF2.3") (pin "20") (pinfunction "20_20") (pintype "passive"))
      (node (ref "CF2.4") (pin "19") (pinfunction "19_19") (pintype "passive"))
      (node (ref "CF2.4") (pin "20") (pinfunction "20_20") (pintype "passive"))
      (node (ref "CF3.2") (pin "19") (pinfunction "19_19") (pintype "passive"))
      (node (ref "CF3.2") (pin "20") (pinfunction "20_20") (pintype "passive"))
      (node (ref "CF4.2") (pin "19") (pinfunction "19_19") (pintype "passive"))
      (node (ref "CF4.2") (pin "20") (pinfunction "20_20") (pintype "passive"))
      (node (ref "CF5.2") (pin "19") (pinfunction "19_19") (pintype "passive"))
      (node (ref "CF5.2") (pin "20") (pinfunction "20_20") (pintype "passive"))
      (node (ref "CF6.2") (pin "19") (pinfunction "19_19") (pintype "passive"))
      (node (ref "CF6.2") (pin "20") (pinfunction "20_20") (pintype "passive"))
      (node (ref "CF7.2") (pin "19") (pinfunction "19_19") (pintype "passive"))
      (node (ref "CF7.2") (pin "20") (pinfunction "20_20") (pintype "passive"))
      (node (ref "CF8.2") (pin "19") (pinfunction "19_19") (pintype "passive"))
      (node (ref "CF8.2") (pin "20") (pinfunction "20_20") (pintype "passive"))
      (node (ref "R4") (pin "1") (pinfunction "1_1") (pintype "passive"))
      (node (ref "R8") (pin "1") (pinfunction "1_1") (pintype "passive"))
    )
    (net (code "15") (name "GND") (class "Default")
      (node (ref "C1") (pin "2") (pinfunction "2_2") (pintype "passive"))
      (node (ref "C2") (pin "2") (pinfunction "2_2") (pintype "passive"))
      (node (ref "C3") (pin "2") (pinfunction "2_2") (pintype "passive"))
      (node (ref "C4") (pin "2") (pinfunction "2_2") (pintype "passive"))
      (node (ref "CF12.1") (pin "LC1") (pinfunction "LC1_LC1") (pintype "passive"))
      (node (ref "CF12.1") (pin "LC2") (pinfunction "LC2_LC2") (pintype "passive"))
      (node (ref "CF12.2") (pin "27") (pinfunction "27_27") (pintype "passive"))
      (node (ref "CF12.2") (pin "28") (pinfunction "28_28") (pintype "passive"))
      (node (ref "CF12.2") (pin "29") (pinfunction "29_29") (pintype "passive"))
      (node (ref "CF12.2") (pin "30") (pinfunction "30_30") (pintype "passive"))
      (node (ref "CF12.2") (pin "31") (pinfunction "31_31") (pintype "passive"))
      (node (ref "CF12.2") (pin "32") (pinfunction "32_32") (pintype "passive"))
      (node (ref "CF12.2") (pin "37") (pinfunction "37_37") (pintype "passive"))
      (node (ref "CF12.2") (pin "38") (pinfunction "38_38") (pintype "passive"))
      (node (ref "CF12.2") (pin "LC1") (pinfunction "LC1_LC1") (pintype "passive"))
      (node (ref "CF12.2") (pin "LC2") (pinfunction "LC2_LC2") (pintype "passive"))
      (node (ref "CF13.1") (pin "LC1") (pinfunction "LC1_LC1") (pintype "passive"))
      (node (ref "CF13.1") (pin "LC2") (pinfunction "LC2_LC2") (pintype "passive"))
      (node (ref "CF13.2") (pin "27") (pinfunction "27_27") (pintype "passive"))
      (node (ref "CF13.2") (pin "28") (pinfunction "28_28") (pintype "passive"))
      (node (ref "CF13.2") (pin "29") (pinfunction "29_29") (pintype "passive"))
      (node (ref "CF13.2") (pin "30") (pinfunction "30_30") (pintype "passive"))
      (node (ref "CF13.2") (pin "31") (pinfunction "31_31") (pintype "passive"))
      (node (ref "CF13.2") (pin "32") (pinfunction "32_32") (pintype "passive"))
      (node (ref "CF13.2") (pin "37") (pinfunction "37_37") (pintype "passive"))
      (node (ref "CF13.2") (pin "38") (pinfunction "38_38") (pintype "passive"))
      (node (ref "CF13.2") (pin "LC1") (pinfunction "LC1_LC1") (pintype "passive"))
      (node (ref "CF13.2") (pin "LC2") (pinfunction "LC2_LC2") (pintype "passive"))
      (node (ref "CF14.1") (pin "LC1") (pinfunction "LC1_LC1") (pintype "passive"))
      (node (ref "CF14.1") (pin "LC2") (pinfunction "LC2_LC2") (pintype "passive"))
      (node (ref "CF14.2") (pin "27") (pinfunction "27_27") (pintype "passive"))
      (node (ref "CF14.2") (pin "28") (pinfunction "28_28") (pintype "passive"))
      (node (ref "CF14.2") (pin "29") (pinfunction "29_29") (pintype "passive"))
      (node (ref "CF14.2") (pin "30") (pinfunction "30_30") (pintype "passive"))
      (node (ref "CF14.2") (pin "31") (pinfunction "31_31") (pintype "passive"))
      (node (ref "CF14.2") (pin "32") (pinfunction "32_32") (pintype "passive"))
      (node (ref "CF14.2") (pin "37") (pinfunction "37_37") (pintype "passive"))
      (node (ref "CF14.2") (pin "38") (pinfunction "38_38") (pintype "passive"))
      (node (ref "CF14.2") (pin "LC1") (pinfunction "LC1_LC1") (pintype "passive"))
      (node (ref "CF14.2") (pin "LC2") (pinfunction "LC2_LC2") (pintype "passive"))
      (node (ref "CF15.1") (pin "LC1") (pinfunction "LC1_LC1") (pintype "passive"))
      (node (ref "CF15.1") (pin "LC2") (pinfunction "LC2_LC2") (pintype "passive"))
      (node (ref "CF15.2") (pin "27") (pinfunction "27_27") (pintype "passive"))
      (node (ref "CF15.2") (pin "28") (pinfunction "28_28") (pintype "passive"))
      (node (ref "CF15.2") (pin "29") (pinfunction "29_29") (pintype "passive"))
      (node (ref "CF15.2") (pin "30") (pinfunction "30_30") (pintype "passive"))
      (node (ref "CF15.2") (pin "31") (pinfunction "31_31") (pintype "passive"))
      (node (ref "CF15.2") (pin "32") (pinfunction "32_32") (pintype "passive"))
      (node (ref "CF15.2") (pin "37") (pinfunction "37_37") (pintype "passive"))
      (node (ref "CF15.2") (pin "38") (pinfunction "38_38") (pintype "passive"))
      (node (ref "CF15.2") (pin "LC1") (pinfunction "LC1_LC1") (pintype "passive"))
      (node (ref "CF15.2") (pin "LC2") (pinfunction "LC2_LC2") (pintype "passive"))
      (node (ref "CF16.1") (pin "LC1") (pinfunction "LC1_LC1") (pintype "passive"))
      (node (ref "CF16.1") (pin "LC2") (pinfunction "LC2_LC2") (pintype "passive"))
      (node (ref "CF16.2") (pin "27") (pinfunction "27_27") (pintype "passive"))
      (node (ref "CF16.2") (pin "28") (pinfunction "28_28") (pintype "passive"))
      (node (ref "CF16.2") (pin "29") (pinfunction "29_29") (pintype "passive"))
      (node (ref "CF16.2") (pin "30") (pinfunction "30_30") (pintype "passive"))
      (node (ref "CF16.2") (pin "31") (pinfunction "31_31") (pintype "passive"))
      (node (ref "CF16.2") (pin "32") (pinfunction "32_32") (pintype "passive"))
      (node (ref "CF16.2") (pin "37") (pinfunction "37_37") (pintype "passive"))
      (node (ref "CF16.2") (pin "38") (pinfunction "38_38") (pintype "passive"))
      (node (ref "CF16.2") (pin "LC1") (pinfunction "LC1_LC1") (pintype "passive"))
      (node (ref "CF16.2") (pin "LC2") (pinfunction "LC2_LC2") (pintype "passive"))
      (node (ref "CF17.1") (pin "LC1") (pinfunction "LC1_LC1") (pintype "passive"))
      (node (ref "CF17.1") (pin "LC2") (pinfunction "LC2_LC2") (pintype "passive"))
      (node (ref "CF17.2") (pin "27") (pinfunction "27_27") (pintype "passive"))
      (node (ref "CF17.2") (pin "28") (pinfunction "28_28") (pintype "passive"))
      (node (ref "CF17.2") (pin "29") (pinfunction "29_29") (pintype "passive"))
      (node (ref "CF17.2") (pin "30") (pinfunction "30_30") (pintype "passive"))
      (node (ref "CF17.2") (pin "31") (pinfunction "31_31") (pintype "passive"))
      (node (ref "CF17.2") (pin "32") (pinfunction "32_32") (pintype "passive"))
      (node (ref "CF17.2") (pin "37") (pinfunction "37_37") (pintype "passive"))
      (node (ref "CF17.2") (pin "38") (pinfunction "38_38") (pintype "passive"))
      (node (ref "CF17.2") (pin "LC1") (pinfunction "LC1_LC1") (pintype "passive"))
      (node (ref "CF17.2") (pin "LC2") (pinfunction "LC2_LC2") (pintype "passive"))
      (node (ref "CF18.1") (pin "LC1") (pinfunction "LC1_LC1") (pintype "passive"))
      (node (ref "CF18.1") (pin "LC2") (pinfunction "LC2_LC2") (pintype "passive"))
      (node (ref "CF18.2") (pin "27") (pinfunction "27_27") (pintype "passive"))
      (node (ref "CF18.2") (pin "28") (pinfunction "28_28") (pintype "passive"))
      (node (ref "CF18.2") (pin "29") (pinfunction "29_29") (pintype "passive"))
      (node (ref "CF18.2") (pin "30") (pinfunction "30_30") (pintype "passive"))
      (node (ref "CF18.2") (pin "31") (pinfunction "31_31") (pintype "passive"))
      (node (ref "CF18.2") (pin "32") (pinfunction "32_32") (pintype "passive"))
      (node (ref "CF18.2") (pin "37") (pinfunction "37_37") (pintype "passive"))
      (node (ref "CF18.2") (pin "38") (pinfunction "38_38") (pintype "passive"))
      (node (ref "CF18.2") (pin "LC1") (pinfunction "LC1_LC1") (pintype "passive"))
      (node (ref "CF18.2") (pin "LC2") (pinfunction "LC2_LC2") (pintype "passive"))
      (node (ref "CF19.1") (pin "LC1") (pinfunction "LC1_LC1") (pintype "passive"))
      (node (ref "CF19.1") (pin "LC2") (pinfunction "LC2_LC2") (pintype "passive"))
      (node (ref "CF19.2") (pin "27") (pinfunction "27_27") (pintype "passive"))
      (node (ref "CF19.2") (pin "28") (pinfunction "28_28") (pintype "passive"))
      (node (ref "CF19.2") (pin "29") (pinfunction "29_29") (pintype "passive"))
      (node (ref "CF19.2") (pin "30") (pinfunction "30_30") (pintype "passive"))
      (node (ref "CF19.2") (pin "31") (pinfunction "31_31") (pintype "passive"))
      (node (ref "CF19.2") (pin "32") (pinfunction "32_32") (pintype "passive"))
      (node (ref "CF19.2") (pin "37") (pinfunction "37_37") (pintype "passive"))
      (node (ref "CF19.2") (pin "38") (pinfunction "38_38") (pintype "passive"))
      (node (ref "CF19.2") (pin "LC1") (pinfunction "LC1_LC1") (pintype "passive"))
      (node (ref "CF19.2") (pin "LC2") (pinfunction "LC2_LC2") (pintype "passive"))
      (node (ref "CF2.1") (pin "LC1") (pinfunction "LC1_LC1") (pintype "passive"))
      (node (ref "CF2.1") (pin "LC2") (pinfunction "LC2_LC2") (pintype "passive"))
      (node (ref "CF2.2") (pin "27") (pinfunction "27_27") (pintype "passive"))
      (node (ref "CF2.2") (pin "28") (pinfunction "28_28") (pintype "passive"))
      (node (ref "CF2.2") (pin "29") (pinfunction "29_29") (pintype "passive"))
      (node (ref "CF2.2") (pin "30") (pinfunction "30_30") (pintype "passive"))
      (node (ref "CF2.2") (pin "31") (pinfunction "31_31") (pintype "passive"))
      (node (ref "CF2.2") (pin "32") (pinfunction "32_32") (pintype "passive"))
      (node (ref "CF2.2") (pin "37") (pinfunction "37_37") (pintype "passive"))
      (node (ref "CF2.2") (pin "38") (pinfunction "38_38") (pintype "passive"))
      (node (ref "CF2.2") (pin "LC1") (pinfunction "LC1_LC1") (pintype "passive"))
      (node (ref "CF2.2") (pin "LC2") (pinfunction "LC2_LC2") (pintype "passive"))
      (node (ref "CF2.3") (pin "27") (pinfunction "27_27") (pintype "passive"))
      (node (ref "CF2.3") (pin "28") (pinfunction "28_28") (pintype "passive"))
      (node (ref "CF2.3") (pin "29") (pinfunction "29_29") (pintype "passive"))
      (node (ref "CF2.3") (pin "30") (pinfunction "30_30") (pintype "passive"))
      (node (ref "CF2.3") (pin "31") (pinfunction "31_31") (pintype "passive"))
      (node (ref "CF2.3") (pin "32") (pinfunction "32_32") (pintype "passive"))
      (node (ref "CF2.3") (pin "37") (pinfunction "37_37") (pintype "passive"))
      (node (ref "CF2.3") (pin "38") (pinfunction "38_38") (pintype "passive"))
      (node (ref "CF2.3") (pin "LC1") (pinfunction "LC1_LC1") (pintype "passive"))
      (node (ref "CF2.3") (pin "LC2") (pinfunction "LC2_LC2") (pintype "passive"))
      (node (ref "CF2.4") (pin "27") (pinfunction "27_27") (pintype "passive"))
      (node (ref "CF2.4") (pin "28") (pinfunction "28_28") (pintype "passive"))
      (node (ref "CF2.4") (pin "29") (pinfunction "29_29") (pintype "passive"))
      (node (ref "CF2.4") (pin "30") (pinfunction "30_30") (pintype "passive"))
      (node (ref "CF2.4") (pin "31") (pinfunction "31_31") (pintype "passive"))
      (node (ref "CF2.4") (pin "32") (pinfunction "32_32") (pintype "passive"))
      (node (ref "CF2.4") (pin "37") (pinfunction "37_37") (pintype "passive"))
      (node (ref "CF2.4") (pin "38") (pinfunction "38_38") (pintype "passive"))
      (node (ref "CF2.4") (pin "LC1") (pinfunction "LC1_LC1") (pintype "passive"))
      (node (ref "CF2.4") (pin "LC2") (pinfunction "LC2_LC2") (pintype "passive"))
      (node (ref "CF3.1") (pin "LC1") (pinfunction "LC1_LC1") (pintype "passive"))
      (node (ref "CF3.1") (pin "LC2") (pinfunction "LC2_LC2") (pintype "passive"))
      (node (ref "CF3.2") (pin "27") (pinfunction "27_27") (pintype "passive"))
      (node (ref "CF3.2") (pin "28") (pinfunction "28_28") (pintype "passive"))
      (node (ref "CF3.2") (pin "29") (pinfunction "29_29") (pintype "passive"))
      (node (ref "CF3.2") (pin "30") (pinfunction "30_30") (pintype "passive"))
      (node (ref "CF3.2") (pin "31") (pinfunction "31_31") (pintype "passive"))
      (node (ref "CF3.2") (pin "32") (pinfunction "32_32") (pintype "passive"))
      (node (ref "CF3.2") (pin "37") (pinfunction "37_37") (pintype "passive"))
      (node (ref "CF3.2") (pin "38") (pinfunction "38_38") (pintype "passive"))
      (node (ref "CF3.2") (pin "LC1") (pinfunction "LC1_LC1") (pintype "passive"))
      (node (ref "CF3.2") (pin "LC2") (pinfunction "LC2_LC2") (pintype "passive"))
      (node (ref "CF4.1") (pin "LC1") (pinfunction "LC1_LC1") (pintype "passive"))
      (node (ref "CF4.1") (pin "LC2") (pinfunction "LC2_LC2") (pintype "passive"))
      (node (ref "CF4.2") (pin "27") (pinfunction "27_27") (pintype "passive"))
      (node (ref "CF4.2") (pin "28") (pinfunction "28_28") (pintype "passive"))
      (node (ref "CF4.2") (pin "29") (pinfunction "29_29") (pintype "passive"))
      (node (ref "CF4.2") (pin "30") (pinfunction "30_30") (pintype "passive"))
      (node (ref "CF4.2") (pin "31") (pinfunction "31_31") (pintype "passive"))
      (node (ref "CF4.2") (pin "32") (pinfunction "32_32") (pintype "passive"))
      (node (ref "CF4.2") (pin "37") (pinfunction "37_37") (pintype "passive"))
      (node (ref "CF4.2") (pin "38") (pinfunction "38_38") (pintype "passive"))
      (node (ref "CF4.2") (pin "LC1") (pinfunction "LC1_LC1") (pintype "passive"))
      (node (ref "CF4.2") (pin "LC2") (pinfunction "LC2_LC2") (pintype "passive"))
      (node (ref "CF5.1") (pin "LC1") (pinfunction "LC1_LC1") (pintype "passive"))
      (node (ref "CF5.1") (pin "LC2") (pinfunction "LC2_LC2") (pintype "passive"))
      (node (ref "CF5.2") (pin "27") (pinfunction "27_27") (pintype "passive"))
      (node (ref "CF5.2") (pin "28") (pinfunction "28_28") (pintype "passive"))
      (node (ref "CF5.2") (pin "29") (pinfunction "29_29") (pintype "passive"))
      (node (ref "CF5.2") (pin "30") (pinfunction "30_30") (pintype "passive"))
      (node (ref "CF5.2") (pin "31") (pinfunction "31_31") (pintype "passive"))
      (node (ref "CF5.2") (pin "32") (pinfunction "32_32") (pintype "passive"))
      (node (ref "CF5.2") (pin "37") (pinfunction "37_37") (pintype "passive"))
      (node (ref "CF5.2") (pin "38") (pinfunction "38_38") (pintype "passive"))
      (node (ref "CF5.2") (pin "LC1") (pinfunction "LC1_LC1") (pintype "passive"))
      (node (ref "CF5.2") (pin "LC2") (pinfunction "LC2_LC2") (pintype "passive"))
      (node (ref "CF6.1") (pin "LC1") (pinfunction "LC1_LC1") (pintype "passive"))
      (node (ref "CF6.1") (pin "LC2") (pinfunction "LC2_LC2") (pintype "passive"))
      (node (ref "CF6.2") (pin "27") (pinfunction "27_27") (pintype "passive"))
      (node (ref "CF6.2") (pin "28") (pinfunction "28_28") (pintype "passive"))
      (node (ref "CF6.2") (pin "29") (pinfunction "29_29") (pintype "passive"))
      (node (ref "CF6.2") (pin "30") (pinfunction "30_30") (pintype "passive"))
      (node (ref "CF6.2") (pin "31") (pinfunction "31_31") (pintype "passive"))
      (node (ref "CF6.2") (pin "32") (pinfunction "32_32") (pintype "passive"))
      (node (ref "CF6.2") (pin "37") (pinfunction "37_37") (pintype "passive"))
      (node (ref "CF6.2") (pin "38") (pinfunction "38_38") (pintype "passive"))
      (node (ref "CF6.2") (pin "LC1") (pinfunction "LC1_LC1") (pintype "passive"))
      (node (ref "CF6.2") (pin "LC2") (pinfunction "LC2_LC2") (pintype "passive"))
      (node (ref "CF7.1") (pin "LC1") (pinfunction "LC1_LC1") (pintype "passive"))
      (node (ref "CF7.1") (pin "LC2") (pinfunction "LC2_LC2") (pintype "passive"))
      (node (ref "CF7.2") (pin "27") (pinfunction "27_27") (pintype "passive"))
      (node (ref "CF7.2") (pin "28") (pinfunction "28_28") (pintype "passive"))
      (node (ref "CF7.2") (pin "29") (pinfunction "29_29") (pintype "passive"))
      (node (ref "CF7.2") (pin "30") (pinfunction "30_30") (pintype "passive"))
      (node (ref "CF7.2") (pin "31") (pinfunction "31_31") (pintype "passive"))
      (node (ref "CF7.2") (pin "32") (pinfunction "32_32") (pintype "passive"))
      (node (ref "CF7.2") (pin "37") (pinfunction "37_37") (pintype "passive"))
      (node (ref "CF7.2") (pin "38") (pinfunction "38_38") (pintype "passive"))
      (node (ref "CF7.2") (pin "LC1") (pinfunction "LC1_LC1") (pintype "passive"))
      (node (ref "CF7.2") (pin "LC2") (pinfunction "LC2_LC2") (pintype "passive"))
      (node (ref "CF8.1") (pin "LC1") (pinfunction "LC1_LC1") (pintype "passive"))
      (node (ref "CF8.1") (pin "LC2") (pinfunction "LC2_LC2") (pintype "passive"))
      (node (ref "CF8.2") (pin "27") (pinfunction "27_27") (pintype "passive"))
      (node (ref "CF8.2") (pin "28") (pinfunction "28_28") (pintype "passive"))
      (node (ref "CF8.2") (pin "29") (pinfunction "29_29") (pintype "passive"))
      (node (ref "CF8.2") (pin "30") (pinfunction "30_30") (pintype "passive"))
      (node (ref "CF8.2") (pin "31") (pinfunction "31_31") (pintype "passive"))
      (node (ref "CF8.2") (pin "32") (pinfunction "32_32") (pintype "passive"))
      (node (ref "CF8.2") (pin "37") (pinfunction "37_37") (pintype "passive"))
      (node (ref "CF8.2") (pin "38") (pinfunction "38_38") (pintype "passive"))
      (node (ref "CF8.2") (pin "LC1") (pinfunction "LC1_LC1") (pintype "passive"))
      (node (ref "CF8.2") (pin "LC2") (pinfunction "LC2_LC2") (pintype "passive"))
      (node (ref "CM1.1") (pin "P$1") (pinfunction "SHIELD1_P$1") (pintype "passive"))
      (node (ref "CM1.1") (pin "P$2") (pinfunction "SHIELD1_P$2") (pintype "passive"))
      (node (ref "CM1.1") (pin "P$3") (pinfunction "SHIELD1_P$3") (pintype "passive"))
      (node (ref "CM1.1") (pin "P$4") (pinfunction "SHIELD1_P$4") (pintype "passive"))
      (node (ref "CM2.1") (pin "P$1") (pinfunction "SHIELD1_P$1") (pintype "passive"))
      (node (ref "CM2.1") (pin "P$2") (pinfunction "SHIELD1_P$2") (pintype "passive"))
      (node (ref "CM2.1") (pin "P$3") (pinfunction "SHIELD1_P$3") (pintype "passive"))
      (node (ref "CM2.1") (pin "P$4") (pinfunction "SHIELD1_P$4") (pintype "passive"))
      (node (ref "CM2.2") (pin "P$1") (pinfunction "SHIELD1_P$1") (pintype "passive"))
      (node (ref "CM2.2") (pin "P$2") (pinfunction "SHIELD1_P$2") (pintype "passive"))
      (node (ref "CM2.2") (pin "P$3") (pinfunction "SHIELD1_P$3") (pintype "passive"))
      (node (ref "CM2.2") (pin "P$4") (pinfunction "SHIELD1_P$4") (pintype "passive"))
      (node (ref "CM20.1") (pin "P$1") (pinfunction "SHIELD1_P$1") (pintype "passive"))
      (node (ref "CM20.1") (pin "P$2") (pinfunction "SHIELD1_P$2") (pintype "passive"))
      (node (ref "CM20.1") (pin "P$3") (pinfunction "SHIELD1_P$3") (pintype "passive"))
      (node (ref "CM20.1") (pin "P$4") (pinfunction "SHIELD1_P$4") (pintype "passive"))
      (node (ref "CM20.2") (pin "P$1") (pinfunction "SHIELD1_P$1") (pintype "passive"))
      (node (ref "CM20.2") (pin "P$2") (pinfunction "SHIELD1_P$2") (pintype "passive"))
      (node (ref "CM20.2") (pin "P$3") (pinfunction "SHIELD1_P$3") (pintype "passive"))
      (node (ref "CM20.2") (pin "P$4") (pinfunction "SHIELD1_P$4") (pintype "passive"))
      (node (ref "CM20.3") (pin "P$1") (pinfunction "SHIELD1_P$1") (pintype "passive"))
      (node (ref "CM20.3") (pin "P$2") (pinfunction "SHIELD1_P$2") (pintype "passive"))
      (node (ref "CM20.3") (pin "P$3") (pinfunction "SHIELD1_P$3") (pintype "passive"))
      (node (ref "CM20.3") (pin "P$4") (pinfunction "SHIELD1_P$4") (pintype "passive"))
      (node (ref "CM20.4") (pin "P$1") (pinfunction "SHIELD1_P$1") (pintype "passive"))
      (node (ref "CM20.4") (pin "P$2") (pinfunction "SHIELD1_P$2") (pintype "passive"))
      (node (ref "CM20.4") (pin "P$3") (pinfunction "SHIELD1_P$3") (pintype "passive"))
      (node (ref "CM20.4") (pin "P$4") (pinfunction "SHIELD1_P$4") (pintype "passive"))
      (node (ref "CM20.5") (pin "P$1") (pinfunction "SHIELD1_P$1") (pintype "passive"))
      (node (ref "CM20.5") (pin "P$2") (pinfunction "SHIELD1_P$2") (pintype "passive"))
      (node (ref "CM20.5") (pin "P$3") (pinfunction "SHIELD1_P$3") (pintype "passive"))
      (node (ref "CM20.5") (pin "P$4") (pinfunction "SHIELD1_P$4") (pintype "passive"))
      (node (ref "CM20.6") (pin "P$1") (pinfunction "SHIELD1_P$1") (pintype "passive"))
      (node (ref "CM20.6") (pin "P$2") (pinfunction "SHIELD1_P$2") (pintype "passive"))
      (node (ref "CM20.6") (pin "P$3") (pinfunction "SHIELD1_P$3") (pintype "passive"))
      (node (ref "CM20.6") (pin "P$4") (pinfunction "SHIELD1_P$4") (pintype "passive"))
      (node (ref "CM20.7") (pin "P$1") (pinfunction "SHIELD1_P$1") (pintype "passive"))
      (node (ref "CM20.7") (pin "P$2") (pinfunction "SHIELD1_P$2") (pintype "passive"))
      (node (ref "CM20.7") (pin "P$3") (pinfunction "SHIELD1_P$3") (pintype "passive"))
      (node (ref "CM20.7") (pin "P$4") (pinfunction "SHIELD1_P$4") (pintype "passive"))
    )
    (net (code "16") (name "L-GPS") (class "Default")
      (node (ref "CM20.4") (pin "RF-DOWN") (pinfunction "RF_RF-DOWN") (pintype "passive"))
      (node (ref "CM20.7") (pin "RF-DOWN") (pinfunction "RF_RF-DOWN") (pintype "passive"))
    )
    (net (code "17") (name "L-TURNSTILE") (class "Default")
      (node (ref "CM20.2") (pin "RF-DOWN") (pinfunction "RF_RF-DOWN") (pintype "passive"))
      (node (ref "CM20.5") (pin "RF-DOWN") (pinfunction "RF_RF-DOWN") (pintype "passive"))
    )
    (net (code "18") (name "Net-(C1-Pad1)") (class "Default")
      (node (ref "C1") (pin "1") (pinfunction "1_1") (pintype "passive"))
      (node (ref "R1") (pin "2") (pinfunction "2_2") (pintype "passive"))
      (node (ref "R2") (pin "2") (pinfunction "2_2") (pintype "passive"))
    )
    (net (code "19") (name "Net-(C2-Pad1)") (class "Default")
      (node (ref "C2") (pin "1") (pinfunction "1_1") (pintype "passive"))
      (node (ref "R3") (pin "2") (pinfunction "2_2") (pintype "passive"))
      (node (ref "R4") (pin "2") (pinfunction "2_2") (pintype "passive"))
    )
    (net (code "20") (name "Net-(C3-Pad1)") (class "Default")
      (node (ref "C3") (pin "1") (pinfunction "1_1") (pintype "passive"))
      (node (ref "R5") (pin "2") (pinfunction "2_2") (pintype "passive"))
      (node (ref "R6") (pin "2") (pinfunction "2_2") (pintype "passive"))
    )
    (net (code "21") (name "Net-(C4-Pad1)") (class "Default")
      (node (ref "C4") (pin "1") (pinfunction "1_1") (pintype "passive"))
      (node (ref "R7") (pin "2") (pinfunction "2_2") (pintype "passive"))
      (node (ref "R8") (pin "2") (pinfunction "2_2") (pintype "passive"))
    )
    (net (code "22") (name "OPD_PWR") (class "Default")
      (node (ref "CF12.2") (pin "15") (pinfunction "15_15") (pintype "passive"))
      (node (ref "CF12.2") (pin "16") (pinfunction "16_16") (pintype "passive"))
      (node (ref "CF13.2") (pin "15") (pinfunction "15_15") (pintype "passive"))
      (node (ref "CF13.2") (pin "16") (pinfunction "16_16") (pintype "passive"))
      (node (ref "CF14.2") (pin "15") (pinfunction "15_15") (pintype "passive"))
      (node (ref "CF14.2") (pin "16") (pinfunction "16_16") (pintype "passive"))
      (node (ref "CF15.2") (pin "15") (pinfunction "15_15") (pintype "passive"))
      (node (ref "CF15.2") (pin "16") (pinfunction "16_16") (pintype "passive"))
      (node (ref "CF16.2") (pin "15") (pinfunction "15_15") (pintype "passive"))
      (node (ref "CF16.2") (pin "16") (pinfunction "16_16") (pintype "passive"))
      (node (ref "CF17.2") (pin "15") (pinfunction "15_15") (pintype "passive"))
      (node (ref "CF17.2") (pin "16") (pinfunction "16_16") (pintype "passive"))
      (node (ref "CF18.2") (pin "15") (pinfunction "15_15") (pintype "passive"))
      (node (ref "CF18.2") (pin "16") (pinfunction "16_16") (pintype "passive"))
      (node (ref "CF19.2") (pin "15") (pinfunction "15_15") (pintype "passive"))
      (node (ref "CF19.2") (pin "16") (pinfunction "16_16") (pintype "passive"))
      (node (ref "CF2.2") (pin "15") (pinfunction "15_15") (pintype "passive"))
      (node (ref "CF2.2") (pin "16") (pinfunction "16_16") (pintype "passive"))
      (node (ref "CF2.3") (pin "15") (pinfunction "15_15") (pintype "passive"))
      (node (ref "CF2.3") (pin "16") (pinfunction "16_16") (pintype "passive"))
      (node (ref "CF2.4") (pin "15") (pinfunction "15_15") (pintype "passive"))
      (node (ref "CF2.4") (pin "16") (pinfunction "16_16") (pintype "passive"))
      (node (ref "CF3.2") (pin "15") (pinfunction "15_15") (pintype "passive"))
      (node (ref "CF3.2") (pin "16") (pinfunction "16_16") (pintype "passive"))
      (node (ref "CF4.2") (pin "15") (pinfunction "15_15") (pintype "passive"))
      (node (ref "CF4.2") (pin "16") (pinfunction "16_16") (pintype "passive"))
      (node (ref "CF5.2") (pin "15") (pinfunction "15_15") (pintype "passive"))
      (node (ref "CF5.2") (pin "16") (pinfunction "16_16") (pintype "passive"))
      (node (ref "CF6.2") (pin "15") (pinfunction "15_15") (pintype "passive"))
      (node (ref "CF6.2") (pin "16") (pinfunction "16_16") (pintype "passive"))
      (node (ref "CF7.2") (pin "15") (pinfunction "15_15") (pintype "passive"))
      (node (ref "CF7.2") (pin "16") (pinfunction "16_16") (pintype "passive"))
      (node (ref "CF8.2") (pin "15") (pinfunction "15_15") (pintype "passive"))
      (node (ref "CF8.2") (pin "16") (pinfunction "16_16") (pintype "passive"))
    )
    (net (code "23") (name "OPD_SCL") (class "Default")
      (node (ref "CF12.2") (pin "13") (pinfunction "13_13") (pintype "passive"))
      (node (ref "CF12.2") (pin "14") (pinfunction "14_14") (pintype "passive"))
      (node (ref "CF13.2") (pin "13") (pinfunction "13_13") (pintype "passive"))
      (node (ref "CF13.2") (pin "14") (pinfunction "14_14") (pintype "passive"))
      (node (ref "CF14.2") (pin "13") (pinfunction "13_13") (pintype "passive"))
      (node (ref "CF14.2") (pin "14") (pinfunction "14_14") (pintype "passive"))
      (node (ref "CF15.2") (pin "13") (pinfunction "13_13") (pintype "passive"))
      (node (ref "CF15.2") (pin "14") (pinfunction "14_14") (pintype "passive"))
      (node (ref "CF16.2") (pin "13") (pinfunction "13_13") (pintype "passive"))
      (node (ref "CF16.2") (pin "14") (pinfunction "14_14") (pintype "passive"))
      (node (ref "CF17.2") (pin "13") (pinfunction "13_13") (pintype "passive"))
      (node (ref "CF17.2") (pin "14") (pinfunction "14_14") (pintype "passive"))
      (node (ref "CF18.2") (pin "13") (pinfunction "13_13") (pintype "passive"))
      (node (ref "CF18.2") (pin "14") (pinfunction "14_14") (pintype "passive"))
      (node (ref "CF19.2") (pin "13") (pinfunction "13_13") (pintype "passive"))
      (node (ref "CF19.2") (pin "14") (pinfunction "14_14") (pintype "passive"))
      (node (ref "CF2.2") (pin "13") (pinfunction "13_13") (pintype "passive"))
      (node (ref "CF2.2") (pin "14") (pinfunction "14_14") (pintype "passive"))
      (node (ref "CF2.3") (pin "13") (pinfunction "13_13") (pintype "passive"))
      (node (ref "CF2.3") (pin "14") (pinfunction "14_14") (pintype "passive"))
      (node (ref "CF2.4") (pin "13") (pinfunction "13_13") (pintype "passive"))
      (node (ref "CF2.4") (pin "14") (pinfunction "14_14") (pintype "passive"))
      (node (ref "CF3.2") (pin "13") (pinfunction "13_13") (pintype "passive"))
      (node (ref "CF3.2") (pin "14") (pinfunction "14_14") (pintype "passive"))
      (node (ref "CF4.2") (pin "13") (pinfunction "13_13") (pintype "passive"))
      (node (ref "CF4.2") (pin "14") (pinfunction "14_14") (pintype "passive"))
      (node (ref "CF5.2") (pin "13") (pinfunction "13_13") (pintype "passive"))
      (node (ref "CF5.2") (pin "14") (pinfunction "14_14") (pintype "passive"))
      (node (ref "CF6.2") (pin "13") (pinfunction "13_13") (pintype "passive"))
      (node (ref "CF6.2") (pin "14") (pinfunction "14_14") (pintype "passive"))
      (node (ref "CF7.2") (pin "13") (pinfunction "13_13") (pintype "passive"))
      (node (ref "CF7.2") (pin "14") (pinfunction "14_14") (pintype "passive"))
      (node (ref "CF8.2") (pin "13") (pinfunction "13_13") (pintype "passive"))
      (node (ref "CF8.2") (pin "14") (pinfunction "14_14") (pintype "passive"))
    )
    (net (code "24") (name "OPD_SDA") (class "Default")
      (node (ref "CF12.2") (pin "11") (pinfunction "11_11") (pintype "passive"))
      (node (ref "CF12.2") (pin "12") (pinfunction "12_12") (pintype "passive"))
      (node (ref "CF13.2") (pin "11") (pinfunction "11_11") (pintype "passive"))
      (node (ref "CF13.2") (pin "12") (pinfunction "12_12") (pintype "passive"))
      (node (ref "CF14.2") (pin "11") (pinfunction "11_11") (pintype "passive"))
      (node (ref "CF14.2") (pin "12") (pinfunction "12_12") (pintype "passive"))
      (node (ref "CF15.2") (pin "11") (pinfunction "11_11") (pintype "passive"))
      (node (ref "CF15.2") (pin "12") (pinfunction "12_12") (pintype "passive"))
      (node (ref "CF16.2") (pin "11") (pinfunction "11_11") (pintype "passive"))
      (node (ref "CF16.2") (pin "12") (pinfunction "12_12") (pintype "passive"))
      (node (ref "CF17.2") (pin "11") (pinfunction "11_11") (pintype "passive"))
      (node (ref "CF17.2") (pin "12") (pinfunction "12_12") (pintype "passive"))
      (node (ref "CF18.2") (pin "11") (pinfunction "11_11") (pintype "passive"))
      (node (ref "CF18.2") (pin "12") (pinfunction "12_12") (pintype "passive"))
      (node (ref "CF19.2") (pin "11") (pinfunction "11_11") (pintype "passive"))
      (node (ref "CF19.2") (pin "12") (pinfunction "12_12") (pintype "passive"))
      (node (ref "CF2.2") (pin "11") (pinfunction "11_11") (pintype "passive"))
      (node (ref "CF2.2") (pin "12") (pinfunction "12_12") (pintype "passive"))
      (node (ref "CF2.3") (pin "11") (pinfunction "11_11") (pintype "passive"))
      (node (ref "CF2.3") (pin "12") (pinfunction "12_12") (pintype "passive"))
      (node (ref "CF2.4") (pin "11") (pinfunction "11_11") (pintype "passive"))
      (node (ref "CF2.4") (pin "12") (pinfunction "12_12") (pintype "passive"))
      (node (ref "CF3.2") (pin "11") (pinfunction "11_11") (pintype "passive"))
      (node (ref "CF3.2") (pin "12") (pinfunction "12_12") (pintype "passive"))
      (node (ref "CF4.2") (pin "11") (pinfunction "11_11") (pintype "passive"))
      (node (ref "CF4.2") (pin "12") (pinfunction "12_12") (pintype "passive"))
      (node (ref "CF5.2") (pin "11") (pinfunction "11_11") (pintype "passive"))
      (node (ref "CF5.2") (pin "12") (pinfunction "12_12") (pintype "passive"))
      (node (ref "CF6.2") (pin "11") (pinfunction "11_11") (pintype "passive"))
      (node (ref "CF6.2") (pin "12") (pinfunction "12_12") (pintype "passive"))
      (node (ref "CF7.2") (pin "11") (pinfunction "11_11") (pintype "passive"))
      (node (ref "CF7.2") (pin "12") (pinfunction "12_12") (pintype "passive"))
      (node (ref "CF8.2") (pin "11") (pinfunction "11_11") (pintype "passive"))
      (node (ref "CF8.2") (pin "12") (pinfunction "12_12") (pintype "passive"))
    )
    (net (code "25") (name "S-HELICAL") (class "Default")
      (node (ref "CM1.1") (pin "RF-DOWN") (pinfunction "RF_RF-DOWN") (pintype "passive"))
      (node (ref "CM2.1") (pin "RF-DOWN") (pinfunction "RF_RF-DOWN") (pintype "passive"))
    )
    (net (code "26") (name "S-TURNSTILE") (class "Default")
      (node (ref "CM2.2") (pin "RF-DOWN") (pinfunction "RF_RF-DOWN") (pintype "passive"))
      (node (ref "CM20.3") (pin "RF-DOWN") (pinfunction "RF_RF-DOWN") (pintype "passive"))
    )
    (net (code "27") (name "SPARE1") (class "Default")
      (node (ref "CF12.2") (pin "10") (pinfunction "10_10") (pintype "passive"))
      (node (ref "CF12.2") (pin "9") (pinfunction "9_9") (pintype "passive"))
      (node (ref "CF13.2") (pin "10") (pinfunction "10_10") (pintype "passive"))
      (node (ref "CF13.2") (pin "9") (pinfunction "9_9") (pintype "passive"))
      (node (ref "CF14.2") (pin "10") (pinfunction "10_10") (pintype "passive"))
      (node (ref "CF14.2") (pin "9") (pinfunction "9_9") (pintype "passive"))
      (node (ref "CF15.2") (pin "10") (pinfunction "10_10") (pintype "passive"))
      (node (ref "CF15.2") (pin "9") (pinfunction "9_9") (pintype "passive"))
      (node (ref "CF16.2") (pin "10") (pinfunction "10_10") (pintype "passive"))
      (node (ref "CF16.2") (pin "9") (pinfunction "9_9") (pintype "passive"))
      (node (ref "CF17.2") (pin "10") (pinfunction "10_10") (pintype "passive"))
      (node (ref "CF17.2") (pin "9") (pinfunction "9_9") (pintype "passive"))
      (node (ref "CF18.2") (pin "10") (pinfunction "10_10") (pintype "passive"))
      (node (ref "CF18.2") (pin "9") (pinfunction "9_9") (pintype "passive"))
      (node (ref "CF19.2") (pin "10") (pinfunction "10_10") (pintype "passive"))
      (node (ref "CF19.2") (pin "9") (pinfunction "9_9") (pintype "passive"))
      (node (ref "CF2.2") (pin "10") (pinfunction "10_10") (pintype "passive"))
      (node (ref "CF2.2") (pin "9") (pinfunction "9_9") (pintype "passive"))
      (node (ref "CF2.3") (pin "10") (pinfunction "10_10") (pintype "passive"))
      (node (ref "CF2.3") (pin "9") (pinfunction "9_9") (pintype "passive"))
      (node (ref "CF2.4") (pin "10") (pinfunction "10_10") (pintype "passive"))
      (node (ref "CF2.4") (pin "9") (pinfunction "9_9") (pintype "passive"))
      (node (ref "CF3.2") (pin "10") (pinfunction "10_10") (pintype "passive"))
      (node (ref "CF3.2") (pin "9") (pinfunction "9_9") (pintype "passive"))
      (node (ref "CF4.2") (pin "10") (pinfunction "10_10") (pintype "passive"))
      (node (ref "CF4.2") (pin "9") (pinfunction "9_9") (pintype "passive"))
      (node (ref "CF5.2") (pin "10") (pinfunction "10_10") (pintype "passive"))
      (node (ref "CF5.2") (pin "9") (pinfunction "9_9") (pintype "passive"))
      (node (ref "CF6.2") (pin "10") (pinfunction "10_10") (pintype "passive"))
      (node (ref "CF6.2") (pin "9") (pinfunction "9_9") (pintype "passive"))
      (node (ref "CF7.2") (pin "10") (pinfunction "10_10") (pintype "passive"))
      (node (ref "CF7.2") (pin "9") (pinfunction "9_9") (pintype "passive"))
      (node (ref "CF8.2") (pin "10") (pinfunction "10_10") (pintype "passive"))
      (node (ref "CF8.2") (pin "9") (pinfunction "9_9") (pintype "passive"))
    )
    (net (code "28") (name "SPARE2") (class "Default")
      (node (ref "CF12.2") (pin "7") (pinfunction "7_7") (pintype "passive"))
      (node (ref "CF12.2") (pin "8") (pinfunction "8_8") (pintype "passive"))
      (node (ref "CF13.2") (pin "7") (pinfunction "7_7") (pintype "passive"))
      (node (ref "CF13.2") (pin "8") (pinfunction "8_8") (pintype "passive"))
      (node (ref "CF14.2") (pin "7") (pinfunction "7_7") (pintype "passive"))
      (node (ref "CF14.2") (pin "8") (pinfunction "8_8") (pintype "passive"))
      (node (ref "CF15.2") (pin "7") (pinfunction "7_7") (pintype "passive"))
      (node (ref "CF15.2") (pin "8") (pinfunction "8_8") (pintype "passive"))
      (node (ref "CF16.2") (pin "7") (pinfunction "7_7") (pintype "passive"))
      (node (ref "CF16.2") (pin "8") (pinfunction "8_8") (pintype "passive"))
      (node (ref "CF17.2") (pin "7") (pinfunction "7_7") (pintype "passive"))
      (node (ref "CF17.2") (pin "8") (pinfunction "8_8") (pintype "passive"))
      (node (ref "CF18.2") (pin "7") (pinfunction "7_7") (pintype "passive"))
      (node (ref "CF18.2") (pin "8") (pinfunction "8_8") (pintype "passive"))
      (node (ref "CF19.2") (pin "7") (pinfunction "7_7") (pintype "passive"))
      (node (ref "CF19.2") (pin "8") (pinfunction "8_8") (pintype "passive"))
      (node (ref "CF2.2") (pin "7") (pinfunction "7_7") (pintype "passive"))
      (node (ref "CF2.2") (pin "8") (pinfunction "8_8") (pintype "passive"))
      (node (ref "CF2.3") (pin "7") (pinfunction "7_7") (pintype "passive"))
      (node (ref "CF2.3") (pin "8") (pinfunction "8_8") (pintype "passive"))
      (node (ref "CF2.4") (pin "7") (pinfunction "7_7") (pintype "passive"))
      (node (ref "CF2.4") (pin "8") (pinfunction "8_8") (pintype "passive"))
      (node (ref "CF3.2") (pin "7") (pinfunction "7_7") (pintype "passive"))
      (node (ref "CF3.2") (pin "8") (pinfunction "8_8") (pintype "passive"))
      (node (ref "CF4.2") (pin "7") (pinfunction "7_7") (pintype "passive"))
      (node (ref "CF4.2") (pin "8") (pinfunction "8_8") (pintype "passive"))
      (node (ref "CF5.2") (pin "7") (pinfunction "7_7") (pintype "passive"))
      (node (ref "CF5.2") (pin "8") (pinfunction "8_8") (pintype "passive"))
      (node (ref "CF6.2") (pin "7") (pinfunction "7_7") (pintype "passive"))
      (node (ref "CF6.2") (pin "8") (pinfunction "8_8") (pintype "passive"))
      (node (ref "CF7.2") (pin "7") (pinfunction "7_7") (pintype "passive"))
      (node (ref "CF7.2") (pin "8") (pinfunction "8_8") (pintype "passive"))
      (node (ref "CF8.2") (pin "7") (pinfunction "7_7") (pintype "passive"))
      (node (ref "CF8.2") (pin "8") (pinfunction "8_8") (pintype "passive"))
    )
    (net (code "29") (name "SPARE3") (class "Default")
      (node (ref "CF12.2") (pin "5") (pinfunction "5_5") (pintype "passive"))
      (node (ref "CF12.2") (pin "6") (pinfunction "6_6") (pintype "passive"))
      (node (ref "CF13.2") (pin "5") (pinfunction "5_5") (pintype "passive"))
      (node (ref "CF13.2") (pin "6") (pinfunction "6_6") (pintype "passive"))
      (node (ref "CF14.2") (pin "5") (pinfunction "5_5") (pintype "passive"))
      (node (ref "CF14.2") (pin "6") (pinfunction "6_6") (pintype "passive"))
      (node (ref "CF15.2") (pin "5") (pinfunction "5_5") (pintype "passive"))
      (node (ref "CF15.2") (pin "6") (pinfunction "6_6") (pintype "passive"))
      (node (ref "CF16.2") (pin "5") (pinfunction "5_5") (pintype "passive"))
      (node (ref "CF16.2") (pin "6") (pinfunction "6_6") (pintype "passive"))
      (node (ref "CF17.2") (pin "5") (pinfunction "5_5") (pintype "passive"))
      (node (ref "CF17.2") (pin "6") (pinfunction "6_6") (pintype "passive"))
      (node (ref "CF18.2") (pin "5") (pinfunction "5_5") (pintype "passive"))
      (node (ref "CF18.2") (pin "6") (pinfunction "6_6") (pintype "passive"))
      (node (ref "CF19.2") (pin "5") (pinfunction "5_5") (pintype "passive"))
      (node (ref "CF19.2") (pin "6") (pinfunction "6_6") (pintype "passive"))
      (node (ref "CF2.2") (pin "5") (pinfunction "5_5") (pintype "passive"))
      (node (ref "CF2.2") (pin "6") (pinfunction "6_6") (pintype "passive"))
      (node (ref "CF2.3") (pin "5") (pinfunction "5_5") (pintype "passive"))
      (node (ref "CF2.3") (pin "6") (pinfunction "6_6") (pintype "passive"))
      (node (ref "CF2.4") (pin "5") (pinfunction "5_5") (pintype "passive"))
      (node (ref "CF2.4") (pin "6") (pinfunction "6_6") (pintype "passive"))
      (node (ref "CF3.2") (pin "5") (pinfunction "5_5") (pintype "passive"))
      (node (ref "CF3.2") (pin "6") (pinfunction "6_6") (pintype "passive"))
      (node (ref "CF4.2") (pin "5") (pinfunction "5_5") (pintype "passive"))
      (node (ref "CF4.2") (pin "6") (pinfunction "6_6") (pintype "passive"))
      (node (ref "CF5.2") (pin "5") (pinfunction "5_5") (pintype "passive"))
      (node (ref "CF5.2") (pin "6") (pinfunction "6_6") (pintype "passive"))
      (node (ref "CF6.2") (pin "5") (pinfunction "5_5") (pintype "passive"))
      (node (ref "CF6.2") (pin "6") (pinfunction "6_6") (pintype "passive"))
      (node (ref "CF7.2") (pin "5") (pinfunction "5_5") (pintype "passive"))
      (node (ref "CF7.2") (pin "6") (pinfunction "6_6") (pintype "passive"))
      (node (ref "CF8.2") (pin "5") (pinfunction "5_5") (pintype "passive"))
      (node (ref "CF8.2") (pin "6") (pinfunction "6_6") (pintype "passive"))
    )
    (net (code "30") (name "SPARE4") (class "Default")
      (node (ref "CF12.2") (pin "3") (pinfunction "3_3") (pintype "passive"))
      (node (ref "CF12.2") (pin "4") (pinfunction "4_4") (pintype "passive"))
      (node (ref "CF13.2") (pin "3") (pinfunction "3_3") (pintype "passive"))
      (node (ref "CF13.2") (pin "4") (pinfunction "4_4") (pintype "passive"))
      (node (ref "CF14.2") (pin "3") (pinfunction "3_3") (pintype "passive"))
      (node (ref "CF14.2") (pin "4") (pinfunction "4_4") (pintype "passive"))
      (node (ref "CF15.2") (pin "3") (pinfunction "3_3") (pintype "passive"))
      (node (ref "CF15.2") (pin "4") (pinfunction "4_4") (pintype "passive"))
      (node (ref "CF16.2") (pin "3") (pinfunction "3_3") (pintype "passive"))
      (node (ref "CF16.2") (pin "4") (pinfunction "4_4") (pintype "passive"))
      (node (ref "CF17.2") (pin "3") (pinfunction "3_3") (pintype "passive"))
      (node (ref "CF17.2") (pin "4") (pinfunction "4_4") (pintype "passive"))
      (node (ref "CF18.2") (pin "3") (pinfunction "3_3") (pintype "passive"))
      (node (ref "CF18.2") (pin "4") (pinfunction "4_4") (pintype "passive"))
      (node (ref "CF19.2") (pin "3") (pinfunction "3_3") (pintype "passive"))
      (node (ref "CF19.2") (pin "4") (pinfunction "4_4") (pintype "passive"))
      (node (ref "CF2.2") (pin "3") (pinfunction "3_3") (pintype "passive"))
      (node (ref "CF2.2") (pin "4") (pinfunction "4_4") (pintype "passive"))
      (node (ref "CF2.3") (pin "3") (pinfunction "3_3") (pintype "passive"))
      (node (ref "CF2.3") (pin "4") (pinfunction "4_4") (pintype "passive"))
      (node (ref "CF2.4") (pin "3") (pinfunction "3_3") (pintype "passive"))
      (node (ref "CF2.4") (pin "4") (pinfunction "4_4") (pintype "passive"))
      (node (ref "CF3.2") (pin "3") (pinfunction "3_3") (pintype "passive"))
      (node (ref "CF3.2") (pin "4") (pinfunction "4_4") (pintype "passive"))
      (node (ref "CF4.2") (pin "3") (pinfunction "3_3") (pintype "passive"))
      (node (ref "CF4.2") (pin "4") (pinfunction "4_4") (pintype "passive"))
      (node (ref "CF5.2") (pin "3") (pinfunction "3_3") (pintype "passive"))
      (node (ref "CF5.2") (pin "4") (pinfunction "4_4") (pintype "passive"))
      (node (ref "CF6.2") (pin "3") (pinfunction "3_3") (pintype "passive"))
      (node (ref "CF6.2") (pin "4") (pinfunction "4_4") (pintype "passive"))
      (node (ref "CF7.2") (pin "3") (pinfunction "3_3") (pintype "passive"))
      (node (ref "CF7.2") (pin "4") (pinfunction "4_4") (pintype "passive"))
      (node (ref "CF8.2") (pin "3") (pinfunction "3_3") (pintype "passive"))
      (node (ref "CF8.2") (pin "4") (pinfunction "4_4") (pintype "passive"))
    )
    (net (code "31") (name "SPARE5") (class "Default")
      (node (ref "CF12.2") (pin "1") (pinfunction "1_1") (pintype "passive"))
      (node (ref "CF12.2") (pin "2") (pinfunction "2_2") (pintype "passive"))
      (node (ref "CF13.2") (pin "1") (pinfunction "1_1") (pintype "passive"))
      (node (ref "CF13.2") (pin "2") (pinfunction "2_2") (pintype "passive"))
      (node (ref "CF14.2") (pin "1") (pinfunction "1_1") (pintype "passive"))
      (node (ref "CF14.2") (pin "2") (pinfunction "2_2") (pintype "passive"))
      (node (ref "CF15.2") (pin "1") (pinfunction "1_1") (pintype "passive"))
      (node (ref "CF15.2") (pin "2") (pinfunction "2_2") (pintype "passive"))
      (node (ref "CF16.2") (pin "1") (pinfunction "1_1") (pintype "passive"))
      (node (ref "CF16.2") (pin "2") (pinfunction "2_2") (pintype "passive"))
      (node (ref "CF17.2") (pin "1") (pinfunction "1_1") (pintype "passive"))
      (node (ref "CF17.2") (pin "2") (pinfunction "2_2") (pintype "passive"))
      (node (ref "CF18.2") (pin "1") (pinfunction "1_1") (pintype "passive"))
      (node (ref "CF18.2") (pin "2") (pinfunction "2_2") (pintype "passive"))
      (node (ref "CF19.2") (pin "1") (pinfunction "1_1") (pintype "passive"))
      (node (ref "CF19.2") (pin "2") (pinfunction "2_2") (pintype "passive"))
      (node (ref "CF2.2") (pin "1") (pinfunction "1_1") (pintype "passive"))
      (node (ref "CF2.2") (pin "2") (pinfunction "2_2") (pintype "passive"))
      (node (ref "CF2.3") (pin "1") (pinfunction "1_1") (pintype "passive"))
      (node (ref "CF2.3") (pin "2") (pinfunction "2_2") (pintype "passive"))
      (node (ref "CF2.4") (pin "1") (pinfunction "1_1") (pintype "passive"))
      (node (ref "CF2.4") (pin "2") (pinfunction "2_2") (pintype "passive"))
      (node (ref "CF3.2") (pin "1") (pinfunction "1_1") (pintype "passive"))
      (node (ref "CF3.2") (pin "2") (pinfunction "2_2") (pintype "passive"))
      (node (ref "CF4.2") (pin "1") (pinfunction "1_1") (pintype "passive"))
      (node (ref "CF4.2") (pin "2") (pinfunction "2_2") (pintype "passive"))
      (node (ref "CF5.2") (pin "1") (pinfunction "1_1") (pintype "passive"))
      (node (ref "CF5.2") (pin "2") (pinfunction "2_2") (pintype "passive"))
      (node (ref "CF6.2") (pin "1") (pinfunction "1_1") (pintype "passive"))
      (node (ref "CF6.2") (pin "2") (pinfunction "2_2") (pintype "passive"))
      (node (ref "CF7.2") (pin "1") (pinfunction "1_1") (pintype "passive"))
      (node (ref "CF7.2") (pin "2") (pinfunction "2_2") (pintype "passive"))
      (node (ref "CF8.2") (pin "1") (pinfunction "1_1") (pintype "passive"))
      (node (ref "CF8.2") (pin "2") (pinfunction "2_2") (pintype "passive"))
    )
    (net (code "32") (name "VBUS") (class "Default")
      (node (ref "CF12.2") (pin "21") (pinfunction "21_21") (pintype "passive"))
      (node (ref "CF12.2") (pin "22") (pinfunction "22_22") (pintype "passive"))
      (node (ref "CF12.2") (pin "23") (pinfunction "23_23") (pintype "passive"))
      (node (ref "CF12.2") (pin "24") (pinfunction "24_24") (pintype "passive"))
      (node (ref "CF12.2") (pin "25") (pinfunction "25_25") (pintype "passive"))
      (node (ref "CF12.2") (pin "26") (pinfunction "26_26") (pintype "passive"))
      (node (ref "CF13.2") (pin "21") (pinfunction "21_21") (pintype "passive"))
      (node (ref "CF13.2") (pin "22") (pinfunction "22_22") (pintype "passive"))
      (node (ref "CF13.2") (pin "23") (pinfunction "23_23") (pintype "passive"))
      (node (ref "CF13.2") (pin "24") (pinfunction "24_24") (pintype "passive"))
      (node (ref "CF13.2") (pin "25") (pinfunction "25_25") (pintype "passive"))
      (node (ref "CF13.2") (pin "26") (pinfunction "26_26") (pintype "passive"))
      (node (ref "CF14.2") (pin "21") (pinfunction "21_21") (pintype "passive"))
      (node (ref "CF14.2") (pin "22") (pinfunction "22_22") (pintype "passive"))
      (node (ref "CF14.2") (pin "23") (pinfunction "23_23") (pintype "passive"))
      (node (ref "CF14.2") (pin "24") (pinfunction "24_24") (pintype "passive"))
      (node (ref "CF14.2") (pin "25") (pinfunction "25_25") (pintype "passive"))
      (node (ref "CF14.2") (pin "26") (pinfunction "26_26") (pintype "passive"))
      (node (ref "CF15.2") (pin "21") (pinfunction "21_21") (pintype "passive"))
      (node (ref "CF15.2") (pin "22") (pinfunction "22_22") (pintype "passive"))
      (node (ref "CF15.2") (pin "23") (pinfunction "23_23") (pintype "passive"))
      (node (ref "CF15.2") (pin "24") (pinfunction "24_24") (pintype "passive"))
      (node (ref "CF15.2") (pin "25") (pinfunction "25_25") (pintype "passive"))
      (node (ref "CF15.2") (pin "26") (pinfunction "26_26") (pintype "passive"))
      (node (ref "CF16.2") (pin "21") (pinfunction "21_21") (pintype "passive"))
      (node (ref "CF16.2") (pin "22") (pinfunction "22_22") (pintype "passive"))
      (node (ref "CF16.2") (pin "23") (pinfunction "23_23") (pintype "passive"))
      (node (ref "CF16.2") (pin "24") (pinfunction "24_24") (pintype "passive"))
      (node (ref "CF16.2") (pin "25") (pinfunction "25_25") (pintype "passive"))
      (node (ref "CF16.2") (pin "26") (pinfunction "26_26") (pintype "passive"))
      (node (ref "CF17.2") (pin "21") (pinfunction "21_21") (pintype "passive"))
      (node (ref "CF17.2") (pin "22") (pinfunction "22_22") (pintype "passive"))
      (node (ref "CF17.2") (pin "23") (pinfunction "23_23") (pintype "passive"))
      (node (ref "CF17.2") (pin "24") (pinfunction "24_24") (pintype "passive"))
      (node (ref "CF17.2") (pin "25") (pinfunction "25_25") (pintype "passive"))
      (node (ref "CF17.2") (pin "26") (pinfunction "26_26") (pintype "passive"))
      (node (ref "CF18.2") (pin "21") (pinfunction "21_21") (pintype "passive"))
      (node (ref "CF18.2") (pin "22") (pinfunction "22_22") (pintype "passive"))
      (node (ref "CF18.2") (pin "23") (pinfunction "23_23") (pintype "passive"))
      (node (ref "CF18.2") (pin "24") (pinfunction "24_24") (pintype "passive"))
      (node (ref "CF18.2") (pin "25") (pinfunction "25_25") (pintype "passive"))
      (node (ref "CF18.2") (pin "26") (pinfunction "26_26") (pintype "passive"))
      (node (ref "CF19.2") (pin "21") (pinfunction "21_21") (pintype "passive"))
      (node (ref "CF19.2") (pin "22") (pinfunction "22_22") (pintype "passive"))
      (node (ref "CF19.2") (pin "23") (pinfunction "23_23") (pintype "passive"))
      (node (ref "CF19.2") (pin "24") (pinfunction "24_24") (pintype "passive"))
      (node (ref "CF19.2") (pin "25") (pinfunction "25_25") (pintype "passive"))
      (node (ref "CF19.2") (pin "26") (pinfunction "26_26") (pintype "passive"))
      (node (ref "CF2.2") (pin "21") (pinfunction "21_21") (pintype "passive"))
      (node (ref "CF2.2") (pin "22") (pinfunction "22_22") (pintype "passive"))
      (node (ref "CF2.2") (pin "23") (pinfunction "23_23") (pintype "passive"))
      (node (ref "CF2.2") (pin "24") (pinfunction "24_24") (pintype "passive"))
      (node (ref "CF2.2") (pin "25") (pinfunction "25_25") (pintype "passive"))
      (node (ref "CF2.2") (pin "26") (pinfunction "26_26") (pintype "passive"))
      (node (ref "CF2.3") (pin "21") (pinfunction "21_21") (pintype "passive"))
      (node (ref "CF2.3") (pin "22") (pinfunction "22_22") (pintype "passive"))
      (node (ref "CF2.3") (pin "23") (pinfunction "23_23") (pintype "passive"))
      (node (ref "CF2.3") (pin "24") (pinfunction "24_24") (pintype "passive"))
      (node (ref "CF2.3") (pin "25") (pinfunction "25_25") (pintype "passive"))
      (node (ref "CF2.3") (pin "26") (pinfunction "26_26") (pintype "passive"))
      (node (ref "CF2.4") (pin "21") (pinfunction "21_21") (pintype "passive"))
      (node (ref "CF2.4") (pin "22") (pinfunction "22_22") (pintype "passive"))
      (node (ref "CF2.4") (pin "23") (pinfunction "23_23") (pintype "passive"))
      (node (ref "CF2.4") (pin "24") (pinfunction "24_24") (pintype "passive"))
      (node (ref "CF2.4") (pin "25") (pinfunction "25_25") (pintype "passive"))
      (node (ref "CF2.4") (pin "26") (pinfunction "26_26") (pintype "passive"))
      (node (ref "CF3.2") (pin "21") (pinfunction "21_21") (pintype "passive"))
      (node (ref "CF3.2") (pin "22") (pinfunction "22_22") (pintype "passive"))
      (node (ref "CF3.2") (pin "23") (pinfunction "23_23") (pintype "passive"))
      (node (ref "CF3.2") (pin "24") (pinfunction "24_24") (pintype "passive"))
      (node (ref "CF3.2") (pin "25") (pinfunction "25_25") (pintype "passive"))
      (node (ref "CF3.2") (pin "26") (pinfunction "26_26") (pintype "passive"))
      (node (ref "CF4.2") (pin "21") (pinfunction "21_21") (pintype "passive"))
      (node (ref "CF4.2") (pin "22") (pinfunction "22_22") (pintype "passive"))
      (node (ref "CF4.2") (pin "23") (pinfunction "23_23") (pintype "passive"))
      (node (ref "CF4.2") (pin "24") (pinfunction "24_24") (pintype "passive"))
      (node (ref "CF4.2") (pin "25") (pinfunction "25_25") (pintype "passive"))
      (node (ref "CF4.2") (pin "26") (pinfunction "26_26") (pintype "passive"))
      (node (ref "CF5.2") (pin "21") (pinfunction "21_21") (pintype "passive"))
      (node (ref "CF5.2") (pin "22") (pinfunction "22_22") (pintype "passive"))
      (node (ref "CF5.2") (pin "23") (pinfunction "23_23") (pintype "passive"))
      (node (ref "CF5.2") (pin "24") (pinfunction "24_24") (pintype "passive"))
      (node (ref "CF5.2") (pin "25") (pinfunction "25_25") (pintype "passive"))
      (node (ref "CF5.2") (pin "26") (pinfunction "26_26") (pintype "passive"))
      (node (ref "CF6.2") (pin "21") (pinfunction "21_21") (pintype "passive"))
      (node (ref "CF6.2") (pin "22") (pinfunction "22_22") (pintype "passive"))
      (node (ref "CF6.2") (pin "23") (pinfunction "23_23") (pintype "passive"))
      (node (ref "CF6.2") (pin "24") (pinfunction "24_24") (pintype "passive"))
      (node (ref "CF6.2") (pin "25") (pinfunction "25_25") (pintype "passive"))
      (node (ref "CF6.2") (pin "26") (pinfunction "26_26") (pintype "passive"))
      (node (ref "CF7.2") (pin "21") (pinfunction "21_21") (pintype "passive"))
      (node (ref "CF7.2") (pin "22") (pinfunction "22_22") (pintype "passive"))
      (node (ref "CF7.2") (pin "23") (pinfunction "23_23") (pintype "passive"))
      (node (ref "CF7.2") (pin "24") (pinfunction "24_24") (pintype "passive"))
      (node (ref "CF7.2") (pin "25") (pinfunction "25_25") (pintype "passive"))
      (node (ref "CF7.2") (pin "26") (pinfunction "26_26") (pintype "passive"))
      (node (ref "CF8.2") (pin "21") (pinfunction "21_21") (pintype "passive"))
      (node (ref "CF8.2") (pin "22") (pinfunction "22_22") (pintype "passive"))
      (node (ref "CF8.2") (pin "23") (pinfunction "23_23") (pintype "passive"))
      (node (ref "CF8.2") (pin "24") (pinfunction "24_24") (pintype "passive"))
      (node (ref "CF8.2") (pin "25") (pinfunction "25_25") (pintype "passive"))
      (node (ref "CF8.2") (pin "26") (pinfunction "26_26") (pintype "passive"))
    )
    (net (code "33") (name "VHF-TURNSTILE") (class "Default")
      (node (ref "CM20.1") (pin "RF-DOWN") (pinfunction "RF_RF-DOWN") (pintype "passive"))
      (node (ref "CM20.6") (pin "RF-DOWN") (pinfunction "RF_RF-DOWN") (pintype "passive"))
    )
    (net (code "34") (name "~{SD}") (class "Default")
      (node (ref "CF12.2") (pin "39") (pinfunction "39_39") (pintype "passive"))
      (node (ref "CF12.2") (pin "40") (pinfunction "40_40") (pintype "passive"))
      (node (ref "CF13.2") (pin "39") (pinfunction "39_39") (pintype "passive"))
      (node (ref "CF13.2") (pin "40") (pinfunction "40_40") (pintype "passive"))
      (node (ref "CF14.2") (pin "39") (pinfunction "39_39") (pintype "passive"))
      (node (ref "CF14.2") (pin "40") (pinfunction "40_40") (pintype "passive"))
      (node (ref "CF15.2") (pin "39") (pinfunction "39_39") (pintype "passive"))
      (node (ref "CF15.2") (pin "40") (pinfunction "40_40") (pintype "passive"))
      (node (ref "CF16.2") (pin "39") (pinfunction "39_39") (pintype "passive"))
      (node (ref "CF16.2") (pin "40") (pinfunction "40_40") (pintype "passive"))
      (node (ref "CF17.2") (pin "39") (pinfunction "39_39") (pintype "passive"))
      (node (ref "CF17.2") (pin "40") (pinfunction "40_40") (pintype "passive"))
      (node (ref "CF18.2") (pin "39") (pinfunction "39_39") (pintype "passive"))
      (node (ref "CF18.2") (pin "40") (pinfunction "40_40") (pintype "passive"))
      (node (ref "CF19.2") (pin "39") (pinfunction "39_39") (pintype "passive"))
      (node (ref "CF19.2") (pin "40") (pinfunction "40_40") (pintype "passive"))
      (node (ref "CF2.2") (pin "39") (pinfunction "39_39") (pintype "passive"))
      (node (ref "CF2.2") (pin "40") (pinfunction "40_40") (pintype "passive"))
      (node (ref "CF2.3") (pin "39") (pinfunction "39_39") (pintype "passive"))
      (node (ref "CF2.3") (pin "40") (pinfunction "40_40") (pintype "passive"))
      (node (ref "CF2.4") (pin "39") (pinfunction "39_39") (pintype "passive"))
      (node (ref "CF2.4") (pin "40") (pinfunction "40_40") (pintype "passive"))
      (node (ref "CF3.2") (pin "39") (pinfunction "39_39") (pintype "passive"))
      (node (ref "CF3.2") (pin "40") (pinfunction "40_40") (pintype "passive"))
      (node (ref "CF4.2") (pin "39") (pinfunction "39_39") (pintype "passive"))
      (node (ref "CF4.2") (pin "40") (pinfunction "40_40") (pintype "passive"))
      (node (ref "CF5.2") (pin "39") (pinfunction "39_39") (pintype "passive"))
      (node (ref "CF5.2") (pin "40") (pinfunction "40_40") (pintype "passive"))
      (node (ref "CF6.2") (pin "39") (pinfunction "39_39") (pintype "passive"))
      (node (ref "CF6.2") (pin "40") (pinfunction "40_40") (pintype "passive"))
      (node (ref "CF7.2") (pin "39") (pinfunction "39_39") (pintype "passive"))
      (node (ref "CF7.2") (pin "40") (pinfunction "40_40") (pintype "passive"))
      (node (ref "CF8.2") (pin "39") (pinfunction "39_39") (pintype "passive"))
      (node (ref "CF8.2") (pin "40") (pinfunction "40_40") (pintype "passive"))
    )
  )
)
